# 7x7RGB-IR-J010129B.net
KiCad netlist of a schematic drawn in EAGLE
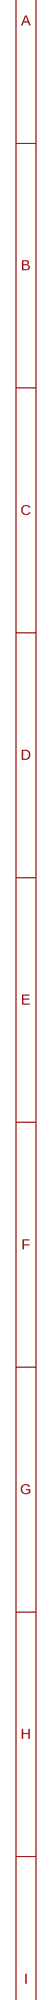
[diagram p0: schematic, sheet 1, part 1 of 2]
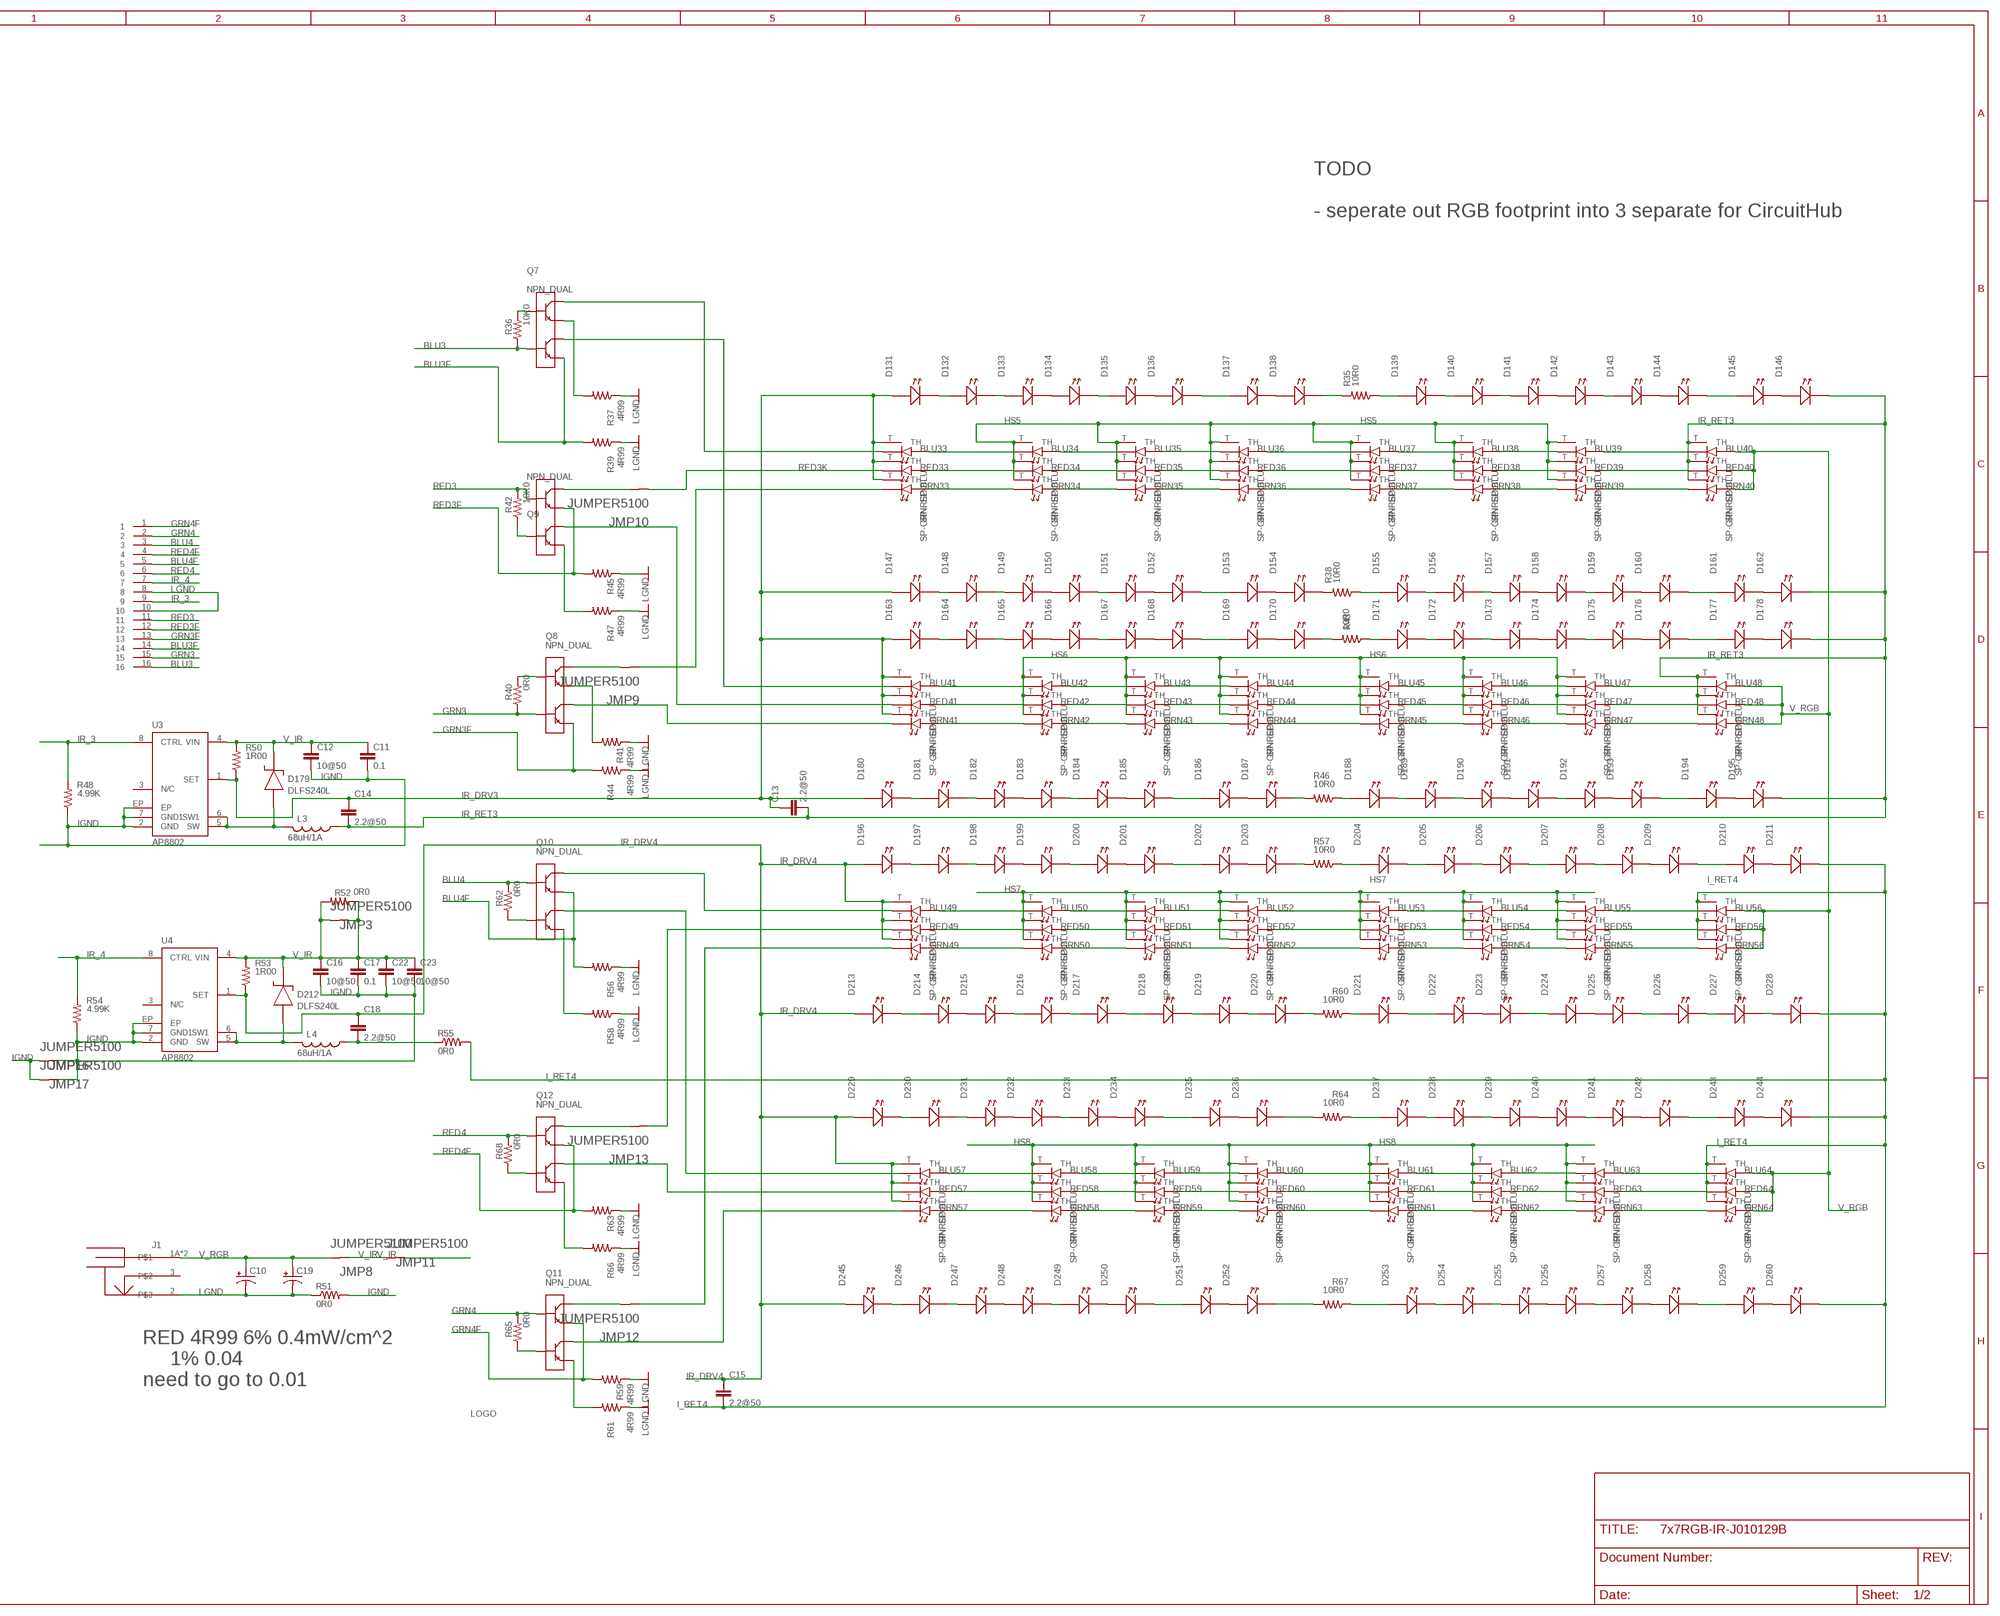
[diagram p1: schematic, sheet 1, part 2 of 2]
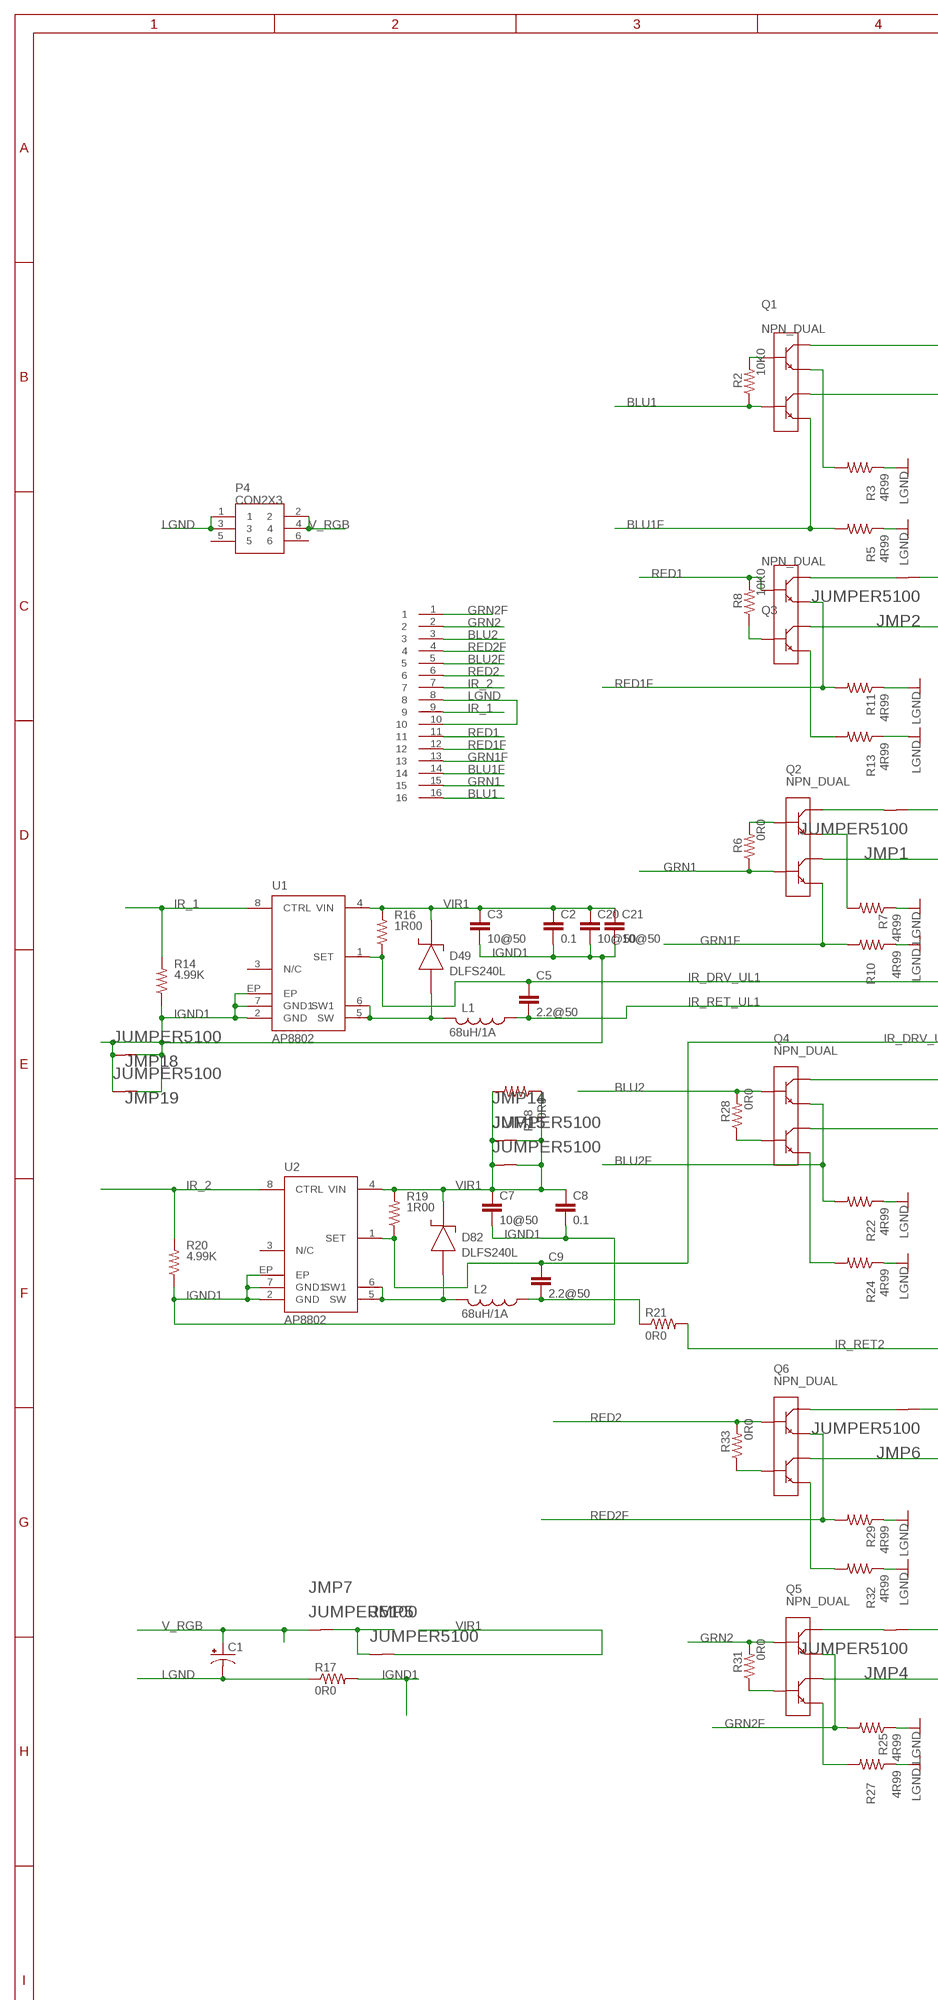
[diagram p2: schematic, sheet 2, part 1 of 2]
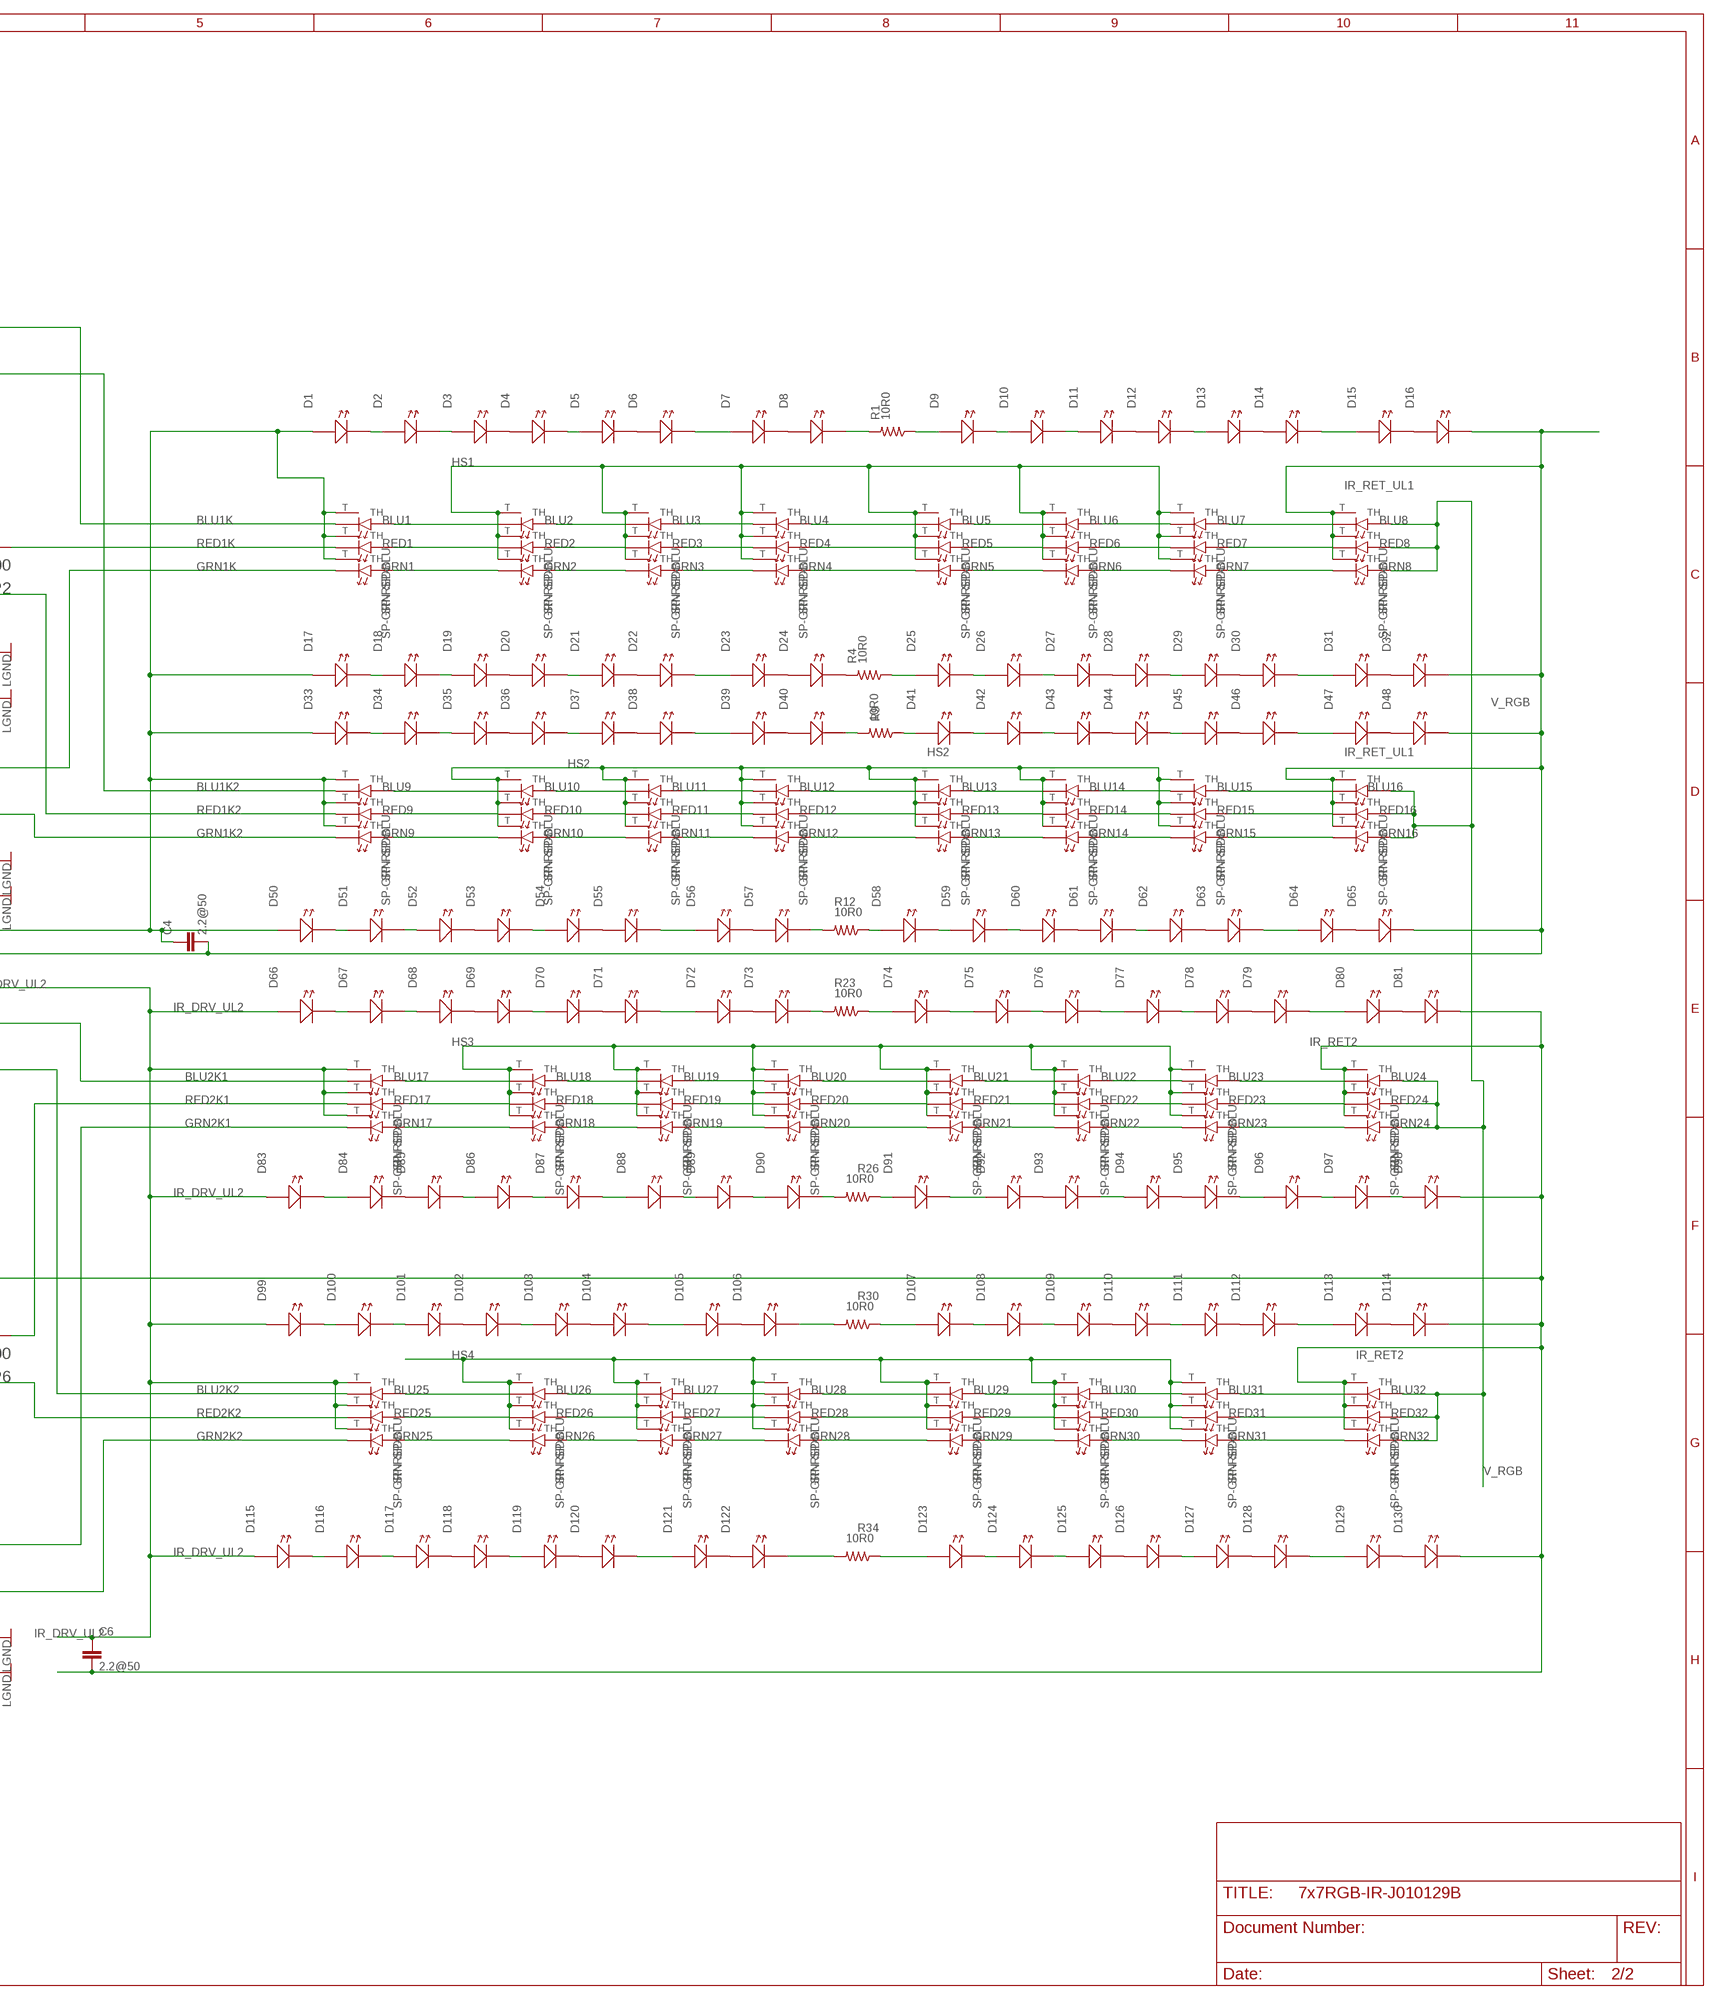
[diagram p3: schematic, sheet 2, part 2 of 2]

(export (version "E")
  (design (tool "Eeschema 10.0.6"))
  (components
    (comp (ref "BLU1")
      (value "SP-BLU")
      (footprint "eagle-import:SUNPLUS-LED")
      (libsource (lib "eagle-import") (part "LED-TH"))
    )
    (comp (ref "BLU2")
      (value "SP-BLU")
      (footprint "eagle-import:SUNPLUS-LED")
      (libsource (lib "eagle-import") (part "LED-TH"))
    )
    (comp (ref "BLU3")
      (value "SP-BLU")
      (footprint "eagle-import:SUNPLUS-LED")
      (libsource (lib "eagle-import") (part "LED-TH"))
    )
    (comp (ref "BLU4")
      (value "SP-BLU")
      (footprint "eagle-import:SUNPLUS-LED")
      (libsource (lib "eagle-import") (part "LED-TH"))
    )
    (comp (ref "BLU5")
      (value "SP-BLU")
      (footprint "eagle-import:SUNPLUS-LED")
      (libsource (lib "eagle-import") (part "LED-TH"))
    )
    (comp (ref "BLU6")
      (value "SP-BLU")
      (footprint "eagle-import:SUNPLUS-LED")
      (libsource (lib "eagle-import") (part "LED-TH"))
    )
    (comp (ref "BLU7")
      (value "SP-BLU")
      (footprint "eagle-import:SUNPLUS-LED")
      (libsource (lib "eagle-import") (part "LED-TH"))
    )
    (comp (ref "BLU8")
      (value "SP-BLU")
      (footprint "eagle-import:SUNPLUS-LED")
      (libsource (lib "eagle-import") (part "LED-TH"))
    )
    (comp (ref "BLU9")
      (value "SP-BLU")
      (footprint "eagle-import:SUNPLUS-LED")
      (libsource (lib "eagle-import") (part "LED-TH"))
    )
    (comp (ref "BLU10")
      (value "SP-BLU")
      (footprint "eagle-import:SUNPLUS-LED")
      (libsource (lib "eagle-import") (part "LED-TH"))
    )
    (comp (ref "BLU11")
      (value "SP-BLU")
      (footprint "eagle-import:SUNPLUS-LED")
      (libsource (lib "eagle-import") (part "LED-TH"))
    )
    (comp (ref "BLU12")
      (value "SP-BLU")
      (footprint "eagle-import:SUNPLUS-LED")
      (libsource (lib "eagle-import") (part "LED-TH"))
    )
    (comp (ref "BLU13")
      (value "SP-BLU")
      (footprint "eagle-import:SUNPLUS-LED")
      (libsource (lib "eagle-import") (part "LED-TH"))
    )
    (comp (ref "BLU14")
      (value "SP-BLU")
      (footprint "eagle-import:SUNPLUS-LED")
      (libsource (lib "eagle-import") (part "LED-TH"))
    )
    (comp (ref "BLU15")
      (value "SP-BLU")
      (footprint "eagle-import:SUNPLUS-LED")
      (libsource (lib "eagle-import") (part "LED-TH"))
    )
    (comp (ref "BLU16")
      (value "SP-BLU")
      (footprint "eagle-import:SUNPLUS-LED")
      (libsource (lib "eagle-import") (part "LED-TH"))
    )
    (comp (ref "BLU17")
      (value "SP-BLU")
      (footprint "eagle-import:SUNPLUS-LED")
      (libsource (lib "eagle-import") (part "LED-TH"))
    )
    (comp (ref "BLU18")
      (value "SP-BLU")
      (footprint "eagle-import:SUNPLUS-LED")
      (libsource (lib "eagle-import") (part "LED-TH"))
    )
    (comp (ref "BLU19")
      (value "SP-BLU")
      (footprint "eagle-import:SUNPLUS-LED")
      (libsource (lib "eagle-import") (part "LED-TH"))
    )
    (comp (ref "BLU20")
      (value "SP-BLU")
      (footprint "eagle-import:SUNPLUS-LED")
      (libsource (lib "eagle-import") (part "LED-TH"))
    )
    (comp (ref "BLU21")
      (value "SP-BLU")
      (footprint "eagle-import:SUNPLUS-LED")
      (libsource (lib "eagle-import") (part "LED-TH"))
    )
    (comp (ref "BLU22")
      (value "SP-BLU")
      (footprint "eagle-import:SUNPLUS-LED")
      (libsource (lib "eagle-import") (part "LED-TH"))
    )
    (comp (ref "BLU23")
      (value "SP-BLU")
      (footprint "eagle-import:SUNPLUS-LED")
      (libsource (lib "eagle-import") (part "LED-TH"))
    )
    (comp (ref "BLU24")
      (value "SP-BLU")
      (footprint "eagle-import:SUNPLUS-LED")
      (libsource (lib "eagle-import") (part "LED-TH"))
    )
    (comp (ref "BLU25")
      (value "SP-BLU")
      (footprint "eagle-import:SUNPLUS-LED")
      (libsource (lib "eagle-import") (part "LED-TH"))
    )
    (comp (ref "BLU26")
      (value "SP-BLU")
      (footprint "eagle-import:SUNPLUS-LED")
      (libsource (lib "eagle-import") (part "LED-TH"))
    )
    (comp (ref "BLU27")
      (value "SP-BLU")
      (footprint "eagle-import:SUNPLUS-LED")
      (libsource (lib "eagle-import") (part "LED-TH"))
    )
    (comp (ref "BLU28")
      (value "SP-BLU")
      (footprint "eagle-import:SUNPLUS-LED")
      (libsource (lib "eagle-import") (part "LED-TH"))
    )
    (comp (ref "BLU29")
      (value "SP-BLU")
      (footprint "eagle-import:SUNPLUS-LED")
      (libsource (lib "eagle-import") (part "LED-TH"))
    )
    (comp (ref "BLU30")
      (value "SP-BLU")
      (footprint "eagle-import:SUNPLUS-LED")
      (libsource (lib "eagle-import") (part "LED-TH"))
    )
    (comp (ref "BLU31")
      (value "SP-BLU")
      (footprint "eagle-import:SUNPLUS-LED")
      (libsource (lib "eagle-import") (part "LED-TH"))
    )
    (comp (ref "BLU32")
      (value "SP-BLU")
      (footprint "eagle-import:SUNPLUS-LED")
      (libsource (lib "eagle-import") (part "LED-TH"))
    )
    (comp (ref "C1")
      (value "CPOL-US153CLV-0810")
      (footprint "eagle-import:153CLV-0810")
      (libsource (lib "eagle-import") (part "CPOL-US153CLV-0810"))
    )
    (comp (ref "C2")
      (value "0.1")
      (footprint "eagle-import:0805S")
      (libsource (lib "eagle-import") (part "CAPS0805S"))
    )
    (comp (ref "C3")
      (value "10@50")
      (footprint "eagle-import:1210S")
      (libsource (lib "eagle-import") (part "CAPS1210S"))
    )
    (comp (ref "C4")
      (value "2.2@50")
      (footprint "eagle-import:1206S")
      (libsource (lib "eagle-import") (part "CAPS1206S"))
    )
    (comp (ref "C5")
      (value "2.2@50")
      (footprint "eagle-import:1206S")
      (libsource (lib "eagle-import") (part "CAPS1206S"))
    )
    (comp (ref "C6")
      (value "2.2@50")
      (footprint "eagle-import:1206S")
      (libsource (lib "eagle-import") (part "CAPS1206S"))
    )
    (comp (ref "C7")
      (value "10@50")
      (footprint "eagle-import:1210S")
      (libsource (lib "eagle-import") (part "CAPS1210S"))
    )
    (comp (ref "C8")
      (value "0.1")
      (footprint "eagle-import:0805S")
      (libsource (lib "eagle-import") (part "CAPS0805S"))
    )
    (comp (ref "C9")
      (value "2.2@50")
      (footprint "eagle-import:1206S")
      (libsource (lib "eagle-import") (part "CAPS1206S"))
    )
    (comp (ref "C20")
      (value "10@50")
      (footprint "eagle-import:1210S")
      (libsource (lib "eagle-import") (part "CAPS1210S"))
    )
    (comp (ref "C21")
      (value "10@50")
      (footprint "eagle-import:1210S")
      (libsource (lib "eagle-import") (part "CAPS1210S"))
    )
    (comp (ref "D1")
      (value "LEDLED_SFH4050")
      (footprint "eagle-import:LED_SFH4050")
      (libsource (lib "eagle-import") (part "LEDLED_SFH4050"))
    )
    (comp (ref "D2")
      (value "LEDLED_SFH4050")
      (footprint "eagle-import:LED_SFH4050")
      (libsource (lib "eagle-import") (part "LEDLED_SFH4050"))
    )
    (comp (ref "D3")
      (value "LEDLED_SFH4050")
      (footprint "eagle-import:LED_SFH4050")
      (libsource (lib "eagle-import") (part "LEDLED_SFH4050"))
    )
    (comp (ref "D4")
      (value "LEDLED_SFH4050")
      (footprint "eagle-import:LED_SFH4050")
      (libsource (lib "eagle-import") (part "LEDLED_SFH4050"))
    )
    (comp (ref "D5")
      (value "LEDLED_SFH4050")
      (footprint "eagle-import:LED_SFH4050")
      (libsource (lib "eagle-import") (part "LEDLED_SFH4050"))
    )
    (comp (ref "D6")
      (value "LEDLED_SFH4050")
      (footprint "eagle-import:LED_SFH4050")
      (libsource (lib "eagle-import") (part "LEDLED_SFH4050"))
    )
    (comp (ref "D7")
      (value "LEDLED_SFH4050")
      (footprint "eagle-import:LED_SFH4050")
      (libsource (lib "eagle-import") (part "LEDLED_SFH4050"))
    )
    (comp (ref "D8")
      (value "LEDLED_SFH4050")
      (footprint "eagle-import:LED_SFH4050")
      (libsource (lib "eagle-import") (part "LEDLED_SFH4050"))
    )
    (comp (ref "D9")
      (value "LEDLED_SFH4050")
      (footprint "eagle-import:LED_SFH4050")
      (libsource (lib "eagle-import") (part "LEDLED_SFH4050"))
    )
    (comp (ref "D10")
      (value "LEDLED_SFH4050")
      (footprint "eagle-import:LED_SFH4050")
      (libsource (lib "eagle-import") (part "LEDLED_SFH4050"))
    )
    (comp (ref "D11")
      (value "LEDLED_SFH4050")
      (footprint "eagle-import:LED_SFH4050")
      (libsource (lib "eagle-import") (part "LEDLED_SFH4050"))
    )
    (comp (ref "D12")
      (value "LEDLED_SFH4050")
      (footprint "eagle-import:LED_SFH4050")
      (libsource (lib "eagle-import") (part "LEDLED_SFH4050"))
    )
    (comp (ref "D13")
      (value "LEDLED_SFH4050")
      (footprint "eagle-import:LED_SFH4050")
      (libsource (lib "eagle-import") (part "LEDLED_SFH4050"))
    )
    (comp (ref "D14")
      (value "LEDLED_SFH4050")
      (footprint "eagle-import:LED_SFH4050")
      (libsource (lib "eagle-import") (part "LEDLED_SFH4050"))
    )
    (comp (ref "D15")
      (value "LEDLED_SFH4050")
      (footprint "eagle-import:LED_SFH4050")
      (libsource (lib "eagle-import") (part "LEDLED_SFH4050"))
    )
    (comp (ref "D16")
      (value "LEDLED_SFH4050")
      (footprint "eagle-import:LED_SFH4050")
      (libsource (lib "eagle-import") (part "LEDLED_SFH4050"))
    )
    (comp (ref "D17")
      (value "LEDLED_SFH4050")
      (footprint "eagle-import:LED_SFH4050")
      (libsource (lib "eagle-import") (part "LEDLED_SFH4050"))
    )
    (comp (ref "D18")
      (value "LEDLED_SFH4050")
      (footprint "eagle-import:LED_SFH4050")
      (libsource (lib "eagle-import") (part "LEDLED_SFH4050"))
    )
    (comp (ref "D19")
      (value "LEDLED_SFH4050")
      (footprint "eagle-import:LED_SFH4050")
      (libsource (lib "eagle-import") (part "LEDLED_SFH4050"))
    )
    (comp (ref "D20")
      (value "LEDLED_SFH4050")
      (footprint "eagle-import:LED_SFH4050")
      (libsource (lib "eagle-import") (part "LEDLED_SFH4050"))
    )
    (comp (ref "D21")
      (value "LEDLED_SFH4050")
      (footprint "eagle-import:LED_SFH4050")
      (libsource (lib "eagle-import") (part "LEDLED_SFH4050"))
    )
    (comp (ref "D22")
      (value "LEDLED_SFH4050")
      (footprint "eagle-import:LED_SFH4050")
      (libsource (lib "eagle-import") (part "LEDLED_SFH4050"))
    )
    (comp (ref "D23")
      (value "LEDLED_SFH4050")
      (footprint "eagle-import:LED_SFH4050")
      (libsource (lib "eagle-import") (part "LEDLED_SFH4050"))
    )
    (comp (ref "D24")
      (value "LEDLED_SFH4050")
      (footprint "eagle-import:LED_SFH4050")
      (libsource (lib "eagle-import") (part "LEDLED_SFH4050"))
    )
    (comp (ref "D25")
      (value "LEDLED_SFH4050")
      (footprint "eagle-import:LED_SFH4050")
      (libsource (lib "eagle-import") (part "LEDLED_SFH4050"))
    )
    (comp (ref "D26")
      (value "LEDLED_SFH4050")
      (footprint "eagle-import:LED_SFH4050")
      (libsource (lib "eagle-import") (part "LEDLED_SFH4050"))
    )
    (comp (ref "D27")
      (value "LEDLED_SFH4050")
      (footprint "eagle-import:LED_SFH4050")
      (libsource (lib "eagle-import") (part "LEDLED_SFH4050"))
    )
    (comp (ref "D28")
      (value "LEDLED_SFH4050")
      (footprint "eagle-import:LED_SFH4050")
      (libsource (lib "eagle-import") (part "LEDLED_SFH4050"))
    )
    (comp (ref "D29")
      (value "LEDLED_SFH4050")
      (footprint "eagle-import:LED_SFH4050")
      (libsource (lib "eagle-import") (part "LEDLED_SFH4050"))
    )
    (comp (ref "D30")
      (value "LEDLED_SFH4050")
      (footprint "eagle-import:LED_SFH4050")
      (libsource (lib "eagle-import") (part "LEDLED_SFH4050"))
    )
    (comp (ref "D31")
      (value "LEDLED_SFH4050")
      (footprint "eagle-import:LED_SFH4050")
      (libsource (lib "eagle-import") (part "LEDLED_SFH4050"))
    )
    (comp (ref "D32")
      (value "LEDLED_SFH4050")
      (footprint "eagle-import:LED_SFH4050")
      (libsource (lib "eagle-import") (part "LEDLED_SFH4050"))
    )
    (comp (ref "D33")
      (value "LEDLED_SFH4050")
      (footprint "eagle-import:LED_SFH4050")
      (libsource (lib "eagle-import") (part "LEDLED_SFH4050"))
    )
    (comp (ref "D34")
      (value "LEDLED_SFH4050")
      (footprint "eagle-import:LED_SFH4050")
      (libsource (lib "eagle-import") (part "LEDLED_SFH4050"))
    )
    (comp (ref "D35")
      (value "LEDLED_SFH4050")
      (footprint "eagle-import:LED_SFH4050")
      (libsource (lib "eagle-import") (part "LEDLED_SFH4050"))
    )
    (comp (ref "D36")
      (value "LEDLED_SFH4050")
      (footprint "eagle-import:LED_SFH4050")
      (libsource (lib "eagle-import") (part "LEDLED_SFH4050"))
    )
    (comp (ref "D37")
      (value "LEDLED_SFH4050")
      (footprint "eagle-import:LED_SFH4050")
      (libsource (lib "eagle-import") (part "LEDLED_SFH4050"))
    )
    (comp (ref "D38")
      (value "LEDLED_SFH4050")
      (footprint "eagle-import:LED_SFH4050")
      (libsource (lib "eagle-import") (part "LEDLED_SFH4050"))
    )
    (comp (ref "D39")
      (value "LEDLED_SFH4050")
      (footprint "eagle-import:LED_SFH4050")
      (libsource (lib "eagle-import") (part "LEDLED_SFH4050"))
    )
    (comp (ref "D40")
      (value "LEDLED_SFH4050")
      (footprint "eagle-import:LED_SFH4050")
      (libsource (lib "eagle-import") (part "LEDLED_SFH4050"))
    )
    (comp (ref "D41")
      (value "LEDLED_SFH4050")
      (footprint "eagle-import:LED_SFH4050")
      (libsource (lib "eagle-import") (part "LEDLED_SFH4050"))
    )
    (comp (ref "D42")
      (value "LEDLED_SFH4050")
      (footprint "eagle-import:LED_SFH4050")
      (libsource (lib "eagle-import") (part "LEDLED_SFH4050"))
    )
    (comp (ref "D43")
      (value "LEDLED_SFH4050")
      (footprint "eagle-import:LED_SFH4050")
      (libsource (lib "eagle-import") (part "LEDLED_SFH4050"))
    )
    (comp (ref "D44")
      (value "LEDLED_SFH4050")
      (footprint "eagle-import:LED_SFH4050")
      (libsource (lib "eagle-import") (part "LEDLED_SFH4050"))
    )
    (comp (ref "D45")
      (value "LEDLED_SFH4050")
      (footprint "eagle-import:LED_SFH4050")
      (libsource (lib "eagle-import") (part "LEDLED_SFH4050"))
    )
    (comp (ref "D46")
      (value "LEDLED_SFH4050")
      (footprint "eagle-import:LED_SFH4050")
      (libsource (lib "eagle-import") (part "LEDLED_SFH4050"))
    )
    (comp (ref "D47")
      (value "LEDLED_SFH4050")
      (footprint "eagle-import:LED_SFH4050")
      (libsource (lib "eagle-import") (part "LEDLED_SFH4050"))
    )
    (comp (ref "D48")
      (value "LEDLED_SFH4050")
      (footprint "eagle-import:LED_SFH4050")
      (libsource (lib "eagle-import") (part "LEDLED_SFH4050"))
    )
    (comp (ref "D49")
      (value "DLFS240L")
      (footprint "eagle-import:PWRDI-123")
      (libsource (lib "eagle-import") (part "DIODE_SCHOTTKYPWRDI-123"))
    )
    (comp (ref "D50")
      (value "LEDLED_SFH4050")
      (footprint "eagle-import:LED_SFH4050")
      (libsource (lib "eagle-import") (part "LEDLED_SFH4050"))
    )
    (comp (ref "D51")
      (value "LEDLED_SFH4050")
      (footprint "eagle-import:LED_SFH4050")
      (libsource (lib "eagle-import") (part "LEDLED_SFH4050"))
    )
    (comp (ref "D52")
      (value "LEDLED_SFH4050")
      (footprint "eagle-import:LED_SFH4050")
      (libsource (lib "eagle-import") (part "LEDLED_SFH4050"))
    )
    (comp (ref "D53")
      (value "LEDLED_SFH4050")
      (footprint "eagle-import:LED_SFH4050")
      (libsource (lib "eagle-import") (part "LEDLED_SFH4050"))
    )
    (comp (ref "D54")
      (value "LEDLED_SFH4050")
      (footprint "eagle-import:LED_SFH4050")
      (libsource (lib "eagle-import") (part "LEDLED_SFH4050"))
    )
    (comp (ref "D55")
      (value "LEDLED_SFH4050")
      (footprint "eagle-import:LED_SFH4050")
      (libsource (lib "eagle-import") (part "LEDLED_SFH4050"))
    )
    (comp (ref "D56")
      (value "LEDLED_SFH4050")
      (footprint "eagle-import:LED_SFH4050")
      (libsource (lib "eagle-import") (part "LEDLED_SFH4050"))
    )
    (comp (ref "D57")
      (value "LEDLED_SFH4050")
      (footprint "eagle-import:LED_SFH4050")
      (libsource (lib "eagle-import") (part "LEDLED_SFH4050"))
    )
    (comp (ref "D58")
      (value "LEDLED_SFH4050")
      (footprint "eagle-import:LED_SFH4050")
      (libsource (lib "eagle-import") (part "LEDLED_SFH4050"))
    )
    (comp (ref "D59")
      (value "LEDLED_SFH4050")
      (footprint "eagle-import:LED_SFH4050")
      (libsource (lib "eagle-import") (part "LEDLED_SFH4050"))
    )
    (comp (ref "D60")
      (value "LEDLED_SFH4050")
      (footprint "eagle-import:LED_SFH4050")
      (libsource (lib "eagle-import") (part "LEDLED_SFH4050"))
    )
    (comp (ref "D61")
      (value "LEDLED_SFH4050")
      (footprint "eagle-import:LED_SFH4050")
      (libsource (lib "eagle-import") (part "LEDLED_SFH4050"))
    )
    (comp (ref "D62")
      (value "LEDLED_SFH4050")
      (footprint "eagle-import:LED_SFH4050")
      (libsource (lib "eagle-import") (part "LEDLED_SFH4050"))
    )
    (comp (ref "D63")
      (value "LEDLED_SFH4050")
      (footprint "eagle-import:LED_SFH4050")
      (libsource (lib "eagle-import") (part "LEDLED_SFH4050"))
    )
    (comp (ref "D64")
      (value "LEDLED_SFH4050")
      (footprint "eagle-import:LED_SFH4050")
      (libsource (lib "eagle-import") (part "LEDLED_SFH4050"))
    )
    (comp (ref "D65")
      (value "LEDLED_SFH4050")
      (footprint "eagle-import:LED_SFH4050")
      (libsource (lib "eagle-import") (part "LEDLED_SFH4050"))
    )
    (comp (ref "D66")
      (value "LEDLED_SFH4050")
      (footprint "eagle-import:LED_SFH4050")
      (libsource (lib "eagle-import") (part "LEDLED_SFH4050"))
    )
    (comp (ref "D67")
      (value "LEDLED_SFH4050")
      (footprint "eagle-import:LED_SFH4050")
      (libsource (lib "eagle-import") (part "LEDLED_SFH4050"))
    )
    (comp (ref "D68")
      (value "LEDLED_SFH4050")
      (footprint "eagle-import:LED_SFH4050")
      (libsource (lib "eagle-import") (part "LEDLED_SFH4050"))
    )
    (comp (ref "D69")
      (value "LEDLED_SFH4050")
      (footprint "eagle-import:LED_SFH4050")
      (libsource (lib "eagle-import") (part "LEDLED_SFH4050"))
    )
    (comp (ref "D70")
      (value "LEDLED_SFH4050")
      (footprint "eagle-import:LED_SFH4050")
      (libsource (lib "eagle-import") (part "LEDLED_SFH4050"))
    )
    (comp (ref "D71")
      (value "LEDLED_SFH4050")
      (footprint "eagle-import:LED_SFH4050")
      (libsource (lib "eagle-import") (part "LEDLED_SFH4050"))
    )
    (comp (ref "D72")
      (value "LEDLED_SFH4050")
      (footprint "eagle-import:LED_SFH4050")
      (libsource (lib "eagle-import") (part "LEDLED_SFH4050"))
    )
    (comp (ref "D73")
      (value "LEDLED_SFH4050")
      (footprint "eagle-import:LED_SFH4050")
      (libsource (lib "eagle-import") (part "LEDLED_SFH4050"))
    )
    (comp (ref "D74")
      (value "LEDLED_SFH4050")
      (footprint "eagle-import:LED_SFH4050")
      (libsource (lib "eagle-import") (part "LEDLED_SFH4050"))
    )
    (comp (ref "D75")
      (value "LEDLED_SFH4050")
      (footprint "eagle-import:LED_SFH4050")
      (libsource (lib "eagle-import") (part "LEDLED_SFH4050"))
    )
    (comp (ref "D76")
      (value "LEDLED_SFH4050")
      (footprint "eagle-import:LED_SFH4050")
      (libsource (lib "eagle-import") (part "LEDLED_SFH4050"))
    )
    (comp (ref "D77")
      (value "LEDLED_SFH4050")
      (footprint "eagle-import:LED_SFH4050")
      (libsource (lib "eagle-import") (part "LEDLED_SFH4050"))
    )
    (comp (ref "D78")
      (value "LEDLED_SFH4050")
      (footprint "eagle-import:LED_SFH4050")
      (libsource (lib "eagle-import") (part "LEDLED_SFH4050"))
    )
    (comp (ref "D79")
      (value "LEDLED_SFH4050")
      (footprint "eagle-import:LED_SFH4050")
      (libsource (lib "eagle-import") (part "LEDLED_SFH4050"))
    )
    (comp (ref "D80")
      (value "LEDLED_SFH4050")
      (footprint "eagle-import:LED_SFH4050")
      (libsource (lib "eagle-import") (part "LEDLED_SFH4050"))
    )
    (comp (ref "D81")
      (value "LEDLED_SFH4050")
      (footprint "eagle-import:LED_SFH4050")
      (libsource (lib "eagle-import") (part "LEDLED_SFH4050"))
    )
    (comp (ref "D82")
      (value "DLFS240L")
      (footprint "eagle-import:PWRDI-123")
      (libsource (lib "eagle-import") (part "DIODE_SCHOTTKYPWRDI-123"))
    )
    (comp (ref "D83")
      (value "LEDLED_SFH4050")
      (footprint "eagle-import:LED_SFH4050")
      (libsource (lib "eagle-import") (part "LEDLED_SFH4050"))
    )
    (comp (ref "D84")
      (value "LEDLED_SFH4050")
      (footprint "eagle-import:LED_SFH4050")
      (libsource (lib "eagle-import") (part "LEDLED_SFH4050"))
    )
    (comp (ref "D85")
      (value "LEDLED_SFH4050")
      (footprint "eagle-import:LED_SFH4050")
      (libsource (lib "eagle-import") (part "LEDLED_SFH4050"))
    )
    (comp (ref "D86")
      (value "LEDLED_SFH4050")
      (footprint "eagle-import:LED_SFH4050")
      (libsource (lib "eagle-import") (part "LEDLED_SFH4050"))
    )
    (comp (ref "D87")
      (value "LEDLED_SFH4050")
      (footprint "eagle-import:LED_SFH4050")
      (libsource (lib "eagle-import") (part "LEDLED_SFH4050"))
    )
    (comp (ref "D88")
      (value "LEDLED_SFH4050")
      (footprint "eagle-import:LED_SFH4050")
      (libsource (lib "eagle-import") (part "LEDLED_SFH4050"))
    )
    (comp (ref "D89")
      (value "LEDLED_SFH4050")
      (footprint "eagle-import:LED_SFH4050")
      (libsource (lib "eagle-import") (part "LEDLED_SFH4050"))
    )
    (comp (ref "D90")
      (value "LEDLED_SFH4050")
      (footprint "eagle-import:LED_SFH4050")
      (libsource (lib "eagle-import") (part "LEDLED_SFH4050"))
    )
    (comp (ref "D91")
      (value "LEDLED_SFH4050")
      (footprint "eagle-import:LED_SFH4050")
      (libsource (lib "eagle-import") (part "LEDLED_SFH4050"))
    )
    (comp (ref "D92")
      (value "LEDLED_SFH4050")
      (footprint "eagle-import:LED_SFH4050")
      (libsource (lib "eagle-import") (part "LEDLED_SFH4050"))
    )
    (comp (ref "D93")
      (value "LEDLED_SFH4050")
      (footprint "eagle-import:LED_SFH4050")
      (libsource (lib "eagle-import") (part "LEDLED_SFH4050"))
    )
    (comp (ref "D94")
      (value "LEDLED_SFH4050")
      (footprint "eagle-import:LED_SFH4050")
      (libsource (lib "eagle-import") (part "LEDLED_SFH4050"))
    )
    (comp (ref "D95")
      (value "LEDLED_SFH4050")
      (footprint "eagle-import:LED_SFH4050")
      (libsource (lib "eagle-import") (part "LEDLED_SFH4050"))
    )
    (comp (ref "D96")
      (value "LEDLED_SFH4050")
      (footprint "eagle-import:LED_SFH4050")
      (libsource (lib "eagle-import") (part "LEDLED_SFH4050"))
    )
    (comp (ref "D97")
      (value "LEDLED_SFH4050")
      (footprint "eagle-import:LED_SFH4050")
      (libsource (lib "eagle-import") (part "LEDLED_SFH4050"))
    )
    (comp (ref "D98")
      (value "LEDLED_SFH4050")
      (footprint "eagle-import:LED_SFH4050")
      (libsource (lib "eagle-import") (part "LEDLED_SFH4050"))
    )
    (comp (ref "D99")
      (value "LEDLED_SFH4050")
      (footprint "eagle-import:LED_SFH4050")
      (libsource (lib "eagle-import") (part "LEDLED_SFH4050"))
    )
    (comp (ref "D100")
      (value "LEDLED_SFH4050")
      (footprint "eagle-import:LED_SFH4050")
      (libsource (lib "eagle-import") (part "LEDLED_SFH4050"))
    )
    (comp (ref "D101")
      (value "LEDLED_SFH4050")
      (footprint "eagle-import:LED_SFH4050")
      (libsource (lib "eagle-import") (part "LEDLED_SFH4050"))
    )
    (comp (ref "D102")
      (value "LEDLED_SFH4050")
      (footprint "eagle-import:LED_SFH4050")
      (libsource (lib "eagle-import") (part "LEDLED_SFH4050"))
    )
    (comp (ref "D103")
      (value "LEDLED_SFH4050")
      (footprint "eagle-import:LED_SFH4050")
      (libsource (lib "eagle-import") (part "LEDLED_SFH4050"))
    )
    (comp (ref "D104")
      (value "LEDLED_SFH4050")
      (footprint "eagle-import:LED_SFH4050")
      (libsource (lib "eagle-import") (part "LEDLED_SFH4050"))
    )
    (comp (ref "D105")
      (value "LEDLED_SFH4050")
      (footprint "eagle-import:LED_SFH4050")
      (libsource (lib "eagle-import") (part "LEDLED_SFH4050"))
    )
    (comp (ref "D106")
      (value "LEDLED_SFH4050")
      (footprint "eagle-import:LED_SFH4050")
      (libsource (lib "eagle-import") (part "LEDLED_SFH4050"))
    )
    (comp (ref "D107")
      (value "LEDLED_SFH4050")
      (footprint "eagle-import:LED_SFH4050")
      (libsource (lib "eagle-import") (part "LEDLED_SFH4050"))
    )
    (comp (ref "D108")
      (value "LEDLED_SFH4050")
      (footprint "eagle-import:LED_SFH4050")
      (libsource (lib "eagle-import") (part "LEDLED_SFH4050"))
    )
    (comp (ref "D109")
      (value "LEDLED_SFH4050")
      (footprint "eagle-import:LED_SFH4050")
      (libsource (lib "eagle-import") (part "LEDLED_SFH4050"))
    )
    (comp (ref "D110")
      (value "LEDLED_SFH4050")
      (footprint "eagle-import:LED_SFH4050")
      (libsource (lib "eagle-import") (part "LEDLED_SFH4050"))
    )
    (comp (ref "D111")
      (value "LEDLED_SFH4050")
      (footprint "eagle-import:LED_SFH4050")
      (libsource (lib "eagle-import") (part "LEDLED_SFH4050"))
    )
    (comp (ref "D112")
      (value "LEDLED_SFH4050")
      (footprint "eagle-import:LED_SFH4050")
      (libsource (lib "eagle-import") (part "LEDLED_SFH4050"))
    )
    (comp (ref "D113")
      (value "LEDLED_SFH4050")
      (footprint "eagle-import:LED_SFH4050")
      (libsource (lib "eagle-import") (part "LEDLED_SFH4050"))
    )
    (comp (ref "D114")
      (value "LEDLED_SFH4050")
      (footprint "eagle-import:LED_SFH4050")
      (libsource (lib "eagle-import") (part "LEDLED_SFH4050"))
    )
    (comp (ref "D115")
      (value "LEDLED_SFH4050")
      (footprint "eagle-import:LED_SFH4050")
      (libsource (lib "eagle-import") (part "LEDLED_SFH4050"))
    )
    (comp (ref "D116")
      (value "LEDLED_SFH4050")
      (footprint "eagle-import:LED_SFH4050")
      (libsource (lib "eagle-import") (part "LEDLED_SFH4050"))
    )
    (comp (ref "D117")
      (value "LEDLED_SFH4050")
      (footprint "eagle-import:LED_SFH4050")
      (libsource (lib "eagle-import") (part "LEDLED_SFH4050"))
    )
    (comp (ref "D118")
      (value "LEDLED_SFH4050")
      (footprint "eagle-import:LED_SFH4050")
      (libsource (lib "eagle-import") (part "LEDLED_SFH4050"))
    )
    (comp (ref "D119")
      (value "LEDLED_SFH4050")
      (footprint "eagle-import:LED_SFH4050")
      (libsource (lib "eagle-import") (part "LEDLED_SFH4050"))
    )
    (comp (ref "D120")
      (value "LEDLED_SFH4050")
      (footprint "eagle-import:LED_SFH4050")
      (libsource (lib "eagle-import") (part "LEDLED_SFH4050"))
    )
    (comp (ref "D121")
      (value "LEDLED_SFH4050")
      (footprint "eagle-import:LED_SFH4050")
      (libsource (lib "eagle-import") (part "LEDLED_SFH4050"))
    )
    (comp (ref "D122")
      (value "LEDLED_SFH4050")
      (footprint "eagle-import:LED_SFH4050")
      (libsource (lib "eagle-import") (part "LEDLED_SFH4050"))
    )
    (comp (ref "D123")
      (value "LEDLED_SFH4050")
      (footprint "eagle-import:LED_SFH4050")
      (libsource (lib "eagle-import") (part "LEDLED_SFH4050"))
    )
    (comp (ref "D124")
      (value "LEDLED_SFH4050")
      (footprint "eagle-import:LED_SFH4050")
      (libsource (lib "eagle-import") (part "LEDLED_SFH4050"))
    )
    (comp (ref "D125")
      (value "LEDLED_SFH4050")
      (footprint "eagle-import:LED_SFH4050")
      (libsource (lib "eagle-import") (part "LEDLED_SFH4050"))
    )
    (comp (ref "D126")
      (value "LEDLED_SFH4050")
      (footprint "eagle-import:LED_SFH4050")
      (libsource (lib "eagle-import") (part "LEDLED_SFH4050"))
    )
    (comp (ref "D127")
      (value "LEDLED_SFH4050")
      (footprint "eagle-import:LED_SFH4050")
      (libsource (lib "eagle-import") (part "LEDLED_SFH4050"))
    )
    (comp (ref "D128")
      (value "LEDLED_SFH4050")
      (footprint "eagle-import:LED_SFH4050")
      (libsource (lib "eagle-import") (part "LEDLED_SFH4050"))
    )
    (comp (ref "D129")
      (value "LEDLED_SFH4050")
      (footprint "eagle-import:LED_SFH4050")
      (libsource (lib "eagle-import") (part "LEDLED_SFH4050"))
    )
    (comp (ref "D130")
      (value "LEDLED_SFH4050")
      (footprint "eagle-import:LED_SFH4050")
      (libsource (lib "eagle-import") (part "LEDLED_SFH4050"))
    )
    (comp (ref "GRN1")
      (value "SP-GRN")
      (footprint "eagle-import:SUNPLUS-LED")
      (libsource (lib "eagle-import") (part "LED-TH"))
    )
    (comp (ref "GRN2")
      (value "SP-GRN")
      (footprint "eagle-import:SUNPLUS-LED")
      (libsource (lib "eagle-import") (part "LED-TH"))
    )
    (comp (ref "GRN3")
      (value "SP-GRN")
      (footprint "eagle-import:SUNPLUS-LED")
      (libsource (lib "eagle-import") (part "LED-TH"))
    )
    (comp (ref "GRN4")
      (value "SP-GRN")
      (footprint "eagle-import:SUNPLUS-LED")
      (libsource (lib "eagle-import") (part "LED-TH"))
    )
    (comp (ref "GRN5")
      (value "SP-GRN")
      (footprint "eagle-import:SUNPLUS-LED")
      (libsource (lib "eagle-import") (part "LED-TH"))
    )
    (comp (ref "GRN6")
      (value "SP-GRN")
      (footprint "eagle-import:SUNPLUS-LED")
      (libsource (lib "eagle-import") (part "LED-TH"))
    )
    (comp (ref "GRN7")
      (value "SP-GRN")
      (footprint "eagle-import:SUNPLUS-LED")
      (libsource (lib "eagle-import") (part "LED-TH"))
    )
    (comp (ref "GRN8")
      (value "SP-GRN")
      (footprint "eagle-import:SUNPLUS-LED")
      (libsource (lib "eagle-import") (part "LED-TH"))
    )
    (comp (ref "GRN9")
      (value "SP-GRN")
      (footprint "eagle-import:SUNPLUS-LED")
      (libsource (lib "eagle-import") (part "LED-TH"))
    )
    (comp (ref "GRN10")
      (value "SP-GRN")
      (footprint "eagle-import:SUNPLUS-LED")
      (libsource (lib "eagle-import") (part "LED-TH"))
    )
    (comp (ref "GRN11")
      (value "SP-GRN")
      (footprint "eagle-import:SUNPLUS-LED")
      (libsource (lib "eagle-import") (part "LED-TH"))
    )
    (comp (ref "GRN12")
      (value "SP-GRN")
      (footprint "eagle-import:SUNPLUS-LED")
      (libsource (lib "eagle-import") (part "LED-TH"))
    )
    (comp (ref "GRN13")
      (value "SP-GRN")
      (footprint "eagle-import:SUNPLUS-LED")
      (libsource (lib "eagle-import") (part "LED-TH"))
    )
    (comp (ref "GRN14")
      (value "SP-GRN")
      (footprint "eagle-import:SUNPLUS-LED")
      (libsource (lib "eagle-import") (part "LED-TH"))
    )
    (comp (ref "GRN15")
      (value "SP-GRN")
      (footprint "eagle-import:SUNPLUS-LED")
      (libsource (lib "eagle-import") (part "LED-TH"))
    )
    (comp (ref "GRN16")
      (value "SP-GRN")
      (footprint "eagle-import:SUNPLUS-LED")
      (libsource (lib "eagle-import") (part "LED-TH"))
    )
    (comp (ref "GRN17")
      (value "SP-GRN")
      (footprint "eagle-import:SUNPLUS-LED")
      (libsource (lib "eagle-import") (part "LED-TH"))
    )
    (comp (ref "GRN18")
      (value "SP-GRN")
      (footprint "eagle-import:SUNPLUS-LED")
      (libsource (lib "eagle-import") (part "LED-TH"))
    )
    (comp (ref "GRN19")
      (value "SP-GRN")
      (footprint "eagle-import:SUNPLUS-LED")
      (libsource (lib "eagle-import") (part "LED-TH"))
    )
    (comp (ref "GRN20")
      (value "SP-GRN")
      (footprint "eagle-import:SUNPLUS-LED")
      (libsource (lib "eagle-import") (part "LED-TH"))
    )
    (comp (ref "GRN21")
      (value "SP-GRN")
      (footprint "eagle-import:SUNPLUS-LED")
      (libsource (lib "eagle-import") (part "LED-TH"))
    )
    (comp (ref "GRN22")
      (value "SP-GRN")
      (footprint "eagle-import:SUNPLUS-LED")
      (libsource (lib "eagle-import") (part "LED-TH"))
    )
    (comp (ref "GRN23")
      (value "SP-GRN")
      (footprint "eagle-import:SUNPLUS-LED")
      (libsource (lib "eagle-import") (part "LED-TH"))
    )
    (comp (ref "GRN24")
      (value "SP-GRN")
      (footprint "eagle-import:SUNPLUS-LED")
      (libsource (lib "eagle-import") (part "LED-TH"))
    )
    (comp (ref "GRN25")
      (value "SP-GRN")
      (footprint "eagle-import:SUNPLUS-LED")
      (libsource (lib "eagle-import") (part "LED-TH"))
    )
    (comp (ref "GRN26")
      (value "SP-GRN")
      (footprint "eagle-import:SUNPLUS-LED")
      (libsource (lib "eagle-import") (part "LED-TH"))
    )
    (comp (ref "GRN27")
      (value "SP-GRN")
      (footprint "eagle-import:SUNPLUS-LED")
      (libsource (lib "eagle-import") (part "LED-TH"))
    )
    (comp (ref "GRN28")
      (value "SP-GRN")
      (footprint "eagle-import:SUNPLUS-LED")
      (libsource (lib "eagle-import") (part "LED-TH"))
    )
    (comp (ref "GRN29")
      (value "SP-GRN")
      (footprint "eagle-import:SUNPLUS-LED")
      (libsource (lib "eagle-import") (part "LED-TH"))
    )
    (comp (ref "GRN30")
      (value "SP-GRN")
      (footprint "eagle-import:SUNPLUS-LED")
      (libsource (lib "eagle-import") (part "LED-TH"))
    )
    (comp (ref "GRN31")
      (value "SP-GRN")
      (footprint "eagle-import:SUNPLUS-LED")
      (libsource (lib "eagle-import") (part "LED-TH"))
    )
    (comp (ref "GRN32")
      (value "SP-GRN")
      (footprint "eagle-import:SUNPLUS-LED")
      (libsource (lib "eagle-import") (part "LED-TH"))
    )
    (comp (ref "JMP1")
      (value "JUMPER5100")
      (footprint "eagle-import:5100")
      (libsource (lib "eagle-import") (part "JUMPER5100"))
    )
    (comp (ref "JMP2")
      (value "JUMPER5100")
      (footprint "eagle-import:5100")
      (libsource (lib "eagle-import") (part "JUMPER5100"))
    )
    (comp (ref "JMP4")
      (value "JUMPER5100")
      (footprint "eagle-import:5100")
      (libsource (lib "eagle-import") (part "JUMPER5100"))
    )
    (comp (ref "JMP5")
      (value "JUMPER5100")
      (footprint "eagle-import:5100")
      (libsource (lib "eagle-import") (part "JUMPER5100"))
    )
    (comp (ref "JMP6")
      (value "JUMPER5100")
      (footprint "eagle-import:5100")
      (libsource (lib "eagle-import") (part "JUMPER5100"))
    )
    (comp (ref "JMP7")
      (value "JUMPER5100")
      (footprint "eagle-import:5100")
      (libsource (lib "eagle-import") (part "JUMPER5100"))
    )
    (comp (ref "JMP14")
      (value "JUMPER5100")
      (footprint "eagle-import:5100")
      (libsource (lib "eagle-import") (part "JUMPER5100"))
    )
    (comp (ref "JMP15")
      (value "JUMPER5100")
      (footprint "eagle-import:5100")
      (libsource (lib "eagle-import") (part "JUMPER5100"))
    )
    (comp (ref "JMP18")
      (value "JUMPER5100")
      (footprint "eagle-import:5100")
      (libsource (lib "eagle-import") (part "JUMPER5100"))
    )
    (comp (ref "JMP19")
      (value "JUMPER5100")
      (footprint "eagle-import:5100")
      (libsource (lib "eagle-import") (part "JUMPER5100"))
    )
    (comp (ref "L1")
      (value "68uH/1A")
      (footprint "eagle-import:SRU8043")
      (libsource (lib "eagle-import") (part "INDUCTOR_SMSRU8043"))
    )
    (comp (ref "L2")
      (value "68uH/1A")
      (footprint "eagle-import:SRU8043")
      (libsource (lib "eagle-import") (part "INDUCTOR_SMSRU8043"))
    )
    (comp (ref "P1")
      (value "CON162X8SM-SMALL")
      (footprint "eagle-import:HEADER2X8_SM_SMALL")
      (libsource (lib "eagle-import") (part "CON162X8SM-SMALL"))
    )
    (comp (ref "P4")
      (value "CON2X3")
      (footprint "eagle-import:2X3_PLUG")
      (libsource (lib "eagle-import") (part "CON2X3"))
    )
    (comp (ref "Q1")
      (value "NPN_DUAL")
      (footprint "eagle-import:LFPAK56D")
      (libsource (lib "eagle-import") (part "NPN_DUAL"))
    )
    (comp (ref "Q2")
      (value "NPN_DUAL")
      (footprint "eagle-import:LFPAK56D")
      (libsource (lib "eagle-import") (part "NPN_DUAL"))
    )
    (comp (ref "Q3")
      (value "NPN_DUAL")
      (footprint "eagle-import:LFPAK56D")
      (libsource (lib "eagle-import") (part "NPN_DUAL"))
    )
    (comp (ref "Q4")
      (value "NPN_DUAL")
      (footprint "eagle-import:LFPAK56D")
      (libsource (lib "eagle-import") (part "NPN_DUAL"))
    )
    (comp (ref "Q5")
      (value "NPN_DUAL")
      (footprint "eagle-import:LFPAK56D")
      (libsource (lib "eagle-import") (part "NPN_DUAL"))
    )
    (comp (ref "Q6")
      (value "NPN_DUAL")
      (footprint "eagle-import:LFPAK56D")
      (libsource (lib "eagle-import") (part "NPN_DUAL"))
    )
    (comp (ref "R1")
      (value "10R0")
      (footprint "eagle-import:1206S")
      (libsource (lib "eagle-import") (part "RESISTOR_SM1206S"))
    )
    (comp (ref "R2")
      (value "10K0")
      (footprint "eagle-import:1206S")
      (libsource (lib "eagle-import") (part "RESISTOR_SM1206S"))
    )
    (comp (ref "R3")
      (value "4R99")
      (footprint "eagle-import:R2512")
      (libsource (lib "eagle-import") (part "R-US_R2512"))
    )
    (comp (ref "R4")
      (value "10R0")
      (footprint "eagle-import:1206S")
      (libsource (lib "eagle-import") (part "RESISTOR_SM1206S"))
    )
    (comp (ref "R5")
      (value "4R99")
      (footprint "eagle-import:R2512")
      (libsource (lib "eagle-import") (part "R-US_R2512"))
    )
    (comp (ref "R6")
      (value "0R0")
      (footprint "eagle-import:1206S")
      (libsource (lib "eagle-import") (part "RESISTOR_SM1206S"))
    )
    (comp (ref "R7")
      (value "4R99")
      (footprint "eagle-import:R2512")
      (libsource (lib "eagle-import") (part "R-US_R2512"))
    )
    (comp (ref "R8")
      (value "10K0")
      (footprint "eagle-import:1206S")
      (libsource (lib "eagle-import") (part "RESISTOR_SM1206S"))
    )
    (comp (ref "R9")
      (value "10R0")
      (footprint "eagle-import:1206S")
      (libsource (lib "eagle-import") (part "RESISTOR_SM1206S"))
    )
    (comp (ref "R10")
      (value "4R99")
      (footprint "eagle-import:R2512")
      (libsource (lib "eagle-import") (part "R-US_R2512"))
    )
    (comp (ref "R11")
      (value "4R99")
      (footprint "eagle-import:R2512")
      (libsource (lib "eagle-import") (part "R-US_R2512"))
    )
    (comp (ref "R12")
      (value "10R0")
      (footprint "eagle-import:1206S")
      (libsource (lib "eagle-import") (part "RESISTOR_SM1206S"))
    )
    (comp (ref "R13")
      (value "4R99")
      (footprint "eagle-import:R2512")
      (libsource (lib "eagle-import") (part "R-US_R2512"))
    )
    (comp (ref "R14")
      (value "4.99K")
      (footprint "eagle-import:0805S")
      (libsource (lib "eagle-import") (part "RESISTOR_SM0805S"))
    )
    (comp (ref "R16")
      (value "1R00")
      (footprint "eagle-import:1206S")
      (libsource (lib "eagle-import") (part "RESISTOR_SM1206S"))
    )
    (comp (ref "R17")
      (value "0R0")
      (footprint "eagle-import:1206S")
      (libsource (lib "eagle-import") (part "RESISTOR_SM1206S"))
    )
    (comp (ref "R18")
      (value "0R0")
      (footprint "eagle-import:1206S")
      (libsource (lib "eagle-import") (part "RESISTOR_SM1206S"))
    )
    (comp (ref "R19")
      (value "1R00")
      (footprint "eagle-import:1206S")
      (libsource (lib "eagle-import") (part "RESISTOR_SM1206S"))
    )
    (comp (ref "R20")
      (value "4.99K")
      (footprint "eagle-import:0805S")
      (libsource (lib "eagle-import") (part "RESISTOR_SM0805S"))
    )
    (comp (ref "R21")
      (value "0R0")
      (footprint "eagle-import:1206S")
      (libsource (lib "eagle-import") (part "RESISTOR_SM1206S"))
    )
    (comp (ref "R22")
      (value "4R99")
      (footprint "eagle-import:R2512")
      (libsource (lib "eagle-import") (part "R-US_R2512"))
    )
    (comp (ref "R23")
      (value "10R0")
      (footprint "eagle-import:1206S")
      (libsource (lib "eagle-import") (part "RESISTOR_SM1206S"))
    )
    (comp (ref "R24")
      (value "4R99")
      (footprint "eagle-import:R2512")
      (libsource (lib "eagle-import") (part "R-US_R2512"))
    )
    (comp (ref "R25")
      (value "4R99")
      (footprint "eagle-import:R2512")
      (libsource (lib "eagle-import") (part "R-US_R2512"))
    )
    (comp (ref "R26")
      (value "10R0")
      (footprint "eagle-import:1206S")
      (libsource (lib "eagle-import") (part "RESISTOR_SM1206S"))
    )
    (comp (ref "R27")
      (value "4R99")
      (footprint "eagle-import:R2512")
      (libsource (lib "eagle-import") (part "R-US_R2512"))
    )
    (comp (ref "R28")
      (value "0R0")
      (footprint "eagle-import:1206S")
      (libsource (lib "eagle-import") (part "RESISTOR_SM1206S"))
    )
    (comp (ref "R29")
      (value "4R99")
      (footprint "eagle-import:R2512")
      (libsource (lib "eagle-import") (part "R-US_R2512"))
    )
    (comp (ref "R30")
      (value "10R0")
      (footprint "eagle-import:1206S")
      (libsource (lib "eagle-import") (part "RESISTOR_SM1206S"))
    )
    (comp (ref "R31")
      (value "0R0")
      (footprint "eagle-import:1206S")
      (libsource (lib "eagle-import") (part "RESISTOR_SM1206S"))
    )
    (comp (ref "R32")
      (value "4R99")
      (footprint "eagle-import:R2512")
      (libsource (lib "eagle-import") (part "R-US_R2512"))
    )
    (comp (ref "R33")
      (value "0R0")
      (footprint "eagle-import:1206S")
      (libsource (lib "eagle-import") (part "RESISTOR_SM1206S"))
    )
    (comp (ref "R34")
      (value "10R0")
      (footprint "eagle-import:1206S")
      (libsource (lib "eagle-import") (part "RESISTOR_SM1206S"))
    )
    (comp (ref "RED1")
      (value "SP-RED")
      (footprint "eagle-import:SUNPLUS-LED")
      (libsource (lib "eagle-import") (part "LED-TH"))
    )
    (comp (ref "RED2")
      (value "SP-RED")
      (footprint "eagle-import:SUNPLUS-LED")
      (libsource (lib "eagle-import") (part "LED-TH"))
    )
    (comp (ref "RED3")
      (value "SP-RED")
      (footprint "eagle-import:SUNPLUS-LED")
      (libsource (lib "eagle-import") (part "LED-TH"))
    )
    (comp (ref "RED4")
      (value "SP-RED")
      (footprint "eagle-import:SUNPLUS-LED")
      (libsource (lib "eagle-import") (part "LED-TH"))
    )
    (comp (ref "RED5")
      (value "SP-RED")
      (footprint "eagle-import:SUNPLUS-LED")
      (libsource (lib "eagle-import") (part "LED-TH"))
    )
    (comp (ref "RED6")
      (value "SP-RED")
      (footprint "eagle-import:SUNPLUS-LED")
      (libsource (lib "eagle-import") (part "LED-TH"))
    )
    (comp (ref "RED7")
      (value "SP-RED")
      (footprint "eagle-import:SUNPLUS-LED")
      (libsource (lib "eagle-import") (part "LED-TH"))
    )
    (comp (ref "RED8")
      (value "SP-RED")
      (footprint "eagle-import:SUNPLUS-LED")
      (libsource (lib "eagle-import") (part "LED-TH"))
    )
    (comp (ref "RED9")
      (value "SP-RED")
      (footprint "eagle-import:SUNPLUS-LED")
      (libsource (lib "eagle-import") (part "LED-TH"))
    )
    (comp (ref "RED10")
      (value "SP-RED")
      (footprint "eagle-import:SUNPLUS-LED")
      (libsource (lib "eagle-import") (part "LED-TH"))
    )
    (comp (ref "RED11")
      (value "SP-RED")
      (footprint "eagle-import:SUNPLUS-LED")
      (libsource (lib "eagle-import") (part "LED-TH"))
    )
    (comp (ref "RED12")
      (value "SP-RED")
      (footprint "eagle-import:SUNPLUS-LED")
      (libsource (lib "eagle-import") (part "LED-TH"))
    )
    (comp (ref "RED13")
      (value "SP-RED")
      (footprint "eagle-import:SUNPLUS-LED")
      (libsource (lib "eagle-import") (part "LED-TH"))
    )
    (comp (ref "RED14")
      (value "SP-RED")
      (footprint "eagle-import:SUNPLUS-LED")
      (libsource (lib "eagle-import") (part "LED-TH"))
    )
    (comp (ref "RED15")
      (value "SP-RED")
      (footprint "eagle-import:SUNPLUS-LED")
      (libsource (lib "eagle-import") (part "LED-TH"))
    )
    (comp (ref "RED16")
      (value "SP-RED")
      (footprint "eagle-import:SUNPLUS-LED")
      (libsource (lib "eagle-import") (part "LED-TH"))
    )
    (comp (ref "RED17")
      (value "SP-RED")
      (footprint "eagle-import:SUNPLUS-LED")
      (libsource (lib "eagle-import") (part "LED-TH"))
    )
    (comp (ref "RED18")
      (value "SP-RED")
      (footprint "eagle-import:SUNPLUS-LED")
      (libsource (lib "eagle-import") (part "LED-TH"))
    )
    (comp (ref "RED19")
      (value "SP-RED")
      (footprint "eagle-import:SUNPLUS-LED")
      (libsource (lib "eagle-import") (part "LED-TH"))
    )
    (comp (ref "RED20")
      (value "SP-RED")
      (footprint "eagle-import:SUNPLUS-LED")
      (libsource (lib "eagle-import") (part "LED-TH"))
    )
    (comp (ref "RED21")
      (value "SP-RED")
      (footprint "eagle-import:SUNPLUS-LED")
      (libsource (lib "eagle-import") (part "LED-TH"))
    )
    (comp (ref "RED22")
      (value "SP-RED")
      (footprint "eagle-import:SUNPLUS-LED")
      (libsource (lib "eagle-import") (part "LED-TH"))
    )
    (comp (ref "RED23")
      (value "SP-RED")
      (footprint "eagle-import:SUNPLUS-LED")
      (libsource (lib "eagle-import") (part "LED-TH"))
    )
    (comp (ref "RED24")
      (value "SP-RED")
      (footprint "eagle-import:SUNPLUS-LED")
      (libsource (lib "eagle-import") (part "LED-TH"))
    )
    (comp (ref "RED25")
      (value "SP-RED")
      (footprint "eagle-import:SUNPLUS-LED")
      (libsource (lib "eagle-import") (part "LED-TH"))
    )
    (comp (ref "RED26")
      (value "SP-RED")
      (footprint "eagle-import:SUNPLUS-LED")
      (libsource (lib "eagle-import") (part "LED-TH"))
    )
    (comp (ref "RED27")
      (value "SP-RED")
      (footprint "eagle-import:SUNPLUS-LED")
      (libsource (lib "eagle-import") (part "LED-TH"))
    )
    (comp (ref "RED28")
      (value "SP-RED")
      (footprint "eagle-import:SUNPLUS-LED")
      (libsource (lib "eagle-import") (part "LED-TH"))
    )
    (comp (ref "RED29")
      (value "SP-RED")
      (footprint "eagle-import:SUNPLUS-LED")
      (libsource (lib "eagle-import") (part "LED-TH"))
    )
    (comp (ref "RED30")
      (value "SP-RED")
      (footprint "eagle-import:SUNPLUS-LED")
      (libsource (lib "eagle-import") (part "LED-TH"))
    )
    (comp (ref "RED31")
      (value "SP-RED")
      (footprint "eagle-import:SUNPLUS-LED")
      (libsource (lib "eagle-import") (part "LED-TH"))
    )
    (comp (ref "RED32")
      (value "SP-RED")
      (footprint "eagle-import:SUNPLUS-LED")
      (libsource (lib "eagle-import") (part "LED-TH"))
    )
    (comp (ref "U1")
      (value "AP8802")
      (footprint "eagle-import:SOIC8-EP")
      (libsource (lib "eagle-import") (part "AP8802"))
    )
    (comp (ref "U2")
      (value "AP8802")
      (footprint "eagle-import:SOIC8-EP")
      (libsource (lib "eagle-import") (part "AP8802"))
    )
    (comp (ref "BLU33")
      (value "SP-BLU")
      (footprint "eagle-import:SUNPLUS-LED")
      (libsource (lib "eagle-import") (part "LED-TH"))
    )
    (comp (ref "BLU34")
      (value "SP-BLU")
      (footprint "eagle-import:SUNPLUS-LED")
      (libsource (lib "eagle-import") (part "LED-TH"))
    )
    (comp (ref "BLU35")
      (value "SP-BLU")
      (footprint "eagle-import:SUNPLUS-LED")
      (libsource (lib "eagle-import") (part "LED-TH"))
    )
    (comp (ref "BLU36")
      (value "SP-BLU")
      (footprint "eagle-import:SUNPLUS-LED")
      (libsource (lib "eagle-import") (part "LED-TH"))
    )
    (comp (ref "BLU37")
      (value "SP-BLU")
      (footprint "eagle-import:SUNPLUS-LED")
      (libsource (lib "eagle-import") (part "LED-TH"))
    )
    (comp (ref "BLU38")
      (value "SP-BLU")
      (footprint "eagle-import:SUNPLUS-LED")
      (libsource (lib "eagle-import") (part "LED-TH"))
    )
    (comp (ref "BLU39")
      (value "SP-BLU")
      (footprint "eagle-import:SUNPLUS-LED")
      (libsource (lib "eagle-import") (part "LED-TH"))
    )
    (comp (ref "BLU40")
      (value "SP-BLU")
      (footprint "eagle-import:SUNPLUS-LED")
      (libsource (lib "eagle-import") (part "LED-TH"))
    )
    (comp (ref "BLU41")
      (value "SP-BLU")
      (footprint "eagle-import:SUNPLUS-LED")
      (libsource (lib "eagle-import") (part "LED-TH"))
    )
    (comp (ref "BLU42")
      (value "SP-BLU")
      (footprint "eagle-import:SUNPLUS-LED")
      (libsource (lib "eagle-import") (part "LED-TH"))
    )
    (comp (ref "BLU43")
      (value "SP-BLU")
      (footprint "eagle-import:SUNPLUS-LED")
      (libsource (lib "eagle-import") (part "LED-TH"))
    )
    (comp (ref "BLU44")
      (value "SP-BLU")
      (footprint "eagle-import:SUNPLUS-LED")
      (libsource (lib "eagle-import") (part "LED-TH"))
    )
    (comp (ref "BLU45")
      (value "SP-BLU")
      (footprint "eagle-import:SUNPLUS-LED")
      (libsource (lib "eagle-import") (part "LED-TH"))
    )
    (comp (ref "BLU46")
      (value "SP-BLU")
      (footprint "eagle-import:SUNPLUS-LED")
      (libsource (lib "eagle-import") (part "LED-TH"))
    )
    (comp (ref "BLU47")
      (value "SP-BLU")
      (footprint "eagle-import:SUNPLUS-LED")
      (libsource (lib "eagle-import") (part "LED-TH"))
    )
    (comp (ref "BLU48")
      (value "SP-BLU")
      (footprint "eagle-import:SUNPLUS-LED")
      (libsource (lib "eagle-import") (part "LED-TH"))
    )
    (comp (ref "BLU49")
      (value "SP-BLU")
      (footprint "eagle-import:SUNPLUS-LED")
      (libsource (lib "eagle-import") (part "LED-TH"))
    )
    (comp (ref "BLU50")
      (value "SP-BLU")
      (footprint "eagle-import:SUNPLUS-LED")
      (libsource (lib "eagle-import") (part "LED-TH"))
    )
    (comp (ref "BLU51")
      (value "SP-BLU")
      (footprint "eagle-import:SUNPLUS-LED")
      (libsource (lib "eagle-import") (part "LED-TH"))
    )
    (comp (ref "BLU52")
      (value "SP-BLU")
      (footprint "eagle-import:SUNPLUS-LED")
      (libsource (lib "eagle-import") (part "LED-TH"))
    )
    (comp (ref "BLU53")
      (value "SP-BLU")
      (footprint "eagle-import:SUNPLUS-LED")
      (libsource (lib "eagle-import") (part "LED-TH"))
    )
    (comp (ref "BLU54")
      (value "SP-BLU")
      (footprint "eagle-import:SUNPLUS-LED")
      (libsource (lib "eagle-import") (part "LED-TH"))
    )
    (comp (ref "BLU55")
      (value "SP-BLU")
      (footprint "eagle-import:SUNPLUS-LED")
      (libsource (lib "eagle-import") (part "LED-TH"))
    )
    (comp (ref "BLU56")
      (value "SP-BLU")
      (footprint "eagle-import:SUNPLUS-LED")
      (libsource (lib "eagle-import") (part "LED-TH"))
    )
    (comp (ref "BLU57")
      (value "SP-BLU")
      (footprint "eagle-import:SUNPLUS-LED")
      (libsource (lib "eagle-import") (part "LED-TH"))
    )
    (comp (ref "BLU58")
      (value "SP-BLU")
      (footprint "eagle-import:SUNPLUS-LED")
      (libsource (lib "eagle-import") (part "LED-TH"))
    )
    (comp (ref "BLU59")
      (value "SP-BLU")
      (footprint "eagle-import:SUNPLUS-LED")
      (libsource (lib "eagle-import") (part "LED-TH"))
    )
    (comp (ref "BLU60")
      (value "SP-BLU")
      (footprint "eagle-import:SUNPLUS-LED")
      (libsource (lib "eagle-import") (part "LED-TH"))
    )
    (comp (ref "BLU61")
      (value "SP-BLU")
      (footprint "eagle-import:SUNPLUS-LED")
      (libsource (lib "eagle-import") (part "LED-TH"))
    )
    (comp (ref "BLU62")
      (value "SP-BLU")
      (footprint "eagle-import:SUNPLUS-LED")
      (libsource (lib "eagle-import") (part "LED-TH"))
    )
    (comp (ref "BLU63")
      (value "SP-BLU")
      (footprint "eagle-import:SUNPLUS-LED")
      (libsource (lib "eagle-import") (part "LED-TH"))
    )
    (comp (ref "BLU64")
      (value "SP-BLU")
      (footprint "eagle-import:SUNPLUS-LED")
      (libsource (lib "eagle-import") (part "LED-TH"))
    )
    (comp (ref "C10")
      (value "CPOL-US153CLV-0810")
      (footprint "eagle-import:153CLV-0810")
      (libsource (lib "eagle-import") (part "CPOL-US153CLV-0810"))
    )
    (comp (ref "C11")
      (value "0.1")
      (footprint "eagle-import:0805S")
      (libsource (lib "eagle-import") (part "CAPS0805S"))
    )
    (comp (ref "C12")
      (value "10@50")
      (footprint "eagle-import:1210S")
      (libsource (lib "eagle-import") (part "CAPS1210S"))
    )
    (comp (ref "C13")
      (value "2.2@50")
      (footprint "eagle-import:1206S")
      (libsource (lib "eagle-import") (part "CAPS1206S"))
    )
    (comp (ref "C14")
      (value "2.2@50")
      (footprint "eagle-import:1206S")
      (libsource (lib "eagle-import") (part "CAPS1206S"))
    )
    (comp (ref "C15")
      (value "2.2@50")
      (footprint "eagle-import:1206S")
      (libsource (lib "eagle-import") (part "CAPS1206S"))
    )
    (comp (ref "C16")
      (value "10@50")
      (footprint "eagle-import:1210S")
      (libsource (lib "eagle-import") (part "CAPS1210S"))
    )
    (comp (ref "C17")
      (value "0.1")
      (footprint "eagle-import:0805S")
      (libsource (lib "eagle-import") (part "CAPS0805S"))
    )
    (comp (ref "C18")
      (value "2.2@50")
      (footprint "eagle-import:1206S")
      (libsource (lib "eagle-import") (part "CAPS1206S"))
    )
    (comp (ref "C19")
      (value "CPOL-US153CLV-0810")
      (footprint "eagle-import:153CLV-0810")
      (libsource (lib "eagle-import") (part "CPOL-US153CLV-0810"))
    )
    (comp (ref "C22")
      (value "10@50")
      (footprint "eagle-import:1210S")
      (libsource (lib "eagle-import") (part "CAPS1210S"))
    )
    (comp (ref "C23")
      (value "10@50")
      (footprint "eagle-import:1210S")
      (libsource (lib "eagle-import") (part "CAPS1210S"))
    )
    (comp (ref "D131")
      (value "LEDLED_SFH4050")
      (footprint "eagle-import:LED_SFH4050")
      (libsource (lib "eagle-import") (part "LEDLED_SFH4050"))
    )
    (comp (ref "D132")
      (value "LEDLED_SFH4050")
      (footprint "eagle-import:LED_SFH4050")
      (libsource (lib "eagle-import") (part "LEDLED_SFH4050"))
    )
    (comp (ref "D133")
      (value "LEDLED_SFH4050")
      (footprint "eagle-import:LED_SFH4050")
      (libsource (lib "eagle-import") (part "LEDLED_SFH4050"))
    )
    (comp (ref "D134")
      (value "LEDLED_SFH4050")
      (footprint "eagle-import:LED_SFH4050")
      (libsource (lib "eagle-import") (part "LEDLED_SFH4050"))
    )
    (comp (ref "D135")
      (value "LEDLED_SFH4050")
      (footprint "eagle-import:LED_SFH4050")
      (libsource (lib "eagle-import") (part "LEDLED_SFH4050"))
    )
    (comp (ref "D136")
      (value "LEDLED_SFH4050")
      (footprint "eagle-import:LED_SFH4050")
      (libsource (lib "eagle-import") (part "LEDLED_SFH4050"))
    )
    (comp (ref "D137")
      (value "LEDLED_SFH4050")
      (footprint "eagle-import:LED_SFH4050")
      (libsource (lib "eagle-import") (part "LEDLED_SFH4050"))
    )
    (comp (ref "D138")
      (value "LEDLED_SFH4050")
      (footprint "eagle-import:LED_SFH4050")
      (libsource (lib "eagle-import") (part "LEDLED_SFH4050"))
    )
    (comp (ref "D139")
      (value "LEDLED_SFH4050")
      (footprint "eagle-import:LED_SFH4050")
      (libsource (lib "eagle-import") (part "LEDLED_SFH4050"))
    )
    (comp (ref "D140")
      (value "LEDLED_SFH4050")
      (footprint "eagle-import:LED_SFH4050")
      (libsource (lib "eagle-import") (part "LEDLED_SFH4050"))
    )
    (comp (ref "D141")
      (value "LEDLED_SFH4050")
      (footprint "eagle-import:LED_SFH4050")
      (libsource (lib "eagle-import") (part "LEDLED_SFH4050"))
    )
    (comp (ref "D142")
      (value "LEDLED_SFH4050")
      (footprint "eagle-import:LED_SFH4050")
      (libsource (lib "eagle-import") (part "LEDLED_SFH4050"))
    )
    (comp (ref "D143")
      (value "LEDLED_SFH4050")
      (footprint "eagle-import:LED_SFH4050")
      (libsource (lib "eagle-import") (part "LEDLED_SFH4050"))
    )
    (comp (ref "D144")
      (value "LEDLED_SFH4050")
      (footprint "eagle-import:LED_SFH4050")
      (libsource (lib "eagle-import") (part "LEDLED_SFH4050"))
    )
    (comp (ref "D145")
      (value "LEDLED_SFH4050")
      (footprint "eagle-import:LED_SFH4050")
      (libsource (lib "eagle-import") (part "LEDLED_SFH4050"))
    )
    (comp (ref "D146")
      (value "LEDLED_SFH4050")
      (footprint "eagle-import:LED_SFH4050")
      (libsource (lib "eagle-import") (part "LEDLED_SFH4050"))
    )
    (comp (ref "D147")
      (value "LEDLED_SFH4050")
      (footprint "eagle-import:LED_SFH4050")
      (libsource (lib "eagle-import") (part "LEDLED_SFH4050"))
    )
    (comp (ref "D148")
      (value "LEDLED_SFH4050")
      (footprint "eagle-import:LED_SFH4050")
      (libsource (lib "eagle-import") (part "LEDLED_SFH4050"))
    )
    (comp (ref "D149")
      (value "LEDLED_SFH4050")
      (footprint "eagle-import:LED_SFH4050")
      (libsource (lib "eagle-import") (part "LEDLED_SFH4050"))
    )
    (comp (ref "D150")
      (value "LEDLED_SFH4050")
      (footprint "eagle-import:LED_SFH4050")
      (libsource (lib "eagle-import") (part "LEDLED_SFH4050"))
    )
    (comp (ref "D151")
      (value "LEDLED_SFH4050")
      (footprint "eagle-import:LED_SFH4050")
      (libsource (lib "eagle-import") (part "LEDLED_SFH4050"))
    )
    (comp (ref "D152")
      (value "LEDLED_SFH4050")
      (footprint "eagle-import:LED_SFH4050")
      (libsource (lib "eagle-import") (part "LEDLED_SFH4050"))
    )
    (comp (ref "D153")
      (value "LEDLED_SFH4050")
      (footprint "eagle-import:LED_SFH4050")
      (libsource (lib "eagle-import") (part "LEDLED_SFH4050"))
    )
    (comp (ref "D154")
      (value "LEDLED_SFH4050")
      (footprint "eagle-import:LED_SFH4050")
      (libsource (lib "eagle-import") (part "LEDLED_SFH4050"))
    )
    (comp (ref "D155")
      (value "LEDLED_SFH4050")
      (footprint "eagle-import:LED_SFH4050")
      (libsource (lib "eagle-import") (part "LEDLED_SFH4050"))
    )
    (comp (ref "D156")
      (value "LEDLED_SFH4050")
      (footprint "eagle-import:LED_SFH4050")
      (libsource (lib "eagle-import") (part "LEDLED_SFH4050"))
    )
    (comp (ref "D157")
      (value "LEDLED_SFH4050")
      (footprint "eagle-import:LED_SFH4050")
      (libsource (lib "eagle-import") (part "LEDLED_SFH4050"))
    )
    (comp (ref "D158")
      (value "LEDLED_SFH4050")
      (footprint "eagle-import:LED_SFH4050")
      (libsource (lib "eagle-import") (part "LEDLED_SFH4050"))
    )
    (comp (ref "D159")
      (value "LEDLED_SFH4050")
      (footprint "eagle-import:LED_SFH4050")
      (libsource (lib "eagle-import") (part "LEDLED_SFH4050"))
    )
    (comp (ref "D160")
      (value "LEDLED_SFH4050")
      (footprint "eagle-import:LED_SFH4050")
      (libsource (lib "eagle-import") (part "LEDLED_SFH4050"))
    )
    (comp (ref "D161")
      (value "LEDLED_SFH4050")
      (footprint "eagle-import:LED_SFH4050")
      (libsource (lib "eagle-import") (part "LEDLED_SFH4050"))
    )
    (comp (ref "D162")
      (value "LEDLED_SFH4050")
      (footprint "eagle-import:LED_SFH4050")
      (libsource (lib "eagle-import") (part "LEDLED_SFH4050"))
    )
    (comp (ref "D163")
      (value "LEDLED_SFH4050")
      (footprint "eagle-import:LED_SFH4050")
      (libsource (lib "eagle-import") (part "LEDLED_SFH4050"))
    )
    (comp (ref "D164")
      (value "LEDLED_SFH4050")
      (footprint "eagle-import:LED_SFH4050")
      (libsource (lib "eagle-import") (part "LEDLED_SFH4050"))
    )
    (comp (ref "D165")
      (value "LEDLED_SFH4050")
      (footprint "eagle-import:LED_SFH4050")
      (libsource (lib "eagle-import") (part "LEDLED_SFH4050"))
    )
    (comp (ref "D166")
      (value "LEDLED_SFH4050")
      (footprint "eagle-import:LED_SFH4050")
      (libsource (lib "eagle-import") (part "LEDLED_SFH4050"))
    )
    (comp (ref "D167")
      (value "LEDLED_SFH4050")
      (footprint "eagle-import:LED_SFH4050")
      (libsource (lib "eagle-import") (part "LEDLED_SFH4050"))
    )
    (comp (ref "D168")
      (value "LEDLED_SFH4050")
      (footprint "eagle-import:LED_SFH4050")
      (libsource (lib "eagle-import") (part "LEDLED_SFH4050"))
    )
    (comp (ref "D169")
      (value "LEDLED_SFH4050")
      (footprint "eagle-import:LED_SFH4050")
      (libsource (lib "eagle-import") (part "LEDLED_SFH4050"))
    )
    (comp (ref "D170")
      (value "LEDLED_SFH4050")
      (footprint "eagle-import:LED_SFH4050")
      (libsource (lib "eagle-import") (part "LEDLED_SFH4050"))
    )
    (comp (ref "D171")
      (value "LEDLED_SFH4050")
      (footprint "eagle-import:LED_SFH4050")
      (libsource (lib "eagle-import") (part "LEDLED_SFH4050"))
    )
    (comp (ref "D172")
      (value "LEDLED_SFH4050")
      (footprint "eagle-import:LED_SFH4050")
      (libsource (lib "eagle-import") (part "LEDLED_SFH4050"))
    )
    (comp (ref "D173")
      (value "LEDLED_SFH4050")
      (footprint "eagle-import:LED_SFH4050")
      (libsource (lib "eagle-import") (part "LEDLED_SFH4050"))
    )
    (comp (ref "D174")
      (value "LEDLED_SFH4050")
      (footprint "eagle-import:LED_SFH4050")
      (libsource (lib "eagle-import") (part "LEDLED_SFH4050"))
    )
    (comp (ref "D175")
      (value "LEDLED_SFH4050")
      (footprint "eagle-import:LED_SFH4050")
      (libsource (lib "eagle-import") (part "LEDLED_SFH4050"))
    )
    (comp (ref "D176")
      (value "LEDLED_SFH4050")
      (footprint "eagle-import:LED_SFH4050")
      (libsource (lib "eagle-import") (part "LEDLED_SFH4050"))
    )
    (comp (ref "D177")
      (value "LEDLED_SFH4050")
      (footprint "eagle-import:LED_SFH4050")
      (libsource (lib "eagle-import") (part "LEDLED_SFH4050"))
    )
    (comp (ref "D178")
      (value "LEDLED_SFH4050")
      (footprint "eagle-import:LED_SFH4050")
      (libsource (lib "eagle-import") (part "LEDLED_SFH4050"))
    )
    (comp (ref "D179")
      (value "DLFS240L")
      (footprint "eagle-import:PWRDI-123")
      (libsource (lib "eagle-import") (part "DIODE_SCHOTTKYPWRDI-123"))
    )
    (comp (ref "D180")
      (value "LEDLED_SFH4050")
      (footprint "eagle-import:LED_SFH4050")
      (libsource (lib "eagle-import") (part "LEDLED_SFH4050"))
    )
    (comp (ref "D181")
      (value "LEDLED_SFH4050")
      (footprint "eagle-import:LED_SFH4050")
      (libsource (lib "eagle-import") (part "LEDLED_SFH4050"))
    )
    (comp (ref "D182")
      (value "LEDLED_SFH4050")
      (footprint "eagle-import:LED_SFH4050")
      (libsource (lib "eagle-import") (part "LEDLED_SFH4050"))
    )
    (comp (ref "D183")
      (value "LEDLED_SFH4050")
      (footprint "eagle-import:LED_SFH4050")
      (libsource (lib "eagle-import") (part "LEDLED_SFH4050"))
    )
    (comp (ref "D184")
      (value "LEDLED_SFH4050")
      (footprint "eagle-import:LED_SFH4050")
      (libsource (lib "eagle-import") (part "LEDLED_SFH4050"))
    )
    (comp (ref "D185")
      (value "LEDLED_SFH4050")
      (footprint "eagle-import:LED_SFH4050")
      (libsource (lib "eagle-import") (part "LEDLED_SFH4050"))
    )
    (comp (ref "D186")
      (value "LEDLED_SFH4050")
      (footprint "eagle-import:LED_SFH4050")
      (libsource (lib "eagle-import") (part "LEDLED_SFH4050"))
    )
    (comp (ref "D187")
      (value "LEDLED_SFH4050")
      (footprint "eagle-import:LED_SFH4050")
      (libsource (lib "eagle-import") (part "LEDLED_SFH4050"))
    )
    (comp (ref "D188")
      (value "LEDLED_SFH4050")
      (footprint "eagle-import:LED_SFH4050")
      (libsource (lib "eagle-import") (part "LEDLED_SFH4050"))
    )
    (comp (ref "D189")
      (value "LEDLED_SFH4050")
      (footprint "eagle-import:LED_SFH4050")
      (libsource (lib "eagle-import") (part "LEDLED_SFH4050"))
    )
    (comp (ref "D190")
      (value "LEDLED_SFH4050")
      (footprint "eagle-import:LED_SFH4050")
      (libsource (lib "eagle-import") (part "LEDLED_SFH4050"))
    )
    (comp (ref "D191")
      (value "LEDLED_SFH4050")
      (footprint "eagle-import:LED_SFH4050")
      (libsource (lib "eagle-import") (part "LEDLED_SFH4050"))
    )
    (comp (ref "D192")
      (value "LEDLED_SFH4050")
      (footprint "eagle-import:LED_SFH4050")
      (libsource (lib "eagle-import") (part "LEDLED_SFH4050"))
    )
    (comp (ref "D193")
      (value "LEDLED_SFH4050")
      (footprint "eagle-import:LED_SFH4050")
      (libsource (lib "eagle-import") (part "LEDLED_SFH4050"))
    )
    (comp (ref "D194")
      (value "LEDLED_SFH4050")
      (footprint "eagle-import:LED_SFH4050")
      (libsource (lib "eagle-import") (part "LEDLED_SFH4050"))
    )
    (comp (ref "D195")
      (value "LEDLED_SFH4050")
      (footprint "eagle-import:LED_SFH4050")
      (libsource (lib "eagle-import") (part "LEDLED_SFH4050"))
    )
    (comp (ref "D196")
      (value "LEDLED_SFH4050")
      (footprint "eagle-import:LED_SFH4050")
      (libsource (lib "eagle-import") (part "LEDLED_SFH4050"))
    )
    (comp (ref "D197")
      (value "LEDLED_SFH4050")
      (footprint "eagle-import:LED_SFH4050")
      (libsource (lib "eagle-import") (part "LEDLED_SFH4050"))
    )
    (comp (ref "D198")
      (value "LEDLED_SFH4050")
      (footprint "eagle-import:LED_SFH4050")
      (libsource (lib "eagle-import") (part "LEDLED_SFH4050"))
    )
    (comp (ref "D199")
      (value "LEDLED_SFH4050")
      (footprint "eagle-import:LED_SFH4050")
      (libsource (lib "eagle-import") (part "LEDLED_SFH4050"))
    )
    (comp (ref "D200")
      (value "LEDLED_SFH4050")
      (footprint "eagle-import:LED_SFH4050")
      (libsource (lib "eagle-import") (part "LEDLED_SFH4050"))
    )
    (comp (ref "D201")
      (value "LEDLED_SFH4050")
      (footprint "eagle-import:LED_SFH4050")
      (libsource (lib "eagle-import") (part "LEDLED_SFH4050"))
    )
    (comp (ref "D202")
      (value "LEDLED_SFH4050")
      (footprint "eagle-import:LED_SFH4050")
      (libsource (lib "eagle-import") (part "LEDLED_SFH4050"))
    )
    (comp (ref "D203")
      (value "LEDLED_SFH4050")
      (footprint "eagle-import:LED_SFH4050")
      (libsource (lib "eagle-import") (part "LEDLED_SFH4050"))
    )
    (comp (ref "D204")
      (value "LEDLED_SFH4050")
      (footprint "eagle-import:LED_SFH4050")
      (libsource (lib "eagle-import") (part "LEDLED_SFH4050"))
    )
    (comp (ref "D205")
      (value "LEDLED_SFH4050")
      (footprint "eagle-import:LED_SFH4050")
      (libsource (lib "eagle-import") (part "LEDLED_SFH4050"))
    )
    (comp (ref "D206")
      (value "LEDLED_SFH4050")
      (footprint "eagle-import:LED_SFH4050")
      (libsource (lib "eagle-import") (part "LEDLED_SFH4050"))
    )
    (comp (ref "D207")
      (value "LEDLED_SFH4050")
      (footprint "eagle-import:LED_SFH4050")
      (libsource (lib "eagle-import") (part "LEDLED_SFH4050"))
    )
    (comp (ref "D208")
      (value "LEDLED_SFH4050")
      (footprint "eagle-import:LED_SFH4050")
      (libsource (lib "eagle-import") (part "LEDLED_SFH4050"))
    )
    (comp (ref "D209")
      (value "LEDLED_SFH4050")
      (footprint "eagle-import:LED_SFH4050")
      (libsource (lib "eagle-import") (part "LEDLED_SFH4050"))
    )
    (comp (ref "D210")
      (value "LEDLED_SFH4050")
      (footprint "eagle-import:LED_SFH4050")
      (libsource (lib "eagle-import") (part "LEDLED_SFH4050"))
    )
    (comp (ref "D211")
      (value "LEDLED_SFH4050")
      (footprint "eagle-import:LED_SFH4050")
      (libsource (lib "eagle-import") (part "LEDLED_SFH4050"))
    )
    (comp (ref "D212")
      (value "DLFS240L")
      (footprint "eagle-import:PWRDI-123")
      (libsource (lib "eagle-import") (part "DIODE_SCHOTTKYPWRDI-123"))
    )
    (comp (ref "D213")
      (value "LEDLED_SFH4050")
      (footprint "eagle-import:LED_SFH4050")
      (libsource (lib "eagle-import") (part "LEDLED_SFH4050"))
    )
    (comp (ref "D214")
      (value "LEDLED_SFH4050")
      (footprint "eagle-import:LED_SFH4050")
      (libsource (lib "eagle-import") (part "LEDLED_SFH4050"))
    )
    (comp (ref "D215")
      (value "LEDLED_SFH4050")
      (footprint "eagle-import:LED_SFH4050")
      (libsource (lib "eagle-import") (part "LEDLED_SFH4050"))
    )
    (comp (ref "D216")
      (value "LEDLED_SFH4050")
      (footprint "eagle-import:LED_SFH4050")
      (libsource (lib "eagle-import") (part "LEDLED_SFH4050"))
    )
    (comp (ref "D217")
      (value "LEDLED_SFH4050")
      (footprint "eagle-import:LED_SFH4050")
      (libsource (lib "eagle-import") (part "LEDLED_SFH4050"))
    )
    (comp (ref "D218")
      (value "LEDLED_SFH4050")
      (footprint "eagle-import:LED_SFH4050")
      (libsource (lib "eagle-import") (part "LEDLED_SFH4050"))
    )
    (comp (ref "D219")
      (value "LEDLED_SFH4050")
      (footprint "eagle-import:LED_SFH4050")
      (libsource (lib "eagle-import") (part "LEDLED_SFH4050"))
    )
    (comp (ref "D220")
      (value "LEDLED_SFH4050")
      (footprint "eagle-import:LED_SFH4050")
      (libsource (lib "eagle-import") (part "LEDLED_SFH4050"))
    )
    (comp (ref "D221")
      (value "LEDLED_SFH4050")
      (footprint "eagle-import:LED_SFH4050")
      (libsource (lib "eagle-import") (part "LEDLED_SFH4050"))
    )
    (comp (ref "D222")
      (value "LEDLED_SFH4050")
      (footprint "eagle-import:LED_SFH4050")
      (libsource (lib "eagle-import") (part "LEDLED_SFH4050"))
    )
    (comp (ref "D223")
      (value "LEDLED_SFH4050")
      (footprint "eagle-import:LED_SFH4050")
      (libsource (lib "eagle-import") (part "LEDLED_SFH4050"))
    )
    (comp (ref "D224")
      (value "LEDLED_SFH4050")
      (footprint "eagle-import:LED_SFH4050")
      (libsource (lib "eagle-import") (part "LEDLED_SFH4050"))
    )
    (comp (ref "D225")
      (value "LEDLED_SFH4050")
      (footprint "eagle-import:LED_SFH4050")
      (libsource (lib "eagle-import") (part "LEDLED_SFH4050"))
    )
    (comp (ref "D226")
      (value "LEDLED_SFH4050")
      (footprint "eagle-import:LED_SFH4050")
      (libsource (lib "eagle-import") (part "LEDLED_SFH4050"))
    )
    (comp (ref "D227")
      (value "LEDLED_SFH4050")
      (footprint "eagle-import:LED_SFH4050")
      (libsource (lib "eagle-import") (part "LEDLED_SFH4050"))
    )
    (comp (ref "D228")
      (value "LEDLED_SFH4050")
      (footprint "eagle-import:LED_SFH4050")
      (libsource (lib "eagle-import") (part "LEDLED_SFH4050"))
    )
    (comp (ref "D229")
      (value "LEDLED_SFH4050")
      (footprint "eagle-import:LED_SFH4050")
      (libsource (lib "eagle-import") (part "LEDLED_SFH4050"))
    )
    (comp (ref "D230")
      (value "LEDLED_SFH4050")
      (footprint "eagle-import:LED_SFH4050")
      (libsource (lib "eagle-import") (part "LEDLED_SFH4050"))
    )
    (comp (ref "D231")
      (value "LEDLED_SFH4050")
      (footprint "eagle-import:LED_SFH4050")
      (libsource (lib "eagle-import") (part "LEDLED_SFH4050"))
    )
    (comp (ref "D232")
      (value "LEDLED_SFH4050")
      (footprint "eagle-import:LED_SFH4050")
      (libsource (lib "eagle-import") (part "LEDLED_SFH4050"))
    )
    (comp (ref "D233")
      (value "LEDLED_SFH4050")
      (footprint "eagle-import:LED_SFH4050")
      (libsource (lib "eagle-import") (part "LEDLED_SFH4050"))
    )
    (comp (ref "D234")
      (value "LEDLED_SFH4050")
      (footprint "eagle-import:LED_SFH4050")
      (libsource (lib "eagle-import") (part "LEDLED_SFH4050"))
    )
    (comp (ref "D235")
      (value "LEDLED_SFH4050")
      (footprint "eagle-import:LED_SFH4050")
      (libsource (lib "eagle-import") (part "LEDLED_SFH4050"))
    )
    (comp (ref "D236")
      (value "LEDLED_SFH4050")
      (footprint "eagle-import:LED_SFH4050")
      (libsource (lib "eagle-import") (part "LEDLED_SFH4050"))
    )
    (comp (ref "D237")
      (value "LEDLED_SFH4050")
      (footprint "eagle-import:LED_SFH4050")
      (libsource (lib "eagle-import") (part "LEDLED_SFH4050"))
    )
    (comp (ref "D238")
      (value "LEDLED_SFH4050")
      (footprint "eagle-import:LED_SFH4050")
      (libsource (lib "eagle-import") (part "LEDLED_SFH4050"))
    )
    (comp (ref "D239")
      (value "LEDLED_SFH4050")
      (footprint "eagle-import:LED_SFH4050")
      (libsource (lib "eagle-import") (part "LEDLED_SFH4050"))
    )
    (comp (ref "D240")
      (value "LEDLED_SFH4050")
      (footprint "eagle-import:LED_SFH4050")
      (libsource (lib "eagle-import") (part "LEDLED_SFH4050"))
    )
    (comp (ref "D241")
      (value "LEDLED_SFH4050")
      (footprint "eagle-import:LED_SFH4050")
      (libsource (lib "eagle-import") (part "LEDLED_SFH4050"))
    )
    (comp (ref "D242")
      (value "LEDLED_SFH4050")
      (footprint "eagle-import:LED_SFH4050")
      (libsource (lib "eagle-import") (part "LEDLED_SFH4050"))
    )
    (comp (ref "D243")
      (value "LEDLED_SFH4050")
      (footprint "eagle-import:LED_SFH4050")
      (libsource (lib "eagle-import") (part "LEDLED_SFH4050"))
    )
    (comp (ref "D244")
      (value "LEDLED_SFH4050")
      (footprint "eagle-import:LED_SFH4050")
      (libsource (lib "eagle-import") (part "LEDLED_SFH4050"))
    )
    (comp (ref "D245")
      (value "LEDLED_SFH4050")
      (footprint "eagle-import:LED_SFH4050")
      (libsource (lib "eagle-import") (part "LEDLED_SFH4050"))
    )
    (comp (ref "D246")
      (value "LEDLED_SFH4050")
      (footprint "eagle-import:LED_SFH4050")
      (libsource (lib "eagle-import") (part "LEDLED_SFH4050"))
    )
    (comp (ref "D247")
      (value "LEDLED_SFH4050")
      (footprint "eagle-import:LED_SFH4050")
      (libsource (lib "eagle-import") (part "LEDLED_SFH4050"))
    )
    (comp (ref "D248")
      (value "LEDLED_SFH4050")
      (footprint "eagle-import:LED_SFH4050")
      (libsource (lib "eagle-import") (part "LEDLED_SFH4050"))
    )
    (comp (ref "D249")
      (value "LEDLED_SFH4050")
      (footprint "eagle-import:LED_SFH4050")
      (libsource (lib "eagle-import") (part "LEDLED_SFH4050"))
    )
    (comp (ref "D250")
      (value "LEDLED_SFH4050")
      (footprint "eagle-import:LED_SFH4050")
      (libsource (lib "eagle-import") (part "LEDLED_SFH4050"))
    )
    (comp (ref "D251")
      (value "LEDLED_SFH4050")
      (footprint "eagle-import:LED_SFH4050")
      (libsource (lib "eagle-import") (part "LEDLED_SFH4050"))
    )
    (comp (ref "D252")
      (value "LEDLED_SFH4050")
      (footprint "eagle-import:LED_SFH4050")
      (libsource (lib "eagle-import") (part "LEDLED_SFH4050"))
    )
    (comp (ref "D253")
      (value "LEDLED_SFH4050")
      (footprint "eagle-import:LED_SFH4050")
      (libsource (lib "eagle-import") (part "LEDLED_SFH4050"))
    )
    (comp (ref "D254")
      (value "LEDLED_SFH4050")
      (footprint "eagle-import:LED_SFH4050")
      (libsource (lib "eagle-import") (part "LEDLED_SFH4050"))
    )
    (comp (ref "D255")
      (value "LEDLED_SFH4050")
      (footprint "eagle-import:LED_SFH4050")
      (libsource (lib "eagle-import") (part "LEDLED_SFH4050"))
    )
    (comp (ref "D256")
      (value "LEDLED_SFH4050")
      (footprint "eagle-import:LED_SFH4050")
      (libsource (lib "eagle-import") (part "LEDLED_SFH4050"))
    )
    (comp (ref "D257")
      (value "LEDLED_SFH4050")
      (footprint "eagle-import:LED_SFH4050")
      (libsource (lib "eagle-import") (part "LEDLED_SFH4050"))
    )
    (comp (ref "D258")
      (value "LEDLED_SFH4050")
      (footprint "eagle-import:LED_SFH4050")
      (libsource (lib "eagle-import") (part "LEDLED_SFH4050"))
    )
    (comp (ref "D259")
      (value "LEDLED_SFH4050")
      (footprint "eagle-import:LED_SFH4050")
      (libsource (lib "eagle-import") (part "LEDLED_SFH4050"))
    )
    (comp (ref "D260")
      (value "LEDLED_SFH4050")
      (footprint "eagle-import:LED_SFH4050")
      (libsource (lib "eagle-import") (part "LEDLED_SFH4050"))
    )
    (comp (ref "GRN33")
      (value "SP-GRN")
      (footprint "eagle-import:SUNPLUS-LED")
      (libsource (lib "eagle-import") (part "LED-TH"))
    )
    (comp (ref "GRN34")
      (value "SP-GRN")
      (footprint "eagle-import:SUNPLUS-LED")
      (libsource (lib "eagle-import") (part "LED-TH"))
    )
    (comp (ref "GRN35")
      (value "SP-GRN")
      (footprint "eagle-import:SUNPLUS-LED")
      (libsource (lib "eagle-import") (part "LED-TH"))
    )
    (comp (ref "GRN36")
      (value "SP-GRN")
      (footprint "eagle-import:SUNPLUS-LED")
      (libsource (lib "eagle-import") (part "LED-TH"))
    )
    (comp (ref "GRN37")
      (value "SP-GRN")
      (footprint "eagle-import:SUNPLUS-LED")
      (libsource (lib "eagle-import") (part "LED-TH"))
    )
    (comp (ref "GRN38")
      (value "SP-GRN")
      (footprint "eagle-import:SUNPLUS-LED")
      (libsource (lib "eagle-import") (part "LED-TH"))
    )
    (comp (ref "GRN39")
      (value "SP-GRN")
      (footprint "eagle-import:SUNPLUS-LED")
      (libsource (lib "eagle-import") (part "LED-TH"))
    )
    (comp (ref "GRN40")
      (value "SP-GRN")
      (footprint "eagle-import:SUNPLUS-LED")
      (libsource (lib "eagle-import") (part "LED-TH"))
    )
    (comp (ref "GRN41")
      (value "SP-GRN")
      (footprint "eagle-import:SUNPLUS-LED")
      (libsource (lib "eagle-import") (part "LED-TH"))
    )
    (comp (ref "GRN42")
      (value "SP-GRN")
      (footprint "eagle-import:SUNPLUS-LED")
      (libsource (lib "eagle-import") (part "LED-TH"))
    )
    (comp (ref "GRN43")
      (value "SP-GRN")
      (footprint "eagle-import:SUNPLUS-LED")
      (libsource (lib "eagle-import") (part "LED-TH"))
    )
    (comp (ref "GRN44")
      (value "SP-GRN")
      (footprint "eagle-import:SUNPLUS-LED")
      (libsource (lib "eagle-import") (part "LED-TH"))
    )
    (comp (ref "GRN45")
      (value "SP-GRN")
      (footprint "eagle-import:SUNPLUS-LED")
      (libsource (lib "eagle-import") (part "LED-TH"))
    )
    (comp (ref "GRN46")
      (value "SP-GRN")
      (footprint "eagle-import:SUNPLUS-LED")
      (libsource (lib "eagle-import") (part "LED-TH"))
    )
    (comp (ref "GRN47")
      (value "SP-GRN")
      (footprint "eagle-import:SUNPLUS-LED")
      (libsource (lib "eagle-import") (part "LED-TH"))
    )
    (comp (ref "GRN48")
      (value "SP-GRN")
      (footprint "eagle-import:SUNPLUS-LED")
      (libsource (lib "eagle-import") (part "LED-TH"))
    )
    (comp (ref "GRN49")
      (value "SP-GRN")
      (footprint "eagle-import:SUNPLUS-LED")
      (libsource (lib "eagle-import") (part "LED-TH"))
    )
    (comp (ref "GRN50")
      (value "SP-GRN")
      (footprint "eagle-import:SUNPLUS-LED")
      (libsource (lib "eagle-import") (part "LED-TH"))
    )
    (comp (ref "GRN51")
      (value "SP-GRN")
      (footprint "eagle-import:SUNPLUS-LED")
      (libsource (lib "eagle-import") (part "LED-TH"))
    )
    (comp (ref "GRN52")
      (value "SP-GRN")
      (footprint "eagle-import:SUNPLUS-LED")
      (libsource (lib "eagle-import") (part "LED-TH"))
    )
    (comp (ref "GRN53")
      (value "SP-GRN")
      (footprint "eagle-import:SUNPLUS-LED")
      (libsource (lib "eagle-import") (part "LED-TH"))
    )
    (comp (ref "GRN54")
      (value "SP-GRN")
      (footprint "eagle-import:SUNPLUS-LED")
      (libsource (lib "eagle-import") (part "LED-TH"))
    )
    (comp (ref "GRN55")
      (value "SP-GRN")
      (footprint "eagle-import:SUNPLUS-LED")
      (libsource (lib "eagle-import") (part "LED-TH"))
    )
    (comp (ref "GRN56")
      (value "SP-GRN")
      (footprint "eagle-import:SUNPLUS-LED")
      (libsource (lib "eagle-import") (part "LED-TH"))
    )
    (comp (ref "GRN57")
      (value "SP-GRN")
      (footprint "eagle-import:SUNPLUS-LED")
      (libsource (lib "eagle-import") (part "LED-TH"))
    )
    (comp (ref "GRN58")
      (value "SP-GRN")
      (footprint "eagle-import:SUNPLUS-LED")
      (libsource (lib "eagle-import") (part "LED-TH"))
    )
    (comp (ref "GRN59")
      (value "SP-GRN")
      (footprint "eagle-import:SUNPLUS-LED")
      (libsource (lib "eagle-import") (part "LED-TH"))
    )
    (comp (ref "GRN60")
      (value "SP-GRN")
      (footprint "eagle-import:SUNPLUS-LED")
      (libsource (lib "eagle-import") (part "LED-TH"))
    )
    (comp (ref "GRN61")
      (value "SP-GRN")
      (footprint "eagle-import:SUNPLUS-LED")
      (libsource (lib "eagle-import") (part "LED-TH"))
    )
    (comp (ref "GRN62")
      (value "SP-GRN")
      (footprint "eagle-import:SUNPLUS-LED")
      (libsource (lib "eagle-import") (part "LED-TH"))
    )
    (comp (ref "GRN63")
      (value "SP-GRN")
      (footprint "eagle-import:SUNPLUS-LED")
      (libsource (lib "eagle-import") (part "LED-TH"))
    )
    (comp (ref "GRN64")
      (value "SP-GRN")
      (footprint "eagle-import:SUNPLUS-LED")
      (libsource (lib "eagle-import") (part "LED-TH"))
    )
    (comp (ref "J1")
      (value "POWER_JACK_SHUNTPJ-002")
      (footprint "eagle-import:PJ-002")
      (libsource (lib "eagle-import") (part "POWER_JACK_SHUNTPJ-002"))
    )
    (comp (ref "JMP3")
      (value "JUMPER5100")
      (footprint "eagle-import:5100")
      (libsource (lib "eagle-import") (part "JUMPER5100"))
    )
    (comp (ref "JMP8")
      (value "JUMPER5100")
      (footprint "eagle-import:5100")
      (libsource (lib "eagle-import") (part "JUMPER5100"))
    )
    (comp (ref "JMP9")
      (value "JUMPER5100")
      (footprint "eagle-import:5100")
      (libsource (lib "eagle-import") (part "JUMPER5100"))
    )
    (comp (ref "JMP10")
      (value "JUMPER5100")
      (footprint "eagle-import:5100")
      (libsource (lib "eagle-import") (part "JUMPER5100"))
    )
    (comp (ref "JMP11")
      (value "JUMPER5100")
      (footprint "eagle-import:5100")
      (libsource (lib "eagle-import") (part "JUMPER5100"))
    )
    (comp (ref "JMP12")
      (value "JUMPER5100")
      (footprint "eagle-import:5100")
      (libsource (lib "eagle-import") (part "JUMPER5100"))
    )
    (comp (ref "JMP13")
      (value "JUMPER5100")
      (footprint "eagle-import:5100")
      (libsource (lib "eagle-import") (part "JUMPER5100"))
    )
    (comp (ref "JMP16")
      (value "JUMPER5100")
      (footprint "eagle-import:5100")
      (libsource (lib "eagle-import") (part "JUMPER5100"))
    )
    (comp (ref "JMP17")
      (value "JUMPER5100")
      (footprint "eagle-import:5100")
      (libsource (lib "eagle-import") (part "JUMPER5100"))
    )
    (comp (ref "L3")
      (value "68uH/1A")
      (footprint "eagle-import:SRU8043")
      (libsource (lib "eagle-import") (part "INDUCTOR_SMSRU8043"))
    )
    (comp (ref "L4")
      (value "68uH/1A")
      (footprint "eagle-import:SRU8043")
      (libsource (lib "eagle-import") (part "INDUCTOR_SMSRU8043"))
    )
    (comp (ref "P2")
      (value "CON162X8SM-SMALL")
      (footprint "eagle-import:HEADER2X8_SM_SMALL")
      (libsource (lib "eagle-import") (part "CON162X8SM-SMALL"))
    )
    (comp (ref "Q7")
      (value "NPN_DUAL")
      (footprint "eagle-import:LFPAK56D")
      (libsource (lib "eagle-import") (part "NPN_DUAL"))
    )
    (comp (ref "Q8")
      (value "NPN_DUAL")
      (footprint "eagle-import:LFPAK56D")
      (libsource (lib "eagle-import") (part "NPN_DUAL"))
    )
    (comp (ref "Q9")
      (value "NPN_DUAL")
      (footprint "eagle-import:LFPAK56D")
      (libsource (lib "eagle-import") (part "NPN_DUAL"))
    )
    (comp (ref "Q10")
      (value "NPN_DUAL")
      (footprint "eagle-import:LFPAK56D")
      (libsource (lib "eagle-import") (part "NPN_DUAL"))
    )
    (comp (ref "Q11")
      (value "NPN_DUAL")
      (footprint "eagle-import:LFPAK56D")
      (libsource (lib "eagle-import") (part "NPN_DUAL"))
    )
    (comp (ref "Q12")
      (value "NPN_DUAL")
      (footprint "eagle-import:LFPAK56D")
      (libsource (lib "eagle-import") (part "NPN_DUAL"))
    )
    (comp (ref "R35")
      (value "10R0")
      (footprint "eagle-import:1206S")
      (libsource (lib "eagle-import") (part "RESISTOR_SM1206S"))
    )
    (comp (ref "R36")
      (value "10K0")
      (footprint "eagle-import:1206S")
      (libsource (lib "eagle-import") (part "RESISTOR_SM1206S"))
    )
    (comp (ref "R37")
      (value "4R99")
      (footprint "eagle-import:R2512")
      (libsource (lib "eagle-import") (part "R-US_R2512"))
    )
    (comp (ref "R38")
      (value "10R0")
      (footprint "eagle-import:1206S")
      (libsource (lib "eagle-import") (part "RESISTOR_SM1206S"))
    )
    (comp (ref "R39")
      (value "4R99")
      (footprint "eagle-import:R2512")
      (libsource (lib "eagle-import") (part "R-US_R2512"))
    )
    (comp (ref "R40")
      (value "0R0")
      (footprint "eagle-import:1206S")
      (libsource (lib "eagle-import") (part "RESISTOR_SM1206S"))
    )
    (comp (ref "R41")
      (value "4R99")
      (footprint "eagle-import:R2512")
      (libsource (lib "eagle-import") (part "R-US_R2512"))
    )
    (comp (ref "R42")
      (value "10K0")
      (footprint "eagle-import:1206S")
      (libsource (lib "eagle-import") (part "RESISTOR_SM1206S"))
    )
    (comp (ref "R43")
      (value "10R0")
      (footprint "eagle-import:1206S")
      (libsource (lib "eagle-import") (part "RESISTOR_SM1206S"))
    )
    (comp (ref "R44")
      (value "4R99")
      (footprint "eagle-import:R2512")
      (libsource (lib "eagle-import") (part "R-US_R2512"))
    )
    (comp (ref "R45")
      (value "4R99")
      (footprint "eagle-import:R2512")
      (libsource (lib "eagle-import") (part "R-US_R2512"))
    )
    (comp (ref "R46")
      (value "10R0")
      (footprint "eagle-import:1206S")
      (libsource (lib "eagle-import") (part "RESISTOR_SM1206S"))
    )
    (comp (ref "R47")
      (value "4R99")
      (footprint "eagle-import:R2512")
      (libsource (lib "eagle-import") (part "R-US_R2512"))
    )
    (comp (ref "R48")
      (value "4.99K")
      (footprint "eagle-import:0805S")
      (libsource (lib "eagle-import") (part "RESISTOR_SM0805S"))
    )
    (comp (ref "R50")
      (value "1R00")
      (footprint "eagle-import:1206S")
      (libsource (lib "eagle-import") (part "RESISTOR_SM1206S"))
    )
    (comp (ref "R51")
      (value "0R0")
      (footprint "eagle-import:1206S")
      (libsource (lib "eagle-import") (part "RESISTOR_SM1206S"))
    )
    (comp (ref "R52")
      (value "0R0")
      (footprint "eagle-import:1206S")
      (libsource (lib "eagle-import") (part "RESISTOR_SM1206S"))
    )
    (comp (ref "R53")
      (value "1R00")
      (footprint "eagle-import:1206S")
      (libsource (lib "eagle-import") (part "RESISTOR_SM1206S"))
    )
    (comp (ref "R54")
      (value "4.99K")
      (footprint "eagle-import:0805S")
      (libsource (lib "eagle-import") (part "RESISTOR_SM0805S"))
    )
    (comp (ref "R55")
      (value "0R0")
      (footprint "eagle-import:1206S")
      (libsource (lib "eagle-import") (part "RESISTOR_SM1206S"))
    )
    (comp (ref "R56")
      (value "4R99")
      (footprint "eagle-import:R2512")
      (libsource (lib "eagle-import") (part "R-US_R2512"))
    )
    (comp (ref "R57")
      (value "10R0")
      (footprint "eagle-import:1206S")
      (libsource (lib "eagle-import") (part "RESISTOR_SM1206S"))
    )
    (comp (ref "R58")
      (value "4R99")
      (footprint "eagle-import:R2512")
      (libsource (lib "eagle-import") (part "R-US_R2512"))
    )
    (comp (ref "R59")
      (value "4R99")
      (footprint "eagle-import:R2512")
      (libsource (lib "eagle-import") (part "R-US_R2512"))
    )
    (comp (ref "R60")
      (value "10R0")
      (footprint "eagle-import:1206S")
      (libsource (lib "eagle-import") (part "RESISTOR_SM1206S"))
    )
    (comp (ref "R61")
      (value "4R99")
      (footprint "eagle-import:R2512")
      (libsource (lib "eagle-import") (part "R-US_R2512"))
    )
    (comp (ref "R62")
      (value "0R0")
      (footprint "eagle-import:1206S")
      (libsource (lib "eagle-import") (part "RESISTOR_SM1206S"))
    )
    (comp (ref "R63")
      (value "4R99")
      (footprint "eagle-import:R2512")
      (libsource (lib "eagle-import") (part "R-US_R2512"))
    )
    (comp (ref "R64")
      (value "10R0")
      (footprint "eagle-import:1206S")
      (libsource (lib "eagle-import") (part "RESISTOR_SM1206S"))
    )
    (comp (ref "R65")
      (value "0R0")
      (footprint "eagle-import:1206S")
      (libsource (lib "eagle-import") (part "RESISTOR_SM1206S"))
    )
    (comp (ref "R66")
      (value "4R99")
      (footprint "eagle-import:R2512")
      (libsource (lib "eagle-import") (part "R-US_R2512"))
    )
    (comp (ref "R67")
      (value "10R0")
      (footprint "eagle-import:1206S")
      (libsource (lib "eagle-import") (part "RESISTOR_SM1206S"))
    )
    (comp (ref "R68")
      (value "0R0")
      (footprint "eagle-import:1206S")
      (libsource (lib "eagle-import") (part "RESISTOR_SM1206S"))
    )
    (comp (ref "RED33")
      (value "SP-RED")
      (footprint "eagle-import:SUNPLUS-LED")
      (libsource (lib "eagle-import") (part "LED-TH"))
    )
    (comp (ref "RED34")
      (value "SP-RED")
      (footprint "eagle-import:SUNPLUS-LED")
      (libsource (lib "eagle-import") (part "LED-TH"))
    )
    (comp (ref "RED35")
      (value "SP-RED")
      (footprint "eagle-import:SUNPLUS-LED")
      (libsource (lib "eagle-import") (part "LED-TH"))
    )
    (comp (ref "RED36")
      (value "SP-RED")
      (footprint "eagle-import:SUNPLUS-LED")
      (libsource (lib "eagle-import") (part "LED-TH"))
    )
    (comp (ref "RED37")
      (value "SP-RED")
      (footprint "eagle-import:SUNPLUS-LED")
      (libsource (lib "eagle-import") (part "LED-TH"))
    )
    (comp (ref "RED38")
      (value "SP-RED")
      (footprint "eagle-import:SUNPLUS-LED")
      (libsource (lib "eagle-import") (part "LED-TH"))
    )
    (comp (ref "RED39")
      (value "SP-RED")
      (footprint "eagle-import:SUNPLUS-LED")
      (libsource (lib "eagle-import") (part "LED-TH"))
    )
    (comp (ref "RED40")
      (value "SP-RED")
      (footprint "eagle-import:SUNPLUS-LED")
      (libsource (lib "eagle-import") (part "LED-TH"))
    )
    (comp (ref "RED41")
      (value "SP-RED")
      (footprint "eagle-import:SUNPLUS-LED")
      (libsource (lib "eagle-import") (part "LED-TH"))
    )
    (comp (ref "RED42")
      (value "SP-RED")
      (footprint "eagle-import:SUNPLUS-LED")
      (libsource (lib "eagle-import") (part "LED-TH"))
    )
    (comp (ref "RED43")
      (value "SP-RED")
      (footprint "eagle-import:SUNPLUS-LED")
      (libsource (lib "eagle-import") (part "LED-TH"))
    )
    (comp (ref "RED44")
      (value "SP-RED")
      (footprint "eagle-import:SUNPLUS-LED")
      (libsource (lib "eagle-import") (part "LED-TH"))
    )
    (comp (ref "RED45")
      (value "SP-RED")
      (footprint "eagle-import:SUNPLUS-LED")
      (libsource (lib "eagle-import") (part "LED-TH"))
    )
    (comp (ref "RED46")
      (value "SP-RED")
      (footprint "eagle-import:SUNPLUS-LED")
      (libsource (lib "eagle-import") (part "LED-TH"))
    )
    (comp (ref "RED47")
      (value "SP-RED")
      (footprint "eagle-import:SUNPLUS-LED")
      (libsource (lib "eagle-import") (part "LED-TH"))
    )
    (comp (ref "RED48")
      (value "SP-RED")
      (footprint "eagle-import:SUNPLUS-LED")
      (libsource (lib "eagle-import") (part "LED-TH"))
    )
    (comp (ref "RED49")
      (value "SP-RED")
      (footprint "eagle-import:SUNPLUS-LED")
      (libsource (lib "eagle-import") (part "LED-TH"))
    )
    (comp (ref "RED50")
      (value "SP-RED")
      (footprint "eagle-import:SUNPLUS-LED")
      (libsource (lib "eagle-import") (part "LED-TH"))
    )
    (comp (ref "RED51")
      (value "SP-RED")
      (footprint "eagle-import:SUNPLUS-LED")
      (libsource (lib "eagle-import") (part "LED-TH"))
    )
    (comp (ref "RED52")
      (value "SP-RED")
      (footprint "eagle-import:SUNPLUS-LED")
      (libsource (lib "eagle-import") (part "LED-TH"))
    )
    (comp (ref "RED53")
      (value "SP-RED")
      (footprint "eagle-import:SUNPLUS-LED")
      (libsource (lib "eagle-import") (part "LED-TH"))
    )
    (comp (ref "RED54")
      (value "SP-RED")
      (footprint "eagle-import:SUNPLUS-LED")
      (libsource (lib "eagle-import") (part "LED-TH"))
    )
    (comp (ref "RED55")
      (value "SP-RED")
      (footprint "eagle-import:SUNPLUS-LED")
      (libsource (lib "eagle-import") (part "LED-TH"))
    )
    (comp (ref "RED56")
      (value "SP-RED")
      (footprint "eagle-import:SUNPLUS-LED")
      (libsource (lib "eagle-import") (part "LED-TH"))
    )
    (comp (ref "RED57")
      (value "SP-RED")
      (footprint "eagle-import:SUNPLUS-LED")
      (libsource (lib "eagle-import") (part "LED-TH"))
    )
    (comp (ref "RED58")
      (value "SP-RED")
      (footprint "eagle-import:SUNPLUS-LED")
      (libsource (lib "eagle-import") (part "LED-TH"))
    )
    (comp (ref "RED59")
      (value "SP-RED")
      (footprint "eagle-import:SUNPLUS-LED")
      (libsource (lib "eagle-import") (part "LED-TH"))
    )
    (comp (ref "RED60")
      (value "SP-RED")
      (footprint "eagle-import:SUNPLUS-LED")
      (libsource (lib "eagle-import") (part "LED-TH"))
    )
    (comp (ref "RED61")
      (value "SP-RED")
      (footprint "eagle-import:SUNPLUS-LED")
      (libsource (lib "eagle-import") (part "LED-TH"))
    )
    (comp (ref "RED62")
      (value "SP-RED")
      (footprint "eagle-import:SUNPLUS-LED")
      (libsource (lib "eagle-import") (part "LED-TH"))
    )
    (comp (ref "RED63")
      (value "SP-RED")
      (footprint "eagle-import:SUNPLUS-LED")
      (libsource (lib "eagle-import") (part "LED-TH"))
    )
    (comp (ref "RED64")
      (value "SP-RED")
      (footprint "eagle-import:SUNPLUS-LED")
      (libsource (lib "eagle-import") (part "LED-TH"))
    )
    (comp (ref "U$19")
      (value "JFRC-LOGOLOGO_OP")
      (footprint "eagle-import:LOGO_BMP_OP")
      (libsource (lib "eagle-import") (part "JFRC-LOGOLOGO_OP"))
    )
    (comp (ref "U3")
      (value "AP8802")
      (footprint "eagle-import:SOIC8-EP")
      (libsource (lib "eagle-import") (part "AP8802"))
    )
    (comp (ref "U4")
      (value "AP8802")
      (footprint "eagle-import:SOIC8-EP")
      (libsource (lib "eagle-import") (part "AP8802"))
    )
  )
  (nets
    (net (code "1") (name "BLU1") (class "Default")
      (node (ref "P1") (pin "16") (pinfunction "16_16") (pintype "bidirectional"))
      (node (ref "Q1") (pin "4") (pinfunction "B2_4") (pintype "bidirectional"))
      (node (ref "R2") (pin "1") (pinfunction "1_1") (pintype "passive"))
    )
    (net (code "2") (name "BLU1F") (class "Default")
      (node (ref "P1") (pin "14") (pinfunction "14_14") (pintype "bidirectional"))
      (node (ref "Q1") (pin "3") (pinfunction "E2_3") (pintype "bidirectional"))
      (node (ref "R5") (pin "2") (pinfunction "2_2") (pintype "passive"))
    )
    (net (code "3") (name "BLU1K") (class "Default")
      (node (ref "BLU1") (pin "GC") (pinfunction "K_GC") (pintype "bidirectional"))
      (node (ref "Q1") (pin "7") (pinfunction "C1_7") (pintype "bidirectional"))
      (node (ref "Q1") (pin "78") (pinfunction "C1_78") (pintype "bidirectional"))
      (node (ref "Q1") (pin "8") (pinfunction "C1_8") (pintype "bidirectional"))
    )
    (net (code "4") (name "BLU1K2") (class "Default")
      (node (ref "BLU9") (pin "GC") (pinfunction "K_GC") (pintype "bidirectional"))
      (node (ref "Q1") (pin "5") (pinfunction "C2_5") (pintype "bidirectional"))
      (node (ref "Q1") (pin "56") (pinfunction "C2_56") (pintype "bidirectional"))
      (node (ref "Q1") (pin "6") (pinfunction "C2_6") (pintype "bidirectional"))
    )
    (net (code "5") (name "BLU2") (class "Default")
      (node (ref "P1") (pin "3") (pinfunction "3_3") (pintype "bidirectional"))
      (node (ref "Q4") (pin "2") (pinfunction "B1_2") (pintype "bidirectional"))
      (node (ref "R28") (pin "2") (pinfunction "2_2") (pintype "passive"))
    )
    (net (code "6") (name "BLU2F") (class "Default")
      (node (ref "P1") (pin "5") (pinfunction "5_5") (pintype "bidirectional"))
      (node (ref "Q4") (pin "1") (pinfunction "E1_1") (pintype "bidirectional"))
      (node (ref "R22") (pin "2") (pinfunction "2_2") (pintype "passive"))
    )
    (net (code "7") (name "BLU2K1") (class "Default")
      (node (ref "BLU17") (pin "GC") (pinfunction "K_GC") (pintype "bidirectional"))
      (node (ref "Q4") (pin "7") (pinfunction "C1_7") (pintype "bidirectional"))
      (node (ref "Q4") (pin "78") (pinfunction "C1_78") (pintype "bidirectional"))
      (node (ref "Q4") (pin "8") (pinfunction "C1_8") (pintype "bidirectional"))
    )
    (net (code "8") (name "BLU2K2") (class "Default")
      (node (ref "BLU25") (pin "GC") (pinfunction "K_GC") (pintype "bidirectional"))
      (node (ref "Q4") (pin "5") (pinfunction "C2_5") (pintype "bidirectional"))
      (node (ref "Q4") (pin "56") (pinfunction "C2_56") (pintype "bidirectional"))
      (node (ref "Q4") (pin "6") (pinfunction "C2_6") (pintype "bidirectional"))
    )
    (net (code "9") (name "BLU3") (class "Default")
      (node (ref "P2") (pin "16") (pinfunction "16_16") (pintype "bidirectional"))
      (node (ref "Q7") (pin "4") (pinfunction "B2_4") (pintype "bidirectional"))
      (node (ref "R36") (pin "1") (pinfunction "1_1") (pintype "passive"))
    )
    (net (code "10") (name "BLU3F") (class "Default")
      (node (ref "P2") (pin "14") (pinfunction "14_14") (pintype "bidirectional"))
      (node (ref "Q7") (pin "3") (pinfunction "E2_3") (pintype "bidirectional"))
      (node (ref "R39") (pin "2") (pinfunction "2_2") (pintype "passive"))
    )
    (net (code "11") (name "BLU4") (class "Default")
      (node (ref "P2") (pin "3") (pinfunction "3_3") (pintype "bidirectional"))
      (node (ref "Q10") (pin "2") (pinfunction "B1_2") (pintype "bidirectional"))
      (node (ref "R62") (pin "2") (pinfunction "2_2") (pintype "passive"))
    )
    (net (code "12") (name "BLU4F") (class "Default")
      (node (ref "P2") (pin "5") (pinfunction "5_5") (pintype "bidirectional"))
      (node (ref "Q10") (pin "1") (pinfunction "E1_1") (pintype "bidirectional"))
      (node (ref "R56") (pin "2") (pinfunction "2_2") (pintype "passive"))
    )
    (net (code "13") (name "GRN1") (class "Default")
      (node (ref "P1") (pin "15") (pinfunction "15_15") (pintype "bidirectional"))
      (node (ref "Q2") (pin "4") (pinfunction "B2_4") (pintype "bidirectional"))
      (node (ref "R6") (pin "1") (pinfunction "1_1") (pintype "passive"))
    )
    (net (code "14") (name "GRN1F") (class "Default")
      (node (ref "P1") (pin "13") (pinfunction "13_13") (pintype "bidirectional"))
      (node (ref "Q2") (pin "3") (pinfunction "E2_3") (pintype "bidirectional"))
      (node (ref "R10") (pin "2") (pinfunction "2_2") (pintype "passive"))
    )
    (net (code "15") (name "GRN1K") (class "Default")
      (node (ref "GRN1") (pin "GC") (pinfunction "K_GC") (pintype "bidirectional"))
      (node (ref "JMP1") (pin "1") (pinfunction "1_1") (pintype "bidirectional"))
    )
    (net (code "16") (name "GRN1K2") (class "Default")
      (node (ref "GRN9") (pin "GC") (pinfunction "K_GC") (pintype "bidirectional"))
      (node (ref "Q2") (pin "5") (pinfunction "C2_5") (pintype "bidirectional"))
      (node (ref "Q2") (pin "56") (pinfunction "C2_56") (pintype "bidirectional"))
      (node (ref "Q2") (pin "6") (pinfunction "C2_6") (pintype "bidirectional"))
    )
    (net (code "17") (name "GRN2") (class "Default")
      (node (ref "P1") (pin "2") (pinfunction "2_2") (pintype "bidirectional"))
      (node (ref "Q5") (pin "2") (pinfunction "B1_2") (pintype "bidirectional"))
      (node (ref "R31") (pin "2") (pinfunction "2_2") (pintype "passive"))
    )
    (net (code "18") (name "GRN2F") (class "Default")
      (node (ref "P1") (pin "1") (pinfunction "1_1") (pintype "bidirectional"))
      (node (ref "Q5") (pin "1") (pinfunction "E1_1") (pintype "bidirectional"))
      (node (ref "R25") (pin "2") (pinfunction "2_2") (pintype "passive"))
    )
    (net (code "19") (name "GRN2K1") (class "Default")
      (node (ref "GRN17") (pin "GC") (pinfunction "K_GC") (pintype "bidirectional"))
      (node (ref "JMP4") (pin "1") (pinfunction "1_1") (pintype "bidirectional"))
    )
    (net (code "20") (name "GRN2K2") (class "Default")
      (node (ref "GRN25") (pin "GC") (pinfunction "K_GC") (pintype "bidirectional"))
      (node (ref "Q5") (pin "5") (pinfunction "C2_5") (pintype "bidirectional"))
      (node (ref "Q5") (pin "56") (pinfunction "C2_56") (pintype "bidirectional"))
      (node (ref "Q5") (pin "6") (pinfunction "C2_6") (pintype "bidirectional"))
    )
    (net (code "21") (name "GRN3") (class "Default")
      (node (ref "P2") (pin "15") (pinfunction "15_15") (pintype "bidirectional"))
      (node (ref "Q8") (pin "4") (pinfunction "B2_4") (pintype "bidirectional"))
      (node (ref "R40") (pin "1") (pinfunction "1_1") (pintype "passive"))
    )
    (net (code "22") (name "GRN3F") (class "Default")
      (node (ref "P2") (pin "13") (pinfunction "13_13") (pintype "bidirectional"))
      (node (ref "Q8") (pin "3") (pinfunction "E2_3") (pintype "bidirectional"))
      (node (ref "R44") (pin "2") (pinfunction "2_2") (pintype "passive"))
    )
    (net (code "23") (name "GRN4") (class "Default")
      (node (ref "P2") (pin "2") (pinfunction "2_2") (pintype "bidirectional"))
      (node (ref "Q11") (pin "2") (pinfunction "B1_2") (pintype "bidirectional"))
      (node (ref "R65") (pin "2") (pinfunction "2_2") (pintype "passive"))
    )
    (net (code "24") (name "GRN4F") (class "Default")
      (node (ref "P2") (pin "1") (pinfunction "1_1") (pintype "bidirectional"))
      (node (ref "Q11") (pin "1") (pinfunction "E1_1") (pintype "bidirectional"))
      (node (ref "R59") (pin "2") (pinfunction "2_2") (pintype "passive"))
    )
    (net (code "25") (name "HS1") (class "Default")
      (node (ref "BLU2") (pin "T") (pinfunction "TH_T") (pintype "bidirectional"))
      (node (ref "BLU3") (pin "T") (pinfunction "TH_T") (pintype "bidirectional"))
      (node (ref "BLU4") (pin "T") (pinfunction "TH_T") (pintype "bidirectional"))
      (node (ref "BLU5") (pin "T") (pinfunction "TH_T") (pintype "bidirectional"))
      (node (ref "BLU6") (pin "T") (pinfunction "TH_T") (pintype "bidirectional"))
      (node (ref "BLU7") (pin "T") (pinfunction "TH_T") (pintype "bidirectional"))
      (node (ref "GRN2") (pin "T") (pinfunction "TH_T") (pintype "bidirectional"))
      (node (ref "GRN3") (pin "T") (pinfunction "TH_T") (pintype "bidirectional"))
      (node (ref "GRN4") (pin "T") (pinfunction "TH_T") (pintype "bidirectional"))
      (node (ref "GRN5") (pin "T") (pinfunction "TH_T") (pintype "bidirectional"))
      (node (ref "GRN6") (pin "T") (pinfunction "TH_T") (pintype "bidirectional"))
      (node (ref "GRN7") (pin "T") (pinfunction "TH_T") (pintype "bidirectional"))
      (node (ref "RED2") (pin "T") (pinfunction "TH_T") (pintype "bidirectional"))
      (node (ref "RED3") (pin "T") (pinfunction "TH_T") (pintype "bidirectional"))
      (node (ref "RED4") (pin "T") (pinfunction "TH_T") (pintype "bidirectional"))
      (node (ref "RED5") (pin "T") (pinfunction "TH_T") (pintype "bidirectional"))
      (node (ref "RED6") (pin "T") (pinfunction "TH_T") (pintype "bidirectional"))
      (node (ref "RED7") (pin "T") (pinfunction "TH_T") (pintype "bidirectional"))
    )
    (net (code "26") (name "HS2") (class "Default")
      (node (ref "BLU10") (pin "T") (pinfunction "TH_T") (pintype "bidirectional"))
      (node (ref "BLU11") (pin "T") (pinfunction "TH_T") (pintype "bidirectional"))
      (node (ref "BLU12") (pin "T") (pinfunction "TH_T") (pintype "bidirectional"))
      (node (ref "BLU13") (pin "T") (pinfunction "TH_T") (pintype "bidirectional"))
      (node (ref "BLU14") (pin "T") (pinfunction "TH_T") (pintype "bidirectional"))
      (node (ref "BLU15") (pin "T") (pinfunction "TH_T") (pintype "bidirectional"))
      (node (ref "GRN10") (pin "T") (pinfunction "TH_T") (pintype "bidirectional"))
      (node (ref "GRN11") (pin "T") (pinfunction "TH_T") (pintype "bidirectional"))
      (node (ref "GRN12") (pin "T") (pinfunction "TH_T") (pintype "bidirectional"))
      (node (ref "GRN13") (pin "T") (pinfunction "TH_T") (pintype "bidirectional"))
      (node (ref "GRN14") (pin "T") (pinfunction "TH_T") (pintype "bidirectional"))
      (node (ref "GRN15") (pin "T") (pinfunction "TH_T") (pintype "bidirectional"))
      (node (ref "RED10") (pin "T") (pinfunction "TH_T") (pintype "bidirectional"))
      (node (ref "RED11") (pin "T") (pinfunction "TH_T") (pintype "bidirectional"))
      (node (ref "RED12") (pin "T") (pinfunction "TH_T") (pintype "bidirectional"))
      (node (ref "RED13") (pin "T") (pinfunction "TH_T") (pintype "bidirectional"))
      (node (ref "RED14") (pin "T") (pinfunction "TH_T") (pintype "bidirectional"))
      (node (ref "RED15") (pin "T") (pinfunction "TH_T") (pintype "bidirectional"))
    )
    (net (code "27") (name "HS3") (class "Default")
      (node (ref "BLU18") (pin "T") (pinfunction "TH_T") (pintype "bidirectional"))
      (node (ref "BLU19") (pin "T") (pinfunction "TH_T") (pintype "bidirectional"))
      (node (ref "BLU20") (pin "T") (pinfunction "TH_T") (pintype "bidirectional"))
      (node (ref "BLU21") (pin "T") (pinfunction "TH_T") (pintype "bidirectional"))
      (node (ref "BLU22") (pin "T") (pinfunction "TH_T") (pintype "bidirectional"))
      (node (ref "BLU23") (pin "T") (pinfunction "TH_T") (pintype "bidirectional"))
      (node (ref "GRN18") (pin "T") (pinfunction "TH_T") (pintype "bidirectional"))
      (node (ref "GRN19") (pin "T") (pinfunction "TH_T") (pintype "bidirectional"))
      (node (ref "GRN20") (pin "T") (pinfunction "TH_T") (pintype "bidirectional"))
      (node (ref "GRN21") (pin "T") (pinfunction "TH_T") (pintype "bidirectional"))
      (node (ref "GRN22") (pin "T") (pinfunction "TH_T") (pintype "bidirectional"))
      (node (ref "GRN23") (pin "T") (pinfunction "TH_T") (pintype "bidirectional"))
      (node (ref "RED18") (pin "T") (pinfunction "TH_T") (pintype "bidirectional"))
      (node (ref "RED19") (pin "T") (pinfunction "TH_T") (pintype "bidirectional"))
      (node (ref "RED20") (pin "T") (pinfunction "TH_T") (pintype "bidirectional"))
      (node (ref "RED21") (pin "T") (pinfunction "TH_T") (pintype "bidirectional"))
      (node (ref "RED22") (pin "T") (pinfunction "TH_T") (pintype "bidirectional"))
      (node (ref "RED23") (pin "T") (pinfunction "TH_T") (pintype "bidirectional"))
    )
    (net (code "28") (name "HS4") (class "Default")
      (node (ref "BLU26") (pin "T") (pinfunction "TH_T") (pintype "bidirectional"))
      (node (ref "BLU27") (pin "T") (pinfunction "TH_T") (pintype "bidirectional"))
      (node (ref "BLU28") (pin "T") (pinfunction "TH_T") (pintype "bidirectional"))
      (node (ref "BLU29") (pin "T") (pinfunction "TH_T") (pintype "bidirectional"))
      (node (ref "BLU30") (pin "T") (pinfunction "TH_T") (pintype "bidirectional"))
      (node (ref "BLU31") (pin "T") (pinfunction "TH_T") (pintype "bidirectional"))
      (node (ref "GRN26") (pin "T") (pinfunction "TH_T") (pintype "bidirectional"))
      (node (ref "GRN27") (pin "T") (pinfunction "TH_T") (pintype "bidirectional"))
      (node (ref "GRN28") (pin "T") (pinfunction "TH_T") (pintype "bidirectional"))
      (node (ref "GRN29") (pin "T") (pinfunction "TH_T") (pintype "bidirectional"))
      (node (ref "GRN30") (pin "T") (pinfunction "TH_T") (pintype "bidirectional"))
      (node (ref "GRN31") (pin "T") (pinfunction "TH_T") (pintype "bidirectional"))
      (node (ref "RED26") (pin "T") (pinfunction "TH_T") (pintype "bidirectional"))
      (node (ref "RED27") (pin "T") (pinfunction "TH_T") (pintype "bidirectional"))
      (node (ref "RED28") (pin "T") (pinfunction "TH_T") (pintype "bidirectional"))
      (node (ref "RED29") (pin "T") (pinfunction "TH_T") (pintype "bidirectional"))
      (node (ref "RED30") (pin "T") (pinfunction "TH_T") (pintype "bidirectional"))
      (node (ref "RED31") (pin "T") (pinfunction "TH_T") (pintype "bidirectional"))
    )
    (net (code "29") (name "HS5") (class "Default")
      (node (ref "BLU34") (pin "T") (pinfunction "TH_T") (pintype "bidirectional"))
      (node (ref "BLU35") (pin "T") (pinfunction "TH_T") (pintype "bidirectional"))
      (node (ref "BLU36") (pin "T") (pinfunction "TH_T") (pintype "bidirectional"))
      (node (ref "BLU37") (pin "T") (pinfunction "TH_T") (pintype "bidirectional"))
      (node (ref "BLU38") (pin "T") (pinfunction "TH_T") (pintype "bidirectional"))
      (node (ref "BLU39") (pin "T") (pinfunction "TH_T") (pintype "bidirectional"))
      (node (ref "GRN34") (pin "T") (pinfunction "TH_T") (pintype "bidirectional"))
      (node (ref "GRN35") (pin "T") (pinfunction "TH_T") (pintype "bidirectional"))
      (node (ref "GRN36") (pin "T") (pinfunction "TH_T") (pintype "bidirectional"))
      (node (ref "GRN37") (pin "T") (pinfunction "TH_T") (pintype "bidirectional"))
      (node (ref "GRN38") (pin "T") (pinfunction "TH_T") (pintype "bidirectional"))
      (node (ref "GRN39") (pin "T") (pinfunction "TH_T") (pintype "bidirectional"))
      (node (ref "RED34") (pin "T") (pinfunction "TH_T") (pintype "bidirectional"))
      (node (ref "RED35") (pin "T") (pinfunction "TH_T") (pintype "bidirectional"))
      (node (ref "RED36") (pin "T") (pinfunction "TH_T") (pintype "bidirectional"))
      (node (ref "RED37") (pin "T") (pinfunction "TH_T") (pintype "bidirectional"))
      (node (ref "RED38") (pin "T") (pinfunction "TH_T") (pintype "bidirectional"))
      (node (ref "RED39") (pin "T") (pinfunction "TH_T") (pintype "bidirectional"))
    )
    (net (code "30") (name "HS6") (class "Default")
      (node (ref "BLU42") (pin "T") (pinfunction "TH_T") (pintype "bidirectional"))
      (node (ref "BLU43") (pin "T") (pinfunction "TH_T") (pintype "bidirectional"))
      (node (ref "BLU44") (pin "T") (pinfunction "TH_T") (pintype "bidirectional"))
      (node (ref "BLU45") (pin "T") (pinfunction "TH_T") (pintype "bidirectional"))
      (node (ref "BLU46") (pin "T") (pinfunction "TH_T") (pintype "bidirectional"))
      (node (ref "BLU47") (pin "T") (pinfunction "TH_T") (pintype "bidirectional"))
      (node (ref "GRN42") (pin "T") (pinfunction "TH_T") (pintype "bidirectional"))
      (node (ref "GRN43") (pin "T") (pinfunction "TH_T") (pintype "bidirectional"))
      (node (ref "GRN44") (pin "T") (pinfunction "TH_T") (pintype "bidirectional"))
      (node (ref "GRN45") (pin "T") (pinfunction "TH_T") (pintype "bidirectional"))
      (node (ref "GRN46") (pin "T") (pinfunction "TH_T") (pintype "bidirectional"))
      (node (ref "GRN47") (pin "T") (pinfunction "TH_T") (pintype "bidirectional"))
      (node (ref "RED42") (pin "T") (pinfunction "TH_T") (pintype "bidirectional"))
      (node (ref "RED43") (pin "T") (pinfunction "TH_T") (pintype "bidirectional"))
      (node (ref "RED44") (pin "T") (pinfunction "TH_T") (pintype "bidirectional"))
      (node (ref "RED45") (pin "T") (pinfunction "TH_T") (pintype "bidirectional"))
      (node (ref "RED46") (pin "T") (pinfunction "TH_T") (pintype "bidirectional"))
      (node (ref "RED47") (pin "T") (pinfunction "TH_T") (pintype "bidirectional"))
    )
    (net (code "31") (name "HS7") (class "Default")
      (node (ref "BLU50") (pin "T") (pinfunction "TH_T") (pintype "bidirectional"))
      (node (ref "BLU51") (pin "T") (pinfunction "TH_T") (pintype "bidirectional"))
      (node (ref "BLU52") (pin "T") (pinfunction "TH_T") (pintype "bidirectional"))
      (node (ref "BLU53") (pin "T") (pinfunction "TH_T") (pintype "bidirectional"))
      (node (ref "BLU54") (pin "T") (pinfunction "TH_T") (pintype "bidirectional"))
      (node (ref "BLU55") (pin "T") (pinfunction "TH_T") (pintype "bidirectional"))
      (node (ref "GRN50") (pin "T") (pinfunction "TH_T") (pintype "bidirectional"))
      (node (ref "GRN51") (pin "T") (pinfunction "TH_T") (pintype "bidirectional"))
      (node (ref "GRN52") (pin "T") (pinfunction "TH_T") (pintype "bidirectional"))
      (node (ref "GRN53") (pin "T") (pinfunction "TH_T") (pintype "bidirectional"))
      (node (ref "GRN54") (pin "T") (pinfunction "TH_T") (pintype "bidirectional"))
      (node (ref "GRN55") (pin "T") (pinfunction "TH_T") (pintype "bidirectional"))
      (node (ref "RED50") (pin "T") (pinfunction "TH_T") (pintype "bidirectional"))
      (node (ref "RED51") (pin "T") (pinfunction "TH_T") (pintype "bidirectional"))
      (node (ref "RED52") (pin "T") (pinfunction "TH_T") (pintype "bidirectional"))
      (node (ref "RED53") (pin "T") (pinfunction "TH_T") (pintype "bidirectional"))
      (node (ref "RED54") (pin "T") (pinfunction "TH_T") (pintype "bidirectional"))
      (node (ref "RED55") (pin "T") (pinfunction "TH_T") (pintype "bidirectional"))
    )
    (net (code "32") (name "HS8") (class "Default")
      (node (ref "BLU58") (pin "T") (pinfunction "TH_T") (pintype "bidirectional"))
      (node (ref "BLU59") (pin "T") (pinfunction "TH_T") (pintype "bidirectional"))
      (node (ref "BLU60") (pin "T") (pinfunction "TH_T") (pintype "bidirectional"))
      (node (ref "BLU61") (pin "T") (pinfunction "TH_T") (pintype "bidirectional"))
      (node (ref "BLU62") (pin "T") (pinfunction "TH_T") (pintype "bidirectional"))
      (node (ref "BLU63") (pin "T") (pinfunction "TH_T") (pintype "bidirectional"))
      (node (ref "GRN58") (pin "T") (pinfunction "TH_T") (pintype "bidirectional"))
      (node (ref "GRN59") (pin "T") (pinfunction "TH_T") (pintype "bidirectional"))
      (node (ref "GRN60") (pin "T") (pinfunction "TH_T") (pintype "bidirectional"))
      (node (ref "GRN61") (pin "T") (pinfunction "TH_T") (pintype "bidirectional"))
      (node (ref "GRN62") (pin "T") (pinfunction "TH_T") (pintype "bidirectional"))
      (node (ref "GRN63") (pin "T") (pinfunction "TH_T") (pintype "bidirectional"))
      (node (ref "RED58") (pin "T") (pinfunction "TH_T") (pintype "bidirectional"))
      (node (ref "RED59") (pin "T") (pinfunction "TH_T") (pintype "bidirectional"))
      (node (ref "RED60") (pin "T") (pinfunction "TH_T") (pintype "bidirectional"))
      (node (ref "RED61") (pin "T") (pinfunction "TH_T") (pintype "bidirectional"))
      (node (ref "RED62") (pin "T") (pinfunction "TH_T") (pintype "bidirectional"))
      (node (ref "RED63") (pin "T") (pinfunction "TH_T") (pintype "bidirectional"))
    )
    (net (code "33") (name "IGND") (class "Default")
      (node (ref "C11") (pin "2") (pinfunction "2_2") (pintype "passive"))
      (node (ref "C12") (pin "2") (pinfunction "2_2") (pintype "passive"))
      (node (ref "C16") (pin "2") (pinfunction "2_2") (pintype "passive"))
      (node (ref "C17") (pin "2") (pinfunction "2_2") (pintype "passive"))
      (node (ref "C22") (pin "2") (pinfunction "2_2") (pintype "passive"))
      (node (ref "C23") (pin "2") (pinfunction "2_2") (pintype "passive"))
      (node (ref "JMP16") (pin "1") (pinfunction "1_1") (pintype "bidirectional"))
      (node (ref "JMP16") (pin "2") (pinfunction "2_2") (pintype "bidirectional"))
      (node (ref "JMP17") (pin "1") (pinfunction "1_1") (pintype "bidirectional"))
      (node (ref "JMP17") (pin "2") (pinfunction "2_2") (pintype "bidirectional"))
      (node (ref "R48") (pin "1") (pinfunction "1_1") (pintype "passive"))
      (node (ref "R51") (pin "2") (pinfunction "2_2") (pintype "passive"))
      (node (ref "R54") (pin "1") (pinfunction "1_1") (pintype "passive"))
      (node (ref "U3") (pin "2") (pinfunction "GND_2") (pintype "bidirectional"))
      (node (ref "U3") (pin "7") (pinfunction "GND1_7") (pintype "bidirectional"))
      (node (ref "U3") (pin "EP") (pinfunction "EP_EP") (pintype "bidirectional"))
      (node (ref "U4") (pin "2") (pinfunction "GND_2") (pintype "bidirectional"))
      (node (ref "U4") (pin "7") (pinfunction "GND1_7") (pintype "bidirectional"))
      (node (ref "U4") (pin "EP") (pinfunction "EP_EP") (pintype "bidirectional"))
    )
    (net (code "34") (name "IGND1") (class "Default")
      (node (ref "C2") (pin "2") (pinfunction "2_2") (pintype "passive"))
      (node (ref "C20") (pin "2") (pinfunction "2_2") (pintype "passive"))
      (node (ref "C21") (pin "2") (pinfunction "2_2") (pintype "passive"))
      (node (ref "C3") (pin "2") (pinfunction "2_2") (pintype "passive"))
      (node (ref "C7") (pin "2") (pinfunction "2_2") (pintype "passive"))
      (node (ref "C8") (pin "2") (pinfunction "2_2") (pintype "passive"))
      (node (ref "JMP18") (pin "1") (pinfunction "1_1") (pintype "bidirectional"))
      (node (ref "JMP18") (pin "2") (pinfunction "2_2") (pintype "bidirectional"))
      (node (ref "JMP19") (pin "1") (pinfunction "1_1") (pintype "bidirectional"))
      (node (ref "JMP19") (pin "2") (pinfunction "2_2") (pintype "bidirectional"))
      (node (ref "R14") (pin "1") (pinfunction "1_1") (pintype "passive"))
      (node (ref "R17") (pin "2") (pinfunction "2_2") (pintype "passive"))
      (node (ref "R20") (pin "1") (pinfunction "1_1") (pintype "passive"))
      (node (ref "U1") (pin "2") (pinfunction "GND_2") (pintype "bidirectional"))
      (node (ref "U1") (pin "7") (pinfunction "GND1_7") (pintype "bidirectional"))
      (node (ref "U1") (pin "EP") (pinfunction "EP_EP") (pintype "bidirectional"))
      (node (ref "U2") (pin "2") (pinfunction "GND_2") (pintype "bidirectional"))
      (node (ref "U2") (pin "7") (pinfunction "GND1_7") (pintype "bidirectional"))
      (node (ref "U2") (pin "EP") (pinfunction "EP_EP") (pintype "bidirectional"))
    )
    (net (code "35") (name "IR_1") (class "Default")
      (node (ref "P1") (pin "9") (pinfunction "9_9") (pintype "bidirectional"))
      (node (ref "R14") (pin "2") (pinfunction "2_2") (pintype "passive"))
      (node (ref "U1") (pin "8") (pinfunction "CTRL_8") (pintype "bidirectional"))
    )
    (net (code "36") (name "IR_2") (class "Default")
      (node (ref "P1") (pin "7") (pinfunction "7_7") (pintype "bidirectional"))
      (node (ref "R20") (pin "2") (pinfunction "2_2") (pintype "passive"))
      (node (ref "U2") (pin "8") (pinfunction "CTRL_8") (pintype "bidirectional"))
    )
    (net (code "37") (name "IR_3") (class "Default")
      (node (ref "P2") (pin "9") (pinfunction "9_9") (pintype "bidirectional"))
      (node (ref "R48") (pin "2") (pinfunction "2_2") (pintype "passive"))
      (node (ref "U3") (pin "8") (pinfunction "CTRL_8") (pintype "bidirectional"))
    )
    (net (code "38") (name "IR_4") (class "Default")
      (node (ref "P2") (pin "7") (pinfunction "7_7") (pintype "bidirectional"))
      (node (ref "R54") (pin "2") (pinfunction "2_2") (pintype "passive"))
      (node (ref "U4") (pin "8") (pinfunction "CTRL_8") (pintype "bidirectional"))
    )
    (net (code "39") (name "IR_DRV3") (class "Default")
      (node (ref "BLU33") (pin "T") (pinfunction "TH_T") (pintype "bidirectional"))
      (node (ref "BLU41") (pin "T") (pinfunction "TH_T") (pintype "bidirectional"))
      (node (ref "C13") (pin "1") (pinfunction "1_1") (pintype "passive"))
      (node (ref "C14") (pin "1") (pinfunction "1_1") (pintype "passive"))
      (node (ref "D131") (pin "A") (pinfunction "A_A") (pintype "bidirectional"))
      (node (ref "D147") (pin "A") (pinfunction "A_A") (pintype "bidirectional"))
      (node (ref "D163") (pin "A") (pinfunction "A_A") (pintype "bidirectional"))
      (node (ref "D180") (pin "A") (pinfunction "A_A") (pintype "bidirectional"))
      (node (ref "GRN33") (pin "T") (pinfunction "TH_T") (pintype "bidirectional"))
      (node (ref "GRN41") (pin "T") (pinfunction "TH_T") (pintype "bidirectional"))
      (node (ref "R50") (pin "1") (pinfunction "1_1") (pintype "passive"))
      (node (ref "RED33") (pin "T") (pinfunction "TH_T") (pintype "bidirectional"))
      (node (ref "RED41") (pin "T") (pinfunction "TH_T") (pintype "bidirectional"))
      (node (ref "U3") (pin "1") (pinfunction "SET_1") (pintype "bidirectional"))
    )
    (net (code "40") (name "IR_DRV4") (class "Default")
      (node (ref "BLU49") (pin "T") (pinfunction "TH_T") (pintype "bidirectional"))
      (node (ref "BLU57") (pin "T") (pinfunction "TH_T") (pintype "bidirectional"))
      (node (ref "C15") (pin "1") (pinfunction "1_1") (pintype "passive"))
      (node (ref "C18") (pin "1") (pinfunction "1_1") (pintype "passive"))
      (node (ref "D196") (pin "A") (pinfunction "A_A") (pintype "bidirectional"))
      (node (ref "D213") (pin "A") (pinfunction "A_A") (pintype "bidirectional"))
      (node (ref "D229") (pin "A") (pinfunction "A_A") (pintype "bidirectional"))
      (node (ref "D245") (pin "A") (pinfunction "A_A") (pintype "bidirectional"))
      (node (ref "GRN49") (pin "T") (pinfunction "TH_T") (pintype "bidirectional"))
      (node (ref "GRN57") (pin "T") (pinfunction "TH_T") (pintype "bidirectional"))
      (node (ref "R53") (pin "1") (pinfunction "1_1") (pintype "passive"))
      (node (ref "RED49") (pin "T") (pinfunction "TH_T") (pintype "bidirectional"))
      (node (ref "RED57") (pin "T") (pinfunction "TH_T") (pintype "bidirectional"))
      (node (ref "U4") (pin "1") (pinfunction "SET_1") (pintype "bidirectional"))
    )
    (net (code "41") (name "IR_DRV_UL1") (class "Default")
      (node (ref "BLU1") (pin "T") (pinfunction "TH_T") (pintype "bidirectional"))
      (node (ref "BLU9") (pin "T") (pinfunction "TH_T") (pintype "bidirectional"))
      (node (ref "C4") (pin "1") (pinfunction "1_1") (pintype "passive"))
      (node (ref "C5") (pin "1") (pinfunction "1_1") (pintype "passive"))
      (node (ref "D1") (pin "A") (pinfunction "A_A") (pintype "bidirectional"))
      (node (ref "D17") (pin "A") (pinfunction "A_A") (pintype "bidirectional"))
      (node (ref "D33") (pin "A") (pinfunction "A_A") (pintype "bidirectional"))
      (node (ref "D50") (pin "A") (pinfunction "A_A") (pintype "bidirectional"))
      (node (ref "GRN1") (pin "T") (pinfunction "TH_T") (pintype "bidirectional"))
      (node (ref "GRN9") (pin "T") (pinfunction "TH_T") (pintype "bidirectional"))
      (node (ref "R16") (pin "1") (pinfunction "1_1") (pintype "passive"))
      (node (ref "RED1") (pin "T") (pinfunction "TH_T") (pintype "bidirectional"))
      (node (ref "RED9") (pin "T") (pinfunction "TH_T") (pintype "bidirectional"))
      (node (ref "U1") (pin "1") (pinfunction "SET_1") (pintype "bidirectional"))
    )
    (net (code "42") (name "IR_DRV_UL2") (class "Default")
      (node (ref "BLU17") (pin "T") (pinfunction "TH_T") (pintype "bidirectional"))
      (node (ref "BLU25") (pin "T") (pinfunction "TH_T") (pintype "bidirectional"))
      (node (ref "C6") (pin "1") (pinfunction "1_1") (pintype "passive"))
      (node (ref "C9") (pin "1") (pinfunction "1_1") (pintype "passive"))
      (node (ref "D115") (pin "A") (pinfunction "A_A") (pintype "bidirectional"))
      (node (ref "D66") (pin "A") (pinfunction "A_A") (pintype "bidirectional"))
      (node (ref "D83") (pin "A") (pinfunction "A_A") (pintype "bidirectional"))
      (node (ref "D99") (pin "A") (pinfunction "A_A") (pintype "bidirectional"))
      (node (ref "GRN17") (pin "T") (pinfunction "TH_T") (pintype "bidirectional"))
      (node (ref "GRN25") (pin "T") (pinfunction "TH_T") (pintype "bidirectional"))
      (node (ref "R19") (pin "1") (pinfunction "1_1") (pintype "passive"))
      (node (ref "RED17") (pin "T") (pinfunction "TH_T") (pintype "bidirectional"))
      (node (ref "RED25") (pin "T") (pinfunction "TH_T") (pintype "bidirectional"))
      (node (ref "U2") (pin "1") (pinfunction "SET_1") (pintype "bidirectional"))
    )
    (net (code "43") (name "IR_RET2") (class "Default")
      (node (ref "BLU24") (pin "T") (pinfunction "TH_T") (pintype "bidirectional"))
      (node (ref "BLU32") (pin "T") (pinfunction "TH_T") (pintype "bidirectional"))
      (node (ref "C6") (pin "2") (pinfunction "2_2") (pintype "passive"))
      (node (ref "D114") (pin "C") (pinfunction "K_C") (pintype "bidirectional"))
      (node (ref "D130") (pin "C") (pinfunction "K_C") (pintype "bidirectional"))
      (node (ref "D81") (pin "C") (pinfunction "K_C") (pintype "bidirectional"))
      (node (ref "D98") (pin "C") (pinfunction "K_C") (pintype "bidirectional"))
      (node (ref "GRN24") (pin "T") (pinfunction "TH_T") (pintype "bidirectional"))
      (node (ref "GRN32") (pin "T") (pinfunction "TH_T") (pintype "bidirectional"))
      (node (ref "R21") (pin "2") (pinfunction "2_2") (pintype "passive"))
      (node (ref "RED24") (pin "T") (pinfunction "TH_T") (pintype "bidirectional"))
      (node (ref "RED32") (pin "T") (pinfunction "TH_T") (pintype "bidirectional"))
    )
    (net (code "44") (name "IR_RET3") (class "Default")
      (node (ref "BLU40") (pin "T") (pinfunction "TH_T") (pintype "bidirectional"))
      (node (ref "BLU48") (pin "T") (pinfunction "TH_T") (pintype "bidirectional"))
      (node (ref "C13") (pin "2") (pinfunction "2_2") (pintype "passive"))
      (node (ref "C14") (pin "2") (pinfunction "2_2") (pintype "passive"))
      (node (ref "D146") (pin "C") (pinfunction "K_C") (pintype "bidirectional"))
      (node (ref "D162") (pin "C") (pinfunction "K_C") (pintype "bidirectional"))
      (node (ref "D178") (pin "C") (pinfunction "K_C") (pintype "bidirectional"))
      (node (ref "D195") (pin "C") (pinfunction "K_C") (pintype "bidirectional"))
      (node (ref "GRN40") (pin "T") (pinfunction "TH_T") (pintype "bidirectional"))
      (node (ref "GRN48") (pin "T") (pinfunction "TH_T") (pintype "bidirectional"))
      (node (ref "L3") (pin "1") (pinfunction "1_1") (pintype "passive"))
      (node (ref "RED40") (pin "T") (pinfunction "TH_T") (pintype "bidirectional"))
      (node (ref "RED48") (pin "T") (pinfunction "TH_T") (pintype "bidirectional"))
    )
    (net (code "45") (name "IR_RET_UL1") (class "Default")
      (node (ref "BLU16") (pin "T") (pinfunction "TH_T") (pintype "bidirectional"))
      (node (ref "BLU8") (pin "T") (pinfunction "TH_T") (pintype "bidirectional"))
      (node (ref "C4") (pin "2") (pinfunction "2_2") (pintype "passive"))
      (node (ref "C5") (pin "2") (pinfunction "2_2") (pintype "passive"))
      (node (ref "D16") (pin "C") (pinfunction "K_C") (pintype "bidirectional"))
      (node (ref "D32") (pin "C") (pinfunction "K_C") (pintype "bidirectional"))
      (node (ref "D48") (pin "C") (pinfunction "K_C") (pintype "bidirectional"))
      (node (ref "D65") (pin "C") (pinfunction "K_C") (pintype "bidirectional"))
      (node (ref "GRN16") (pin "T") (pinfunction "TH_T") (pintype "bidirectional"))
      (node (ref "GRN8") (pin "T") (pinfunction "TH_T") (pintype "bidirectional"))
      (node (ref "L1") (pin "1") (pinfunction "1_1") (pintype "passive"))
      (node (ref "RED16") (pin "T") (pinfunction "TH_T") (pintype "bidirectional"))
      (node (ref "RED8") (pin "T") (pinfunction "TH_T") (pintype "bidirectional"))
    )
    (net (code "46") (name "I_RET4") (class "Default")
      (node (ref "BLU56") (pin "T") (pinfunction "TH_T") (pintype "bidirectional"))
      (node (ref "BLU64") (pin "T") (pinfunction "TH_T") (pintype "bidirectional"))
      (node (ref "C15") (pin "2") (pinfunction "2_2") (pintype "passive"))
      (node (ref "D211") (pin "C") (pinfunction "K_C") (pintype "bidirectional"))
      (node (ref "D228") (pin "C") (pinfunction "K_C") (pintype "bidirectional"))
      (node (ref "D244") (pin "C") (pinfunction "K_C") (pintype "bidirectional"))
      (node (ref "D260") (pin "C") (pinfunction "K_C") (pintype "bidirectional"))
      (node (ref "GRN56") (pin "T") (pinfunction "TH_T") (pintype "bidirectional"))
      (node (ref "GRN64") (pin "T") (pinfunction "TH_T") (pintype "bidirectional"))
      (node (ref "R55") (pin "2") (pinfunction "2_2") (pintype "passive"))
      (node (ref "RED56") (pin "T") (pinfunction "TH_T") (pintype "bidirectional"))
      (node (ref "RED64") (pin "T") (pinfunction "TH_T") (pintype "bidirectional"))
    )
    (net (code "47") (name "LGND") (class "Default")
      (node (ref "C1") (pin "-") (pinfunction "-_-") (pintype "passive"))
      (node (ref "C10") (pin "-") (pinfunction "-_-") (pintype "passive"))
      (node (ref "C19") (pin "-") (pinfunction "-_-") (pintype "passive"))
      (node (ref "J1") (pin "2") (pinfunction "P$3_2") (pintype "bidirectional"))
      (node (ref "P1") (pin "10") (pinfunction "10_10") (pintype "bidirectional"))
      (node (ref "P1") (pin "8") (pinfunction "8_8") (pintype "bidirectional"))
      (node (ref "P2") (pin "10") (pinfunction "10_10") (pintype "bidirectional"))
      (node (ref "P2") (pin "8") (pinfunction "8_8") (pintype "bidirectional"))
      (node (ref "P4") (pin "1") (pinfunction "1_1") (pintype "bidirectional"))
      (node (ref "P4") (pin "3") (pinfunction "3_3") (pintype "bidirectional"))
      (node (ref "R10") (pin "1") (pinfunction "1_1") (pintype "passive"))
      (node (ref "R11") (pin "1") (pinfunction "1_1") (pintype "passive"))
      (node (ref "R13") (pin "1") (pinfunction "1_1") (pintype "passive"))
      (node (ref "R17") (pin "1") (pinfunction "1_1") (pintype "passive"))
      (node (ref "R22") (pin "1") (pinfunction "1_1") (pintype "passive"))
      (node (ref "R24") (pin "1") (pinfunction "1_1") (pintype "passive"))
      (node (ref "R25") (pin "1") (pinfunction "1_1") (pintype "passive"))
      (node (ref "R27") (pin "1") (pinfunction "1_1") (pintype "passive"))
      (node (ref "R29") (pin "1") (pinfunction "1_1") (pintype "passive"))
      (node (ref "R3") (pin "1") (pinfunction "1_1") (pintype "passive"))
      (node (ref "R32") (pin "1") (pinfunction "1_1") (pintype "passive"))
      (node (ref "R37") (pin "1") (pinfunction "1_1") (pintype "passive"))
      (node (ref "R39") (pin "1") (pinfunction "1_1") (pintype "passive"))
      (node (ref "R41") (pin "1") (pinfunction "1_1") (pintype "passive"))
      (node (ref "R44") (pin "1") (pinfunction "1_1") (pintype "passive"))
      (node (ref "R45") (pin "1") (pinfunction "1_1") (pintype "passive"))
      (node (ref "R47") (pin "1") (pinfunction "1_1") (pintype "passive"))
      (node (ref "R5") (pin "1") (pinfunction "1_1") (pintype "passive"))
      (node (ref "R51") (pin "1") (pinfunction "1_1") (pintype "passive"))
      (node (ref "R56") (pin "1") (pinfunction "1_1") (pintype "passive"))
      (node (ref "R58") (pin "1") (pinfunction "1_1") (pintype "passive"))
      (node (ref "R59") (pin "1") (pinfunction "1_1") (pintype "passive"))
      (node (ref "R61") (pin "1") (pinfunction "1_1") (pintype "passive"))
      (node (ref "R63") (pin "1") (pinfunction "1_1") (pintype "passive"))
      (node (ref "R66") (pin "1") (pinfunction "1_1") (pintype "passive"))
      (node (ref "R7") (pin "1") (pinfunction "1_1") (pintype "passive"))
    )
    (net (code "48") (name "Net-(BLU1-A)") (class "Default")
      (node (ref "BLU1") (pin "GA") (pinfunction "A_GA") (pintype "bidirectional"))
      (node (ref "BLU2") (pin "GC") (pinfunction "K_GC") (pintype "bidirectional"))
    )
    (net (code "49") (name "Net-(BLU2-A)") (class "Default")
      (node (ref "BLU2") (pin "GA") (pinfunction "A_GA") (pintype "bidirectional"))
      (node (ref "BLU3") (pin "GC") (pinfunction "K_GC") (pintype "bidirectional"))
    )
    (net (code "50") (name "Net-(BLU3-A)") (class "Default")
      (node (ref "BLU3") (pin "GA") (pinfunction "A_GA") (pintype "bidirectional"))
      (node (ref "BLU4") (pin "GC") (pinfunction "K_GC") (pintype "bidirectional"))
    )
    (net (code "51") (name "Net-(BLU4-A)") (class "Default")
      (node (ref "BLU4") (pin "GA") (pinfunction "A_GA") (pintype "bidirectional"))
      (node (ref "BLU5") (pin "GC") (pinfunction "K_GC") (pintype "bidirectional"))
    )
    (net (code "52") (name "Net-(BLU5-A)") (class "Default")
      (node (ref "BLU5") (pin "GA") (pinfunction "A_GA") (pintype "bidirectional"))
      (node (ref "BLU6") (pin "GC") (pinfunction "K_GC") (pintype "bidirectional"))
    )
    (net (code "53") (name "Net-(BLU6-A)") (class "Default")
      (node (ref "BLU6") (pin "GA") (pinfunction "A_GA") (pintype "bidirectional"))
      (node (ref "BLU7") (pin "GC") (pinfunction "K_GC") (pintype "bidirectional"))
    )
    (net (code "54") (name "Net-(BLU7-A)") (class "Default")
      (node (ref "BLU7") (pin "GA") (pinfunction "A_GA") (pintype "bidirectional"))
      (node (ref "BLU8") (pin "GC") (pinfunction "K_GC") (pintype "bidirectional"))
    )
    (net (code "55") (name "Net-(BLU10-A)") (class "Default")
      (node (ref "BLU10") (pin "GA") (pinfunction "A_GA") (pintype "bidirectional"))
      (node (ref "BLU11") (pin "GC") (pinfunction "K_GC") (pintype "bidirectional"))
    )
    (net (code "56") (name "Net-(BLU10-K)") (class "Default")
      (node (ref "BLU10") (pin "GC") (pinfunction "K_GC") (pintype "bidirectional"))
      (node (ref "BLU9") (pin "GA") (pinfunction "A_GA") (pintype "bidirectional"))
    )
    (net (code "57") (name "Net-(BLU11-A)") (class "Default")
      (node (ref "BLU11") (pin "GA") (pinfunction "A_GA") (pintype "bidirectional"))
      (node (ref "BLU12") (pin "GC") (pinfunction "K_GC") (pintype "bidirectional"))
    )
    (net (code "58") (name "Net-(BLU12-A)") (class "Default")
      (node (ref "BLU12") (pin "GA") (pinfunction "A_GA") (pintype "bidirectional"))
      (node (ref "BLU13") (pin "GC") (pinfunction "K_GC") (pintype "bidirectional"))
    )
    (net (code "59") (name "Net-(BLU13-A)") (class "Default")
      (node (ref "BLU13") (pin "GA") (pinfunction "A_GA") (pintype "bidirectional"))
      (node (ref "BLU14") (pin "GC") (pinfunction "K_GC") (pintype "bidirectional"))
    )
    (net (code "60") (name "Net-(BLU14-A)") (class "Default")
      (node (ref "BLU14") (pin "GA") (pinfunction "A_GA") (pintype "bidirectional"))
      (node (ref "BLU15") (pin "GC") (pinfunction "K_GC") (pintype "bidirectional"))
    )
    (net (code "61") (name "Net-(BLU15-A)") (class "Default")
      (node (ref "BLU15") (pin "GA") (pinfunction "A_GA") (pintype "bidirectional"))
      (node (ref "BLU16") (pin "GC") (pinfunction "K_GC") (pintype "bidirectional"))
    )
    (net (code "62") (name "Net-(BLU17-A)") (class "Default")
      (node (ref "BLU17") (pin "GA") (pinfunction "A_GA") (pintype "bidirectional"))
      (node (ref "BLU18") (pin "GC") (pinfunction "K_GC") (pintype "bidirectional"))
    )
    (net (code "63") (name "Net-(BLU18-A)") (class "Default")
      (node (ref "BLU18") (pin "GA") (pinfunction "A_GA") (pintype "bidirectional"))
      (node (ref "BLU19") (pin "GC") (pinfunction "K_GC") (pintype "bidirectional"))
    )
    (net (code "64") (name "Net-(BLU19-A)") (class "Default")
      (node (ref "BLU19") (pin "GA") (pinfunction "A_GA") (pintype "bidirectional"))
      (node (ref "BLU20") (pin "GC") (pinfunction "K_GC") (pintype "bidirectional"))
    )
    (net (code "65") (name "Net-(BLU20-A)") (class "Default")
      (node (ref "BLU20") (pin "GA") (pinfunction "A_GA") (pintype "bidirectional"))
      (node (ref "BLU21") (pin "GC") (pinfunction "K_GC") (pintype "bidirectional"))
    )
    (net (code "66") (name "Net-(BLU21-A)") (class "Default")
      (node (ref "BLU21") (pin "GA") (pinfunction "A_GA") (pintype "bidirectional"))
      (node (ref "BLU22") (pin "GC") (pinfunction "K_GC") (pintype "bidirectional"))
    )
    (net (code "67") (name "Net-(BLU22-A)") (class "Default")
      (node (ref "BLU22") (pin "GA") (pinfunction "A_GA") (pintype "bidirectional"))
      (node (ref "BLU23") (pin "GC") (pinfunction "K_GC") (pintype "bidirectional"))
    )
    (net (code "68") (name "Net-(BLU23-A)") (class "Default")
      (node (ref "BLU23") (pin "GA") (pinfunction "A_GA") (pintype "bidirectional"))
      (node (ref "BLU24") (pin "GC") (pinfunction "K_GC") (pintype "bidirectional"))
    )
    (net (code "69") (name "Net-(BLU25-A)") (class "Default")
      (node (ref "BLU25") (pin "GA") (pinfunction "A_GA") (pintype "bidirectional"))
      (node (ref "BLU26") (pin "GC") (pinfunction "K_GC") (pintype "bidirectional"))
    )
    (net (code "70") (name "Net-(BLU26-A)") (class "Default")
      (node (ref "BLU26") (pin "GA") (pinfunction "A_GA") (pintype "bidirectional"))
      (node (ref "BLU27") (pin "GC") (pinfunction "K_GC") (pintype "bidirectional"))
    )
    (net (code "71") (name "Net-(BLU27-A)") (class "Default")
      (node (ref "BLU27") (pin "GA") (pinfunction "A_GA") (pintype "bidirectional"))
      (node (ref "BLU28") (pin "GC") (pinfunction "K_GC") (pintype "bidirectional"))
    )
    (net (code "72") (name "Net-(BLU28-A)") (class "Default")
      (node (ref "BLU28") (pin "GA") (pinfunction "A_GA") (pintype "bidirectional"))
      (node (ref "BLU29") (pin "GC") (pinfunction "K_GC") (pintype "bidirectional"))
    )
    (net (code "73") (name "Net-(BLU29-A)") (class "Default")
      (node (ref "BLU29") (pin "GA") (pinfunction "A_GA") (pintype "bidirectional"))
      (node (ref "BLU30") (pin "GC") (pinfunction "K_GC") (pintype "bidirectional"))
    )
    (net (code "74") (name "Net-(BLU30-A)") (class "Default")
      (node (ref "BLU30") (pin "GA") (pinfunction "A_GA") (pintype "bidirectional"))
      (node (ref "BLU31") (pin "GC") (pinfunction "K_GC") (pintype "bidirectional"))
    )
    (net (code "75") (name "Net-(BLU31-A)") (class "Default")
      (node (ref "BLU31") (pin "GA") (pinfunction "A_GA") (pintype "bidirectional"))
      (node (ref "BLU32") (pin "GC") (pinfunction "K_GC") (pintype "bidirectional"))
    )
    (net (code "76") (name "Net-(BLU33-A)") (class "Default")
      (node (ref "BLU33") (pin "GA") (pinfunction "A_GA") (pintype "bidirectional"))
      (node (ref "BLU34") (pin "GC") (pinfunction "K_GC") (pintype "bidirectional"))
    )
    (net (code "77") (name "Net-(BLU33-K)") (class "Default")
      (node (ref "BLU33") (pin "GC") (pinfunction "K_GC") (pintype "bidirectional"))
      (node (ref "Q7") (pin "7") (pinfunction "C1_7") (pintype "bidirectional"))
      (node (ref "Q7") (pin "78") (pinfunction "C1_78") (pintype "bidirectional"))
      (node (ref "Q7") (pin "8") (pinfunction "C1_8") (pintype "bidirectional"))
    )
    (net (code "78") (name "Net-(BLU34-A)") (class "Default")
      (node (ref "BLU34") (pin "GA") (pinfunction "A_GA") (pintype "bidirectional"))
      (node (ref "BLU35") (pin "GC") (pinfunction "K_GC") (pintype "bidirectional"))
    )
    (net (code "79") (name "Net-(BLU35-A)") (class "Default")
      (node (ref "BLU35") (pin "GA") (pinfunction "A_GA") (pintype "bidirectional"))
      (node (ref "BLU36") (pin "GC") (pinfunction "K_GC") (pintype "bidirectional"))
    )
    (net (code "80") (name "Net-(BLU36-A)") (class "Default")
      (node (ref "BLU36") (pin "GA") (pinfunction "A_GA") (pintype "bidirectional"))
      (node (ref "BLU37") (pin "GC") (pinfunction "K_GC") (pintype "bidirectional"))
    )
    (net (code "81") (name "Net-(BLU37-A)") (class "Default")
      (node (ref "BLU37") (pin "GA") (pinfunction "A_GA") (pintype "bidirectional"))
      (node (ref "BLU38") (pin "GC") (pinfunction "K_GC") (pintype "bidirectional"))
    )
    (net (code "82") (name "Net-(BLU38-A)") (class "Default")
      (node (ref "BLU38") (pin "GA") (pinfunction "A_GA") (pintype "bidirectional"))
      (node (ref "BLU39") (pin "GC") (pinfunction "K_GC") (pintype "bidirectional"))
    )
    (net (code "83") (name "Net-(BLU39-A)") (class "Default")
      (node (ref "BLU39") (pin "GA") (pinfunction "A_GA") (pintype "bidirectional"))
      (node (ref "BLU40") (pin "GC") (pinfunction "K_GC") (pintype "bidirectional"))
    )
    (net (code "84") (name "Net-(BLU41-A)") (class "Default")
      (node (ref "BLU41") (pin "GA") (pinfunction "A_GA") (pintype "bidirectional"))
      (node (ref "BLU42") (pin "GC") (pinfunction "K_GC") (pintype "bidirectional"))
    )
    (net (code "85") (name "Net-(BLU41-K)") (class "Default")
      (node (ref "BLU41") (pin "GC") (pinfunction "K_GC") (pintype "bidirectional"))
      (node (ref "Q7") (pin "5") (pinfunction "C2_5") (pintype "bidirectional"))
      (node (ref "Q7") (pin "56") (pinfunction "C2_56") (pintype "bidirectional"))
      (node (ref "Q7") (pin "6") (pinfunction "C2_6") (pintype "bidirectional"))
    )
    (net (code "86") (name "Net-(BLU42-A)") (class "Default")
      (node (ref "BLU42") (pin "GA") (pinfunction "A_GA") (pintype "bidirectional"))
      (node (ref "BLU43") (pin "GC") (pinfunction "K_GC") (pintype "bidirectional"))
    )
    (net (code "87") (name "Net-(BLU43-A)") (class "Default")
      (node (ref "BLU43") (pin "GA") (pinfunction "A_GA") (pintype "bidirectional"))
      (node (ref "BLU44") (pin "GC") (pinfunction "K_GC") (pintype "bidirectional"))
    )
    (net (code "88") (name "Net-(BLU44-A)") (class "Default")
      (node (ref "BLU44") (pin "GA") (pinfunction "A_GA") (pintype "bidirectional"))
      (node (ref "BLU45") (pin "GC") (pinfunction "K_GC") (pintype "bidirectional"))
    )
    (net (code "89") (name "Net-(BLU45-A)") (class "Default")
      (node (ref "BLU45") (pin "GA") (pinfunction "A_GA") (pintype "bidirectional"))
      (node (ref "BLU46") (pin "GC") (pinfunction "K_GC") (pintype "bidirectional"))
    )
    (net (code "90") (name "Net-(BLU46-A)") (class "Default")
      (node (ref "BLU46") (pin "GA") (pinfunction "A_GA") (pintype "bidirectional"))
      (node (ref "BLU47") (pin "GC") (pinfunction "K_GC") (pintype "bidirectional"))
    )
    (net (code "91") (name "Net-(BLU47-A)") (class "Default")
      (node (ref "BLU47") (pin "GA") (pinfunction "A_GA") (pintype "bidirectional"))
      (node (ref "BLU48") (pin "GC") (pinfunction "K_GC") (pintype "bidirectional"))
    )
    (net (code "92") (name "Net-(BLU49-A)") (class "Default")
      (node (ref "BLU49") (pin "GA") (pinfunction "A_GA") (pintype "bidirectional"))
      (node (ref "BLU50") (pin "GC") (pinfunction "K_GC") (pintype "bidirectional"))
    )
    (net (code "93") (name "Net-(BLU49-K)") (class "Default")
      (node (ref "BLU49") (pin "GC") (pinfunction "K_GC") (pintype "bidirectional"))
      (node (ref "Q10") (pin "7") (pinfunction "C1_7") (pintype "bidirectional"))
      (node (ref "Q10") (pin "78") (pinfunction "C1_78") (pintype "bidirectional"))
      (node (ref "Q10") (pin "8") (pinfunction "C1_8") (pintype "bidirectional"))
    )
    (net (code "94") (name "Net-(BLU50-A)") (class "Default")
      (node (ref "BLU50") (pin "GA") (pinfunction "A_GA") (pintype "bidirectional"))
      (node (ref "BLU51") (pin "GC") (pinfunction "K_GC") (pintype "bidirectional"))
    )
    (net (code "95") (name "Net-(BLU51-A)") (class "Default")
      (node (ref "BLU51") (pin "GA") (pinfunction "A_GA") (pintype "bidirectional"))
      (node (ref "BLU52") (pin "GC") (pinfunction "K_GC") (pintype "bidirectional"))
    )
    (net (code "96") (name "Net-(BLU52-A)") (class "Default")
      (node (ref "BLU52") (pin "GA") (pinfunction "A_GA") (pintype "bidirectional"))
      (node (ref "BLU53") (pin "GC") (pinfunction "K_GC") (pintype "bidirectional"))
    )
    (net (code "97") (name "Net-(BLU53-A)") (class "Default")
      (node (ref "BLU53") (pin "GA") (pinfunction "A_GA") (pintype "bidirectional"))
      (node (ref "BLU54") (pin "GC") (pinfunction "K_GC") (pintype "bidirectional"))
    )
    (net (code "98") (name "Net-(BLU54-A)") (class "Default")
      (node (ref "BLU54") (pin "GA") (pinfunction "A_GA") (pintype "bidirectional"))
      (node (ref "BLU55") (pin "GC") (pinfunction "K_GC") (pintype "bidirectional"))
    )
    (net (code "99") (name "Net-(BLU55-A)") (class "Default")
      (node (ref "BLU55") (pin "GA") (pinfunction "A_GA") (pintype "bidirectional"))
      (node (ref "BLU56") (pin "GC") (pinfunction "K_GC") (pintype "bidirectional"))
    )
    (net (code "100") (name "Net-(BLU57-A)") (class "Default")
      (node (ref "BLU57") (pin "GA") (pinfunction "A_GA") (pintype "bidirectional"))
      (node (ref "BLU58") (pin "GC") (pinfunction "K_GC") (pintype "bidirectional"))
    )
    (net (code "101") (name "Net-(BLU57-K)") (class "Default")
      (node (ref "BLU57") (pin "GC") (pinfunction "K_GC") (pintype "bidirectional"))
      (node (ref "Q10") (pin "5") (pinfunction "C2_5") (pintype "bidirectional"))
      (node (ref "Q10") (pin "56") (pinfunction "C2_56") (pintype "bidirectional"))
      (node (ref "Q10") (pin "6") (pinfunction "C2_6") (pintype "bidirectional"))
    )
    (net (code "102") (name "Net-(BLU58-A)") (class "Default")
      (node (ref "BLU58") (pin "GA") (pinfunction "A_GA") (pintype "bidirectional"))
      (node (ref "BLU59") (pin "GC") (pinfunction "K_GC") (pintype "bidirectional"))
    )
    (net (code "103") (name "Net-(BLU59-A)") (class "Default")
      (node (ref "BLU59") (pin "GA") (pinfunction "A_GA") (pintype "bidirectional"))
      (node (ref "BLU60") (pin "GC") (pinfunction "K_GC") (pintype "bidirectional"))
    )
    (net (code "104") (name "Net-(BLU60-A)") (class "Default")
      (node (ref "BLU60") (pin "GA") (pinfunction "A_GA") (pintype "bidirectional"))
      (node (ref "BLU61") (pin "GC") (pinfunction "K_GC") (pintype "bidirectional"))
    )
    (net (code "105") (name "Net-(BLU61-A)") (class "Default")
      (node (ref "BLU61") (pin "GA") (pinfunction "A_GA") (pintype "bidirectional"))
      (node (ref "BLU62") (pin "GC") (pinfunction "K_GC") (pintype "bidirectional"))
    )
    (net (code "106") (name "Net-(BLU62-A)") (class "Default")
      (node (ref "BLU62") (pin "GA") (pinfunction "A_GA") (pintype "bidirectional"))
      (node (ref "BLU63") (pin "GC") (pinfunction "K_GC") (pintype "bidirectional"))
    )
    (net (code "107") (name "Net-(BLU63-A)") (class "Default")
      (node (ref "BLU63") (pin "GA") (pinfunction "A_GA") (pintype "bidirectional"))
      (node (ref "BLU64") (pin "GC") (pinfunction "K_GC") (pintype "bidirectional"))
    )
    (net (code "108") (name "Net-(C9-Pad2)") (class "Default")
      (node (ref "C9") (pin "2") (pinfunction "2_2") (pintype "passive"))
      (node (ref "L2") (pin "1") (pinfunction "1_1") (pintype "passive"))
      (node (ref "R21") (pin "1") (pinfunction "1_1") (pintype "passive"))
    )
    (net (code "109") (name "Net-(C18-Pad2)") (class "Default")
      (node (ref "C18") (pin "2") (pinfunction "2_2") (pintype "passive"))
      (node (ref "L4") (pin "1") (pinfunction "1_1") (pintype "passive"))
      (node (ref "R55") (pin "1") (pinfunction "1_1") (pintype "passive"))
    )
    (net (code "110") (name "Net-(D1-K)") (class "Default")
      (node (ref "D1") (pin "C") (pinfunction "K_C") (pintype "bidirectional"))
      (node (ref "D2") (pin "A") (pinfunction "A_A") (pintype "bidirectional"))
    )
    (net (code "111") (name "Net-(D2-K)") (class "Default")
      (node (ref "D2") (pin "C") (pinfunction "K_C") (pintype "bidirectional"))
      (node (ref "D3") (pin "A") (pinfunction "A_A") (pintype "bidirectional"))
    )
    (net (code "112") (name "Net-(D3-K)") (class "Default")
      (node (ref "D3") (pin "C") (pinfunction "K_C") (pintype "bidirectional"))
      (node (ref "D4") (pin "A") (pinfunction "A_A") (pintype "bidirectional"))
    )
    (net (code "113") (name "Net-(D4-K)") (class "Default")
      (node (ref "D4") (pin "C") (pinfunction "K_C") (pintype "bidirectional"))
      (node (ref "D5") (pin "A") (pinfunction "A_A") (pintype "bidirectional"))
    )
    (net (code "114") (name "Net-(D5-K)") (class "Default")
      (node (ref "D5") (pin "C") (pinfunction "K_C") (pintype "bidirectional"))
      (node (ref "D6") (pin "A") (pinfunction "A_A") (pintype "bidirectional"))
    )
    (net (code "115") (name "Net-(D6-K)") (class "Default")
      (node (ref "D6") (pin "C") (pinfunction "K_C") (pintype "bidirectional"))
      (node (ref "D7") (pin "A") (pinfunction "A_A") (pintype "bidirectional"))
    )
    (net (code "116") (name "Net-(D7-K)") (class "Default")
      (node (ref "D7") (pin "C") (pinfunction "K_C") (pintype "bidirectional"))
      (node (ref "D8") (pin "A") (pinfunction "A_A") (pintype "bidirectional"))
    )
    (net (code "117") (name "Net-(D8-K)") (class "Default")
      (node (ref "D8") (pin "C") (pinfunction "K_C") (pintype "bidirectional"))
      (node (ref "R1") (pin "2") (pinfunction "2_2") (pintype "passive"))
    )
    (net (code "118") (name "Net-(D9-K)") (class "Default")
      (node (ref "D10") (pin "A") (pinfunction "A_A") (pintype "bidirectional"))
      (node (ref "D9") (pin "C") (pinfunction "K_C") (pintype "bidirectional"))
    )
    (net (code "119") (name "Net-(D9-PadA)") (class "Default")
      (node (ref "D9") (pin "A") (pinfunction "A_A") (pintype "bidirectional"))
      (node (ref "R1") (pin "1") (pinfunction "1_1") (pintype "passive"))
    )
    (net (code "120") (name "Net-(D10-K)") (class "Default")
      (node (ref "D10") (pin "C") (pinfunction "K_C") (pintype "bidirectional"))
      (node (ref "D11") (pin "A") (pinfunction "A_A") (pintype "bidirectional"))
    )
    (net (code "121") (name "Net-(D11-K)") (class "Default")
      (node (ref "D11") (pin "C") (pinfunction "K_C") (pintype "bidirectional"))
      (node (ref "D12") (pin "A") (pinfunction "A_A") (pintype "bidirectional"))
    )
    (net (code "122") (name "Net-(D12-K)") (class "Default")
      (node (ref "D12") (pin "C") (pinfunction "K_C") (pintype "bidirectional"))
      (node (ref "D13") (pin "A") (pinfunction "A_A") (pintype "bidirectional"))
    )
    (net (code "123") (name "Net-(D13-K)") (class "Default")
      (node (ref "D13") (pin "C") (pinfunction "K_C") (pintype "bidirectional"))
      (node (ref "D14") (pin "A") (pinfunction "A_A") (pintype "bidirectional"))
    )
    (net (code "124") (name "Net-(D14-K)") (class "Default")
      (node (ref "D14") (pin "C") (pinfunction "K_C") (pintype "bidirectional"))
      (node (ref "D15") (pin "A") (pinfunction "A_A") (pintype "bidirectional"))
    )
    (net (code "125") (name "Net-(D15-K)") (class "Default")
      (node (ref "D15") (pin "C") (pinfunction "K_C") (pintype "bidirectional"))
      (node (ref "D16") (pin "A") (pinfunction "A_A") (pintype "bidirectional"))
    )
    (net (code "126") (name "Net-(D17-K)") (class "Default")
      (node (ref "D17") (pin "C") (pinfunction "K_C") (pintype "bidirectional"))
      (node (ref "D18") (pin "A") (pinfunction "A_A") (pintype "bidirectional"))
    )
    (net (code "127") (name "Net-(D18-K)") (class "Default")
      (node (ref "D18") (pin "C") (pinfunction "K_C") (pintype "bidirectional"))
      (node (ref "D19") (pin "A") (pinfunction "A_A") (pintype "bidirectional"))
    )
    (net (code "128") (name "Net-(D19-K)") (class "Default")
      (node (ref "D19") (pin "C") (pinfunction "K_C") (pintype "bidirectional"))
      (node (ref "D20") (pin "A") (pinfunction "A_A") (pintype "bidirectional"))
    )
    (net (code "129") (name "Net-(D20-K)") (class "Default")
      (node (ref "D20") (pin "C") (pinfunction "K_C") (pintype "bidirectional"))
      (node (ref "D21") (pin "A") (pinfunction "A_A") (pintype "bidirectional"))
    )
    (net (code "130") (name "Net-(D21-K)") (class "Default")
      (node (ref "D21") (pin "C") (pinfunction "K_C") (pintype "bidirectional"))
      (node (ref "D22") (pin "A") (pinfunction "A_A") (pintype "bidirectional"))
    )
    (net (code "131") (name "Net-(D22-K)") (class "Default")
      (node (ref "D22") (pin "C") (pinfunction "K_C") (pintype "bidirectional"))
      (node (ref "D23") (pin "A") (pinfunction "A_A") (pintype "bidirectional"))
    )
    (net (code "132") (name "Net-(D23-K)") (class "Default")
      (node (ref "D23") (pin "C") (pinfunction "K_C") (pintype "bidirectional"))
      (node (ref "D24") (pin "A") (pinfunction "A_A") (pintype "bidirectional"))
    )
    (net (code "133") (name "Net-(D24-K)") (class "Default")
      (node (ref "D24") (pin "C") (pinfunction "K_C") (pintype "bidirectional"))
      (node (ref "R4") (pin "2") (pinfunction "2_2") (pintype "passive"))
    )
    (net (code "134") (name "Net-(D25-K)") (class "Default")
      (node (ref "D25") (pin "C") (pinfunction "K_C") (pintype "bidirectional"))
      (node (ref "D26") (pin "A") (pinfunction "A_A") (pintype "bidirectional"))
    )
    (net (code "135") (name "Net-(D25-PadA)") (class "Default")
      (node (ref "D25") (pin "A") (pinfunction "A_A") (pintype "bidirectional"))
      (node (ref "R4") (pin "1") (pinfunction "1_1") (pintype "passive"))
    )
    (net (code "136") (name "Net-(D26-K)") (class "Default")
      (node (ref "D26") (pin "C") (pinfunction "K_C") (pintype "bidirectional"))
      (node (ref "D27") (pin "A") (pinfunction "A_A") (pintype "bidirectional"))
    )
    (net (code "137") (name "Net-(D27-K)") (class "Default")
      (node (ref "D27") (pin "C") (pinfunction "K_C") (pintype "bidirectional"))
      (node (ref "D28") (pin "A") (pinfunction "A_A") (pintype "bidirectional"))
    )
    (net (code "138") (name "Net-(D28-K)") (class "Default")
      (node (ref "D28") (pin "C") (pinfunction "K_C") (pintype "bidirectional"))
      (node (ref "D29") (pin "A") (pinfunction "A_A") (pintype "bidirectional"))
    )
    (net (code "139") (name "Net-(D29-K)") (class "Default")
      (node (ref "D29") (pin "C") (pinfunction "K_C") (pintype "bidirectional"))
      (node (ref "D30") (pin "A") (pinfunction "A_A") (pintype "bidirectional"))
    )
    (net (code "140") (name "Net-(D30-K)") (class "Default")
      (node (ref "D30") (pin "C") (pinfunction "K_C") (pintype "bidirectional"))
      (node (ref "D31") (pin "A") (pinfunction "A_A") (pintype "bidirectional"))
    )
    (net (code "141") (name "Net-(D31-K)") (class "Default")
      (node (ref "D31") (pin "C") (pinfunction "K_C") (pintype "bidirectional"))
      (node (ref "D32") (pin "A") (pinfunction "A_A") (pintype "bidirectional"))
    )
    (net (code "142") (name "Net-(D33-K)") (class "Default")
      (node (ref "D33") (pin "C") (pinfunction "K_C") (pintype "bidirectional"))
      (node (ref "D34") (pin "A") (pinfunction "A_A") (pintype "bidirectional"))
    )
    (net (code "143") (name "Net-(D34-K)") (class "Default")
      (node (ref "D34") (pin "C") (pinfunction "K_C") (pintype "bidirectional"))
      (node (ref "D35") (pin "A") (pinfunction "A_A") (pintype "bidirectional"))
    )
    (net (code "144") (name "Net-(D35-K)") (class "Default")
      (node (ref "D35") (pin "C") (pinfunction "K_C") (pintype "bidirectional"))
      (node (ref "D36") (pin "A") (pinfunction "A_A") (pintype "bidirectional"))
    )
    (net (code "145") (name "Net-(D36-K)") (class "Default")
      (node (ref "D36") (pin "C") (pinfunction "K_C") (pintype "bidirectional"))
      (node (ref "D37") (pin "A") (pinfunction "A_A") (pintype "bidirectional"))
    )
    (net (code "146") (name "Net-(D37-K)") (class "Default")
      (node (ref "D37") (pin "C") (pinfunction "K_C") (pintype "bidirectional"))
      (node (ref "D38") (pin "A") (pinfunction "A_A") (pintype "bidirectional"))
    )
    (net (code "147") (name "Net-(D38-K)") (class "Default")
      (node (ref "D38") (pin "C") (pinfunction "K_C") (pintype "bidirectional"))
      (node (ref "D39") (pin "A") (pinfunction "A_A") (pintype "bidirectional"))
    )
    (net (code "148") (name "Net-(D39-K)") (class "Default")
      (node (ref "D39") (pin "C") (pinfunction "K_C") (pintype "bidirectional"))
      (node (ref "D40") (pin "A") (pinfunction "A_A") (pintype "bidirectional"))
    )
    (net (code "149") (name "Net-(D40-K)") (class "Default")
      (node (ref "D40") (pin "C") (pinfunction "K_C") (pintype "bidirectional"))
      (node (ref "R9") (pin "2") (pinfunction "2_2") (pintype "passive"))
    )
    (net (code "150") (name "Net-(D41-K)") (class "Default")
      (node (ref "D41") (pin "C") (pinfunction "K_C") (pintype "bidirectional"))
      (node (ref "D42") (pin "A") (pinfunction "A_A") (pintype "bidirectional"))
    )
    (net (code "151") (name "Net-(D41-PadA)") (class "Default")
      (node (ref "D41") (pin "A") (pinfunction "A_A") (pintype "bidirectional"))
      (node (ref "R9") (pin "1") (pinfunction "1_1") (pintype "passive"))
    )
    (net (code "152") (name "Net-(D42-K)") (class "Default")
      (node (ref "D42") (pin "C") (pinfunction "K_C") (pintype "bidirectional"))
      (node (ref "D43") (pin "A") (pinfunction "A_A") (pintype "bidirectional"))
    )
    (net (code "153") (name "Net-(D43-K)") (class "Default")
      (node (ref "D43") (pin "C") (pinfunction "K_C") (pintype "bidirectional"))
      (node (ref "D44") (pin "A") (pinfunction "A_A") (pintype "bidirectional"))
    )
    (net (code "154") (name "Net-(D44-K)") (class "Default")
      (node (ref "D44") (pin "C") (pinfunction "K_C") (pintype "bidirectional"))
      (node (ref "D45") (pin "A") (pinfunction "A_A") (pintype "bidirectional"))
    )
    (net (code "155") (name "Net-(D45-K)") (class "Default")
      (node (ref "D45") (pin "C") (pinfunction "K_C") (pintype "bidirectional"))
      (node (ref "D46") (pin "A") (pinfunction "A_A") (pintype "bidirectional"))
    )
    (net (code "156") (name "Net-(D46-K)") (class "Default")
      (node (ref "D46") (pin "C") (pinfunction "K_C") (pintype "bidirectional"))
      (node (ref "D47") (pin "A") (pinfunction "A_A") (pintype "bidirectional"))
    )
    (net (code "157") (name "Net-(D47-K)") (class "Default")
      (node (ref "D47") (pin "C") (pinfunction "K_C") (pintype "bidirectional"))
      (node (ref "D48") (pin "A") (pinfunction "A_A") (pintype "bidirectional"))
    )
    (net (code "158") (name "Net-(D50-K)") (class "Default")
      (node (ref "D50") (pin "C") (pinfunction "K_C") (pintype "bidirectional"))
      (node (ref "D51") (pin "A") (pinfunction "A_A") (pintype "bidirectional"))
    )
    (net (code "159") (name "Net-(D51-K)") (class "Default")
      (node (ref "D51") (pin "C") (pinfunction "K_C") (pintype "bidirectional"))
      (node (ref "D52") (pin "A") (pinfunction "A_A") (pintype "bidirectional"))
    )
    (net (code "160") (name "Net-(D52-K)") (class "Default")
      (node (ref "D52") (pin "C") (pinfunction "K_C") (pintype "bidirectional"))
      (node (ref "D53") (pin "A") (pinfunction "A_A") (pintype "bidirectional"))
    )
    (net (code "161") (name "Net-(D53-K)") (class "Default")
      (node (ref "D53") (pin "C") (pinfunction "K_C") (pintype "bidirectional"))
      (node (ref "D54") (pin "A") (pinfunction "A_A") (pintype "bidirectional"))
    )
    (net (code "162") (name "Net-(D54-K)") (class "Default")
      (node (ref "D54") (pin "C") (pinfunction "K_C") (pintype "bidirectional"))
      (node (ref "D55") (pin "A") (pinfunction "A_A") (pintype "bidirectional"))
    )
    (net (code "163") (name "Net-(D55-K)") (class "Default")
      (node (ref "D55") (pin "C") (pinfunction "K_C") (pintype "bidirectional"))
      (node (ref "D56") (pin "A") (pinfunction "A_A") (pintype "bidirectional"))
    )
    (net (code "164") (name "Net-(D56-K)") (class "Default")
      (node (ref "D56") (pin "C") (pinfunction "K_C") (pintype "bidirectional"))
      (node (ref "D57") (pin "A") (pinfunction "A_A") (pintype "bidirectional"))
    )
    (net (code "165") (name "Net-(D57-K)") (class "Default")
      (node (ref "D57") (pin "C") (pinfunction "K_C") (pintype "bidirectional"))
      (node (ref "R12") (pin "2") (pinfunction "2_2") (pintype "passive"))
    )
    (net (code "166") (name "Net-(D58-K)") (class "Default")
      (node (ref "D58") (pin "C") (pinfunction "K_C") (pintype "bidirectional"))
      (node (ref "D59") (pin "A") (pinfunction "A_A") (pintype "bidirectional"))
    )
    (net (code "167") (name "Net-(D58-PadA)") (class "Default")
      (node (ref "D58") (pin "A") (pinfunction "A_A") (pintype "bidirectional"))
      (node (ref "R12") (pin "1") (pinfunction "1_1") (pintype "passive"))
    )
    (net (code "168") (name "Net-(D59-K)") (class "Default")
      (node (ref "D59") (pin "C") (pinfunction "K_C") (pintype "bidirectional"))
      (node (ref "D60") (pin "A") (pinfunction "A_A") (pintype "bidirectional"))
    )
    (net (code "169") (name "Net-(D60-K)") (class "Default")
      (node (ref "D60") (pin "C") (pinfunction "K_C") (pintype "bidirectional"))
      (node (ref "D61") (pin "A") (pinfunction "A_A") (pintype "bidirectional"))
    )
    (net (code "170") (name "Net-(D61-K)") (class "Default")
      (node (ref "D61") (pin "C") (pinfunction "K_C") (pintype "bidirectional"))
      (node (ref "D62") (pin "A") (pinfunction "A_A") (pintype "bidirectional"))
    )
    (net (code "171") (name "Net-(D62-K)") (class "Default")
      (node (ref "D62") (pin "C") (pinfunction "K_C") (pintype "bidirectional"))
      (node (ref "D63") (pin "A") (pinfunction "A_A") (pintype "bidirectional"))
    )
    (net (code "172") (name "Net-(D63-K)") (class "Default")
      (node (ref "D63") (pin "C") (pinfunction "K_C") (pintype "bidirectional"))
      (node (ref "D64") (pin "A") (pinfunction "A_A") (pintype "bidirectional"))
    )
    (net (code "173") (name "Net-(D64-K)") (class "Default")
      (node (ref "D64") (pin "C") (pinfunction "K_C") (pintype "bidirectional"))
      (node (ref "D65") (pin "A") (pinfunction "A_A") (pintype "bidirectional"))
    )
    (net (code "174") (name "Net-(D66-K)") (class "Default")
      (node (ref "D66") (pin "C") (pinfunction "K_C") (pintype "bidirectional"))
      (node (ref "D67") (pin "A") (pinfunction "A_A") (pintype "bidirectional"))
    )
    (net (code "175") (name "Net-(D67-K)") (class "Default")
      (node (ref "D67") (pin "C") (pinfunction "K_C") (pintype "bidirectional"))
      (node (ref "D68") (pin "A") (pinfunction "A_A") (pintype "bidirectional"))
    )
    (net (code "176") (name "Net-(D68-K)") (class "Default")
      (node (ref "D68") (pin "C") (pinfunction "K_C") (pintype "bidirectional"))
      (node (ref "D69") (pin "A") (pinfunction "A_A") (pintype "bidirectional"))
    )
    (net (code "177") (name "Net-(D69-K)") (class "Default")
      (node (ref "D69") (pin "C") (pinfunction "K_C") (pintype "bidirectional"))
      (node (ref "D70") (pin "A") (pinfunction "A_A") (pintype "bidirectional"))
    )
    (net (code "178") (name "Net-(D70-K)") (class "Default")
      (node (ref "D70") (pin "C") (pinfunction "K_C") (pintype "bidirectional"))
      (node (ref "D71") (pin "A") (pinfunction "A_A") (pintype "bidirectional"))
    )
    (net (code "179") (name "Net-(D71-K)") (class "Default")
      (node (ref "D71") (pin "C") (pinfunction "K_C") (pintype "bidirectional"))
      (node (ref "D72") (pin "A") (pinfunction "A_A") (pintype "bidirectional"))
    )
    (net (code "180") (name "Net-(D72-K)") (class "Default")
      (node (ref "D72") (pin "C") (pinfunction "K_C") (pintype "bidirectional"))
      (node (ref "D73") (pin "A") (pinfunction "A_A") (pintype "bidirectional"))
    )
    (net (code "181") (name "Net-(D73-K)") (class "Default")
      (node (ref "D73") (pin "C") (pinfunction "K_C") (pintype "bidirectional"))
      (node (ref "R23") (pin "2") (pinfunction "2_2") (pintype "passive"))
    )
    (net (code "182") (name "Net-(D74-K)") (class "Default")
      (node (ref "D74") (pin "C") (pinfunction "K_C") (pintype "bidirectional"))
      (node (ref "D75") (pin "A") (pinfunction "A_A") (pintype "bidirectional"))
    )
    (net (code "183") (name "Net-(D74-PadA)") (class "Default")
      (node (ref "D74") (pin "A") (pinfunction "A_A") (pintype "bidirectional"))
      (node (ref "R23") (pin "1") (pinfunction "1_1") (pintype "passive"))
    )
    (net (code "184") (name "Net-(D75-K)") (class "Default")
      (node (ref "D75") (pin "C") (pinfunction "K_C") (pintype "bidirectional"))
      (node (ref "D76") (pin "A") (pinfunction "A_A") (pintype "bidirectional"))
    )
    (net (code "185") (name "Net-(D76-K)") (class "Default")
      (node (ref "D76") (pin "C") (pinfunction "K_C") (pintype "bidirectional"))
      (node (ref "D77") (pin "A") (pinfunction "A_A") (pintype "bidirectional"))
    )
    (net (code "186") (name "Net-(D77-K)") (class "Default")
      (node (ref "D77") (pin "C") (pinfunction "K_C") (pintype "bidirectional"))
      (node (ref "D78") (pin "A") (pinfunction "A_A") (pintype "bidirectional"))
    )
    (net (code "187") (name "Net-(D78-K)") (class "Default")
      (node (ref "D78") (pin "C") (pinfunction "K_C") (pintype "bidirectional"))
      (node (ref "D79") (pin "A") (pinfunction "A_A") (pintype "bidirectional"))
    )
    (net (code "188") (name "Net-(D79-K)") (class "Default")
      (node (ref "D79") (pin "C") (pinfunction "K_C") (pintype "bidirectional"))
      (node (ref "D80") (pin "A") (pinfunction "A_A") (pintype "bidirectional"))
    )
    (net (code "189") (name "Net-(D80-K)") (class "Default")
      (node (ref "D80") (pin "C") (pinfunction "K_C") (pintype "bidirectional"))
      (node (ref "D81") (pin "A") (pinfunction "A_A") (pintype "bidirectional"))
    )
    (net (code "190") (name "Net-(D83-K)") (class "Default")
      (node (ref "D83") (pin "C") (pinfunction "K_C") (pintype "bidirectional"))
      (node (ref "D84") (pin "A") (pinfunction "A_A") (pintype "bidirectional"))
    )
    (net (code "191") (name "Net-(D84-K)") (class "Default")
      (node (ref "D84") (pin "C") (pinfunction "K_C") (pintype "bidirectional"))
      (node (ref "D85") (pin "A") (pinfunction "A_A") (pintype "bidirectional"))
    )
    (net (code "192") (name "Net-(D85-K)") (class "Default")
      (node (ref "D85") (pin "C") (pinfunction "K_C") (pintype "bidirectional"))
      (node (ref "D86") (pin "A") (pinfunction "A_A") (pintype "bidirectional"))
    )
    (net (code "193") (name "Net-(D86-K)") (class "Default")
      (node (ref "D86") (pin "C") (pinfunction "K_C") (pintype "bidirectional"))
      (node (ref "D87") (pin "A") (pinfunction "A_A") (pintype "bidirectional"))
    )
    (net (code "194") (name "Net-(D87-K)") (class "Default")
      (node (ref "D87") (pin "C") (pinfunction "K_C") (pintype "bidirectional"))
      (node (ref "D88") (pin "A") (pinfunction "A_A") (pintype "bidirectional"))
    )
    (net (code "195") (name "Net-(D88-K)") (class "Default")
      (node (ref "D88") (pin "C") (pinfunction "K_C") (pintype "bidirectional"))
      (node (ref "D89") (pin "A") (pinfunction "A_A") (pintype "bidirectional"))
    )
    (net (code "196") (name "Net-(D89-K)") (class "Default")
      (node (ref "D89") (pin "C") (pinfunction "K_C") (pintype "bidirectional"))
      (node (ref "D90") (pin "A") (pinfunction "A_A") (pintype "bidirectional"))
    )
    (net (code "197") (name "Net-(D90-K)") (class "Default")
      (node (ref "D90") (pin "C") (pinfunction "K_C") (pintype "bidirectional"))
      (node (ref "R26") (pin "2") (pinfunction "2_2") (pintype "passive"))
    )
    (net (code "198") (name "Net-(D91-K)") (class "Default")
      (node (ref "D91") (pin "C") (pinfunction "K_C") (pintype "bidirectional"))
      (node (ref "D92") (pin "A") (pinfunction "A_A") (pintype "bidirectional"))
    )
    (net (code "199") (name "Net-(D91-PadA)") (class "Default")
      (node (ref "D91") (pin "A") (pinfunction "A_A") (pintype "bidirectional"))
      (node (ref "R26") (pin "1") (pinfunction "1_1") (pintype "passive"))
    )
    (net (code "200") (name "Net-(D92-K)") (class "Default")
      (node (ref "D92") (pin "C") (pinfunction "K_C") (pintype "bidirectional"))
      (node (ref "D93") (pin "A") (pinfunction "A_A") (pintype "bidirectional"))
    )
    (net (code "201") (name "Net-(D93-K)") (class "Default")
      (node (ref "D93") (pin "C") (pinfunction "K_C") (pintype "bidirectional"))
      (node (ref "D94") (pin "A") (pinfunction "A_A") (pintype "bidirectional"))
    )
    (net (code "202") (name "Net-(D94-K)") (class "Default")
      (node (ref "D94") (pin "C") (pinfunction "K_C") (pintype "bidirectional"))
      (node (ref "D95") (pin "A") (pinfunction "A_A") (pintype "bidirectional"))
    )
    (net (code "203") (name "Net-(D95-K)") (class "Default")
      (node (ref "D95") (pin "C") (pinfunction "K_C") (pintype "bidirectional"))
      (node (ref "D96") (pin "A") (pinfunction "A_A") (pintype "bidirectional"))
    )
    (net (code "204") (name "Net-(D96-K)") (class "Default")
      (node (ref "D96") (pin "C") (pinfunction "K_C") (pintype "bidirectional"))
      (node (ref "D97") (pin "A") (pinfunction "A_A") (pintype "bidirectional"))
    )
    (net (code "205") (name "Net-(D97-K)") (class "Default")
      (node (ref "D97") (pin "C") (pinfunction "K_C") (pintype "bidirectional"))
      (node (ref "D98") (pin "A") (pinfunction "A_A") (pintype "bidirectional"))
    )
    (net (code "206") (name "Net-(D99-K)") (class "Default")
      (node (ref "D100") (pin "A") (pinfunction "A_A") (pintype "bidirectional"))
      (node (ref "D99") (pin "C") (pinfunction "K_C") (pintype "bidirectional"))
    )
    (net (code "207") (name "Net-(D100-K)") (class "Default")
      (node (ref "D100") (pin "C") (pinfunction "K_C") (pintype "bidirectional"))
      (node (ref "D101") (pin "A") (pinfunction "A_A") (pintype "bidirectional"))
    )
    (net (code "208") (name "Net-(D101-K)") (class "Default")
      (node (ref "D101") (pin "C") (pinfunction "K_C") (pintype "bidirectional"))
      (node (ref "D102") (pin "A") (pinfunction "A_A") (pintype "bidirectional"))
    )
    (net (code "209") (name "Net-(D102-K)") (class "Default")
      (node (ref "D102") (pin "C") (pinfunction "K_C") (pintype "bidirectional"))
      (node (ref "D103") (pin "A") (pinfunction "A_A") (pintype "bidirectional"))
    )
    (net (code "210") (name "Net-(D103-K)") (class "Default")
      (node (ref "D103") (pin "C") (pinfunction "K_C") (pintype "bidirectional"))
      (node (ref "D104") (pin "A") (pinfunction "A_A") (pintype "bidirectional"))
    )
    (net (code "211") (name "Net-(D104-K)") (class "Default")
      (node (ref "D104") (pin "C") (pinfunction "K_C") (pintype "bidirectional"))
      (node (ref "D105") (pin "A") (pinfunction "A_A") (pintype "bidirectional"))
    )
    (net (code "212") (name "Net-(D105-K)") (class "Default")
      (node (ref "D105") (pin "C") (pinfunction "K_C") (pintype "bidirectional"))
      (node (ref "D106") (pin "A") (pinfunction "A_A") (pintype "bidirectional"))
    )
    (net (code "213") (name "Net-(D106-K)") (class "Default")
      (node (ref "D106") (pin "C") (pinfunction "K_C") (pintype "bidirectional"))
      (node (ref "R30") (pin "2") (pinfunction "2_2") (pintype "passive"))
    )
    (net (code "214") (name "Net-(D107-K)") (class "Default")
      (node (ref "D107") (pin "C") (pinfunction "K_C") (pintype "bidirectional"))
      (node (ref "D108") (pin "A") (pinfunction "A_A") (pintype "bidirectional"))
    )
    (net (code "215") (name "Net-(D107-PadA)") (class "Default")
      (node (ref "D107") (pin "A") (pinfunction "A_A") (pintype "bidirectional"))
      (node (ref "R30") (pin "1") (pinfunction "1_1") (pintype "passive"))
    )
    (net (code "216") (name "Net-(D108-K)") (class "Default")
      (node (ref "D108") (pin "C") (pinfunction "K_C") (pintype "bidirectional"))
      (node (ref "D109") (pin "A") (pinfunction "A_A") (pintype "bidirectional"))
    )
    (net (code "217") (name "Net-(D109-K)") (class "Default")
      (node (ref "D109") (pin "C") (pinfunction "K_C") (pintype "bidirectional"))
      (node (ref "D110") (pin "A") (pinfunction "A_A") (pintype "bidirectional"))
    )
    (net (code "218") (name "Net-(D110-K)") (class "Default")
      (node (ref "D110") (pin "C") (pinfunction "K_C") (pintype "bidirectional"))
      (node (ref "D111") (pin "A") (pinfunction "A_A") (pintype "bidirectional"))
    )
    (net (code "219") (name "Net-(D111-K)") (class "Default")
      (node (ref "D111") (pin "C") (pinfunction "K_C") (pintype "bidirectional"))
      (node (ref "D112") (pin "A") (pinfunction "A_A") (pintype "bidirectional"))
    )
    (net (code "220") (name "Net-(D112-K)") (class "Default")
      (node (ref "D112") (pin "C") (pinfunction "K_C") (pintype "bidirectional"))
      (node (ref "D113") (pin "A") (pinfunction "A_A") (pintype "bidirectional"))
    )
    (net (code "221") (name "Net-(D113-K)") (class "Default")
      (node (ref "D113") (pin "C") (pinfunction "K_C") (pintype "bidirectional"))
      (node (ref "D114") (pin "A") (pinfunction "A_A") (pintype "bidirectional"))
    )
    (net (code "222") (name "Net-(D115-K)") (class "Default")
      (node (ref "D115") (pin "C") (pinfunction "K_C") (pintype "bidirectional"))
      (node (ref "D116") (pin "A") (pinfunction "A_A") (pintype "bidirectional"))
    )
    (net (code "223") (name "Net-(D116-K)") (class "Default")
      (node (ref "D116") (pin "C") (pinfunction "K_C") (pintype "bidirectional"))
      (node (ref "D117") (pin "A") (pinfunction "A_A") (pintype "bidirectional"))
    )
    (net (code "224") (name "Net-(D117-K)") (class "Default")
      (node (ref "D117") (pin "C") (pinfunction "K_C") (pintype "bidirectional"))
      (node (ref "D118") (pin "A") (pinfunction "A_A") (pintype "bidirectional"))
    )
    (net (code "225") (name "Net-(D118-K)") (class "Default")
      (node (ref "D118") (pin "C") (pinfunction "K_C") (pintype "bidirectional"))
      (node (ref "D119") (pin "A") (pinfunction "A_A") (pintype "bidirectional"))
    )
    (net (code "226") (name "Net-(D119-K)") (class "Default")
      (node (ref "D119") (pin "C") (pinfunction "K_C") (pintype "bidirectional"))
      (node (ref "D120") (pin "A") (pinfunction "A_A") (pintype "bidirectional"))
    )
    (net (code "227") (name "Net-(D120-K)") (class "Default")
      (node (ref "D120") (pin "C") (pinfunction "K_C") (pintype "bidirectional"))
      (node (ref "D121") (pin "A") (pinfunction "A_A") (pintype "bidirectional"))
    )
    (net (code "228") (name "Net-(D121-K)") (class "Default")
      (node (ref "D121") (pin "C") (pinfunction "K_C") (pintype "bidirectional"))
      (node (ref "D122") (pin "A") (pinfunction "A_A") (pintype "bidirectional"))
    )
    (net (code "229") (name "Net-(D122-K)") (class "Default")
      (node (ref "D122") (pin "C") (pinfunction "K_C") (pintype "bidirectional"))
      (node (ref "R34") (pin "2") (pinfunction "2_2") (pintype "passive"))
    )
    (net (code "230") (name "Net-(D123-K)") (class "Default")
      (node (ref "D123") (pin "C") (pinfunction "K_C") (pintype "bidirectional"))
      (node (ref "D124") (pin "A") (pinfunction "A_A") (pintype "bidirectional"))
    )
    (net (code "231") (name "Net-(D123-PadA)") (class "Default")
      (node (ref "D123") (pin "A") (pinfunction "A_A") (pintype "bidirectional"))
      (node (ref "R34") (pin "1") (pinfunction "1_1") (pintype "passive"))
    )
    (net (code "232") (name "Net-(D124-K)") (class "Default")
      (node (ref "D124") (pin "C") (pinfunction "K_C") (pintype "bidirectional"))
      (node (ref "D125") (pin "A") (pinfunction "A_A") (pintype "bidirectional"))
    )
    (net (code "233") (name "Net-(D125-K)") (class "Default")
      (node (ref "D125") (pin "C") (pinfunction "K_C") (pintype "bidirectional"))
      (node (ref "D126") (pin "A") (pinfunction "A_A") (pintype "bidirectional"))
    )
    (net (code "234") (name "Net-(D126-K)") (class "Default")
      (node (ref "D126") (pin "C") (pinfunction "K_C") (pintype "bidirectional"))
      (node (ref "D127") (pin "A") (pinfunction "A_A") (pintype "bidirectional"))
    )
    (net (code "235") (name "Net-(D127-K)") (class "Default")
      (node (ref "D127") (pin "C") (pinfunction "K_C") (pintype "bidirectional"))
      (node (ref "D128") (pin "A") (pinfunction "A_A") (pintype "bidirectional"))
    )
    (net (code "236") (name "Net-(D128-K)") (class "Default")
      (node (ref "D128") (pin "C") (pinfunction "K_C") (pintype "bidirectional"))
      (node (ref "D129") (pin "A") (pinfunction "A_A") (pintype "bidirectional"))
    )
    (net (code "237") (name "Net-(D129-K)") (class "Default")
      (node (ref "D129") (pin "C") (pinfunction "K_C") (pintype "bidirectional"))
      (node (ref "D130") (pin "A") (pinfunction "A_A") (pintype "bidirectional"))
    )
    (net (code "238") (name "Net-(D131-K)") (class "Default")
      (node (ref "D131") (pin "C") (pinfunction "K_C") (pintype "bidirectional"))
      (node (ref "D132") (pin "A") (pinfunction "A_A") (pintype "bidirectional"))
    )
    (net (code "239") (name "Net-(D132-K)") (class "Default")
      (node (ref "D132") (pin "C") (pinfunction "K_C") (pintype "bidirectional"))
      (node (ref "D133") (pin "A") (pinfunction "A_A") (pintype "bidirectional"))
    )
    (net (code "240") (name "Net-(D133-K)") (class "Default")
      (node (ref "D133") (pin "C") (pinfunction "K_C") (pintype "bidirectional"))
      (node (ref "D134") (pin "A") (pinfunction "A_A") (pintype "bidirectional"))
    )
    (net (code "241") (name "Net-(D134-K)") (class "Default")
      (node (ref "D134") (pin "C") (pinfunction "K_C") (pintype "bidirectional"))
      (node (ref "D135") (pin "A") (pinfunction "A_A") (pintype "bidirectional"))
    )
    (net (code "242") (name "Net-(D135-K)") (class "Default")
      (node (ref "D135") (pin "C") (pinfunction "K_C") (pintype "bidirectional"))
      (node (ref "D136") (pin "A") (pinfunction "A_A") (pintype "bidirectional"))
    )
    (net (code "243") (name "Net-(D136-K)") (class "Default")
      (node (ref "D136") (pin "C") (pinfunction "K_C") (pintype "bidirectional"))
      (node (ref "D137") (pin "A") (pinfunction "A_A") (pintype "bidirectional"))
    )
    (net (code "244") (name "Net-(D137-K)") (class "Default")
      (node (ref "D137") (pin "C") (pinfunction "K_C") (pintype "bidirectional"))
      (node (ref "D138") (pin "A") (pinfunction "A_A") (pintype "bidirectional"))
    )
    (net (code "245") (name "Net-(D138-K)") (class "Default")
      (node (ref "D138") (pin "C") (pinfunction "K_C") (pintype "bidirectional"))
      (node (ref "R35") (pin "2") (pinfunction "2_2") (pintype "passive"))
    )
    (net (code "246") (name "Net-(D139-K)") (class "Default")
      (node (ref "D139") (pin "C") (pinfunction "K_C") (pintype "bidirectional"))
      (node (ref "D140") (pin "A") (pinfunction "A_A") (pintype "bidirectional"))
    )
    (net (code "247") (name "Net-(D139-PadA)") (class "Default")
      (node (ref "D139") (pin "A") (pinfunction "A_A") (pintype "bidirectional"))
      (node (ref "R35") (pin "1") (pinfunction "1_1") (pintype "passive"))
    )
    (net (code "248") (name "Net-(D140-K)") (class "Default")
      (node (ref "D140") (pin "C") (pinfunction "K_C") (pintype "bidirectional"))
      (node (ref "D141") (pin "A") (pinfunction "A_A") (pintype "bidirectional"))
    )
    (net (code "249") (name "Net-(D141-K)") (class "Default")
      (node (ref "D141") (pin "C") (pinfunction "K_C") (pintype "bidirectional"))
      (node (ref "D142") (pin "A") (pinfunction "A_A") (pintype "bidirectional"))
    )
    (net (code "250") (name "Net-(D142-K)") (class "Default")
      (node (ref "D142") (pin "C") (pinfunction "K_C") (pintype "bidirectional"))
      (node (ref "D143") (pin "A") (pinfunction "A_A") (pintype "bidirectional"))
    )
    (net (code "251") (name "Net-(D143-K)") (class "Default")
      (node (ref "D143") (pin "C") (pinfunction "K_C") (pintype "bidirectional"))
      (node (ref "D144") (pin "A") (pinfunction "A_A") (pintype "bidirectional"))
    )
    (net (code "252") (name "Net-(D144-K)") (class "Default")
      (node (ref "D144") (pin "C") (pinfunction "K_C") (pintype "bidirectional"))
      (node (ref "D145") (pin "A") (pinfunction "A_A") (pintype "bidirectional"))
    )
    (net (code "253") (name "Net-(D145-K)") (class "Default")
      (node (ref "D145") (pin "C") (pinfunction "K_C") (pintype "bidirectional"))
      (node (ref "D146") (pin "A") (pinfunction "A_A") (pintype "bidirectional"))
    )
    (net (code "254") (name "Net-(D147-K)") (class "Default")
      (node (ref "D147") (pin "C") (pinfunction "K_C") (pintype "bidirectional"))
      (node (ref "D148") (pin "A") (pinfunction "A_A") (pintype "bidirectional"))
    )
    (net (code "255") (name "Net-(D148-K)") (class "Default")
      (node (ref "D148") (pin "C") (pinfunction "K_C") (pintype "bidirectional"))
      (node (ref "D149") (pin "A") (pinfunction "A_A") (pintype "bidirectional"))
    )
    (net (code "256") (name "Net-(D149-K)") (class "Default")
      (node (ref "D149") (pin "C") (pinfunction "K_C") (pintype "bidirectional"))
      (node (ref "D150") (pin "A") (pinfunction "A_A") (pintype "bidirectional"))
    )
    (net (code "257") (name "Net-(D150-K)") (class "Default")
      (node (ref "D150") (pin "C") (pinfunction "K_C") (pintype "bidirectional"))
      (node (ref "D151") (pin "A") (pinfunction "A_A") (pintype "bidirectional"))
    )
    (net (code "258") (name "Net-(D151-K)") (class "Default")
      (node (ref "D151") (pin "C") (pinfunction "K_C") (pintype "bidirectional"))
      (node (ref "D152") (pin "A") (pinfunction "A_A") (pintype "bidirectional"))
    )
    (net (code "259") (name "Net-(D152-K)") (class "Default")
      (node (ref "D152") (pin "C") (pinfunction "K_C") (pintype "bidirectional"))
      (node (ref "D153") (pin "A") (pinfunction "A_A") (pintype "bidirectional"))
    )
    (net (code "260") (name "Net-(D153-K)") (class "Default")
      (node (ref "D153") (pin "C") (pinfunction "K_C") (pintype "bidirectional"))
      (node (ref "D154") (pin "A") (pinfunction "A_A") (pintype "bidirectional"))
    )
    (net (code "261") (name "Net-(D154-K)") (class "Default")
      (node (ref "D154") (pin "C") (pinfunction "K_C") (pintype "bidirectional"))
      (node (ref "R38") (pin "2") (pinfunction "2_2") (pintype "passive"))
    )
    (net (code "262") (name "Net-(D155-K)") (class "Default")
      (node (ref "D155") (pin "C") (pinfunction "K_C") (pintype "bidirectional"))
      (node (ref "D156") (pin "A") (pinfunction "A_A") (pintype "bidirectional"))
    )
    (net (code "263") (name "Net-(D155-PadA)") (class "Default")
      (node (ref "D155") (pin "A") (pinfunction "A_A") (pintype "bidirectional"))
      (node (ref "R38") (pin "1") (pinfunction "1_1") (pintype "passive"))
    )
    (net (code "264") (name "Net-(D156-K)") (class "Default")
      (node (ref "D156") (pin "C") (pinfunction "K_C") (pintype "bidirectional"))
      (node (ref "D157") (pin "A") (pinfunction "A_A") (pintype "bidirectional"))
    )
    (net (code "265") (name "Net-(D157-K)") (class "Default")
      (node (ref "D157") (pin "C") (pinfunction "K_C") (pintype "bidirectional"))
      (node (ref "D158") (pin "A") (pinfunction "A_A") (pintype "bidirectional"))
    )
    (net (code "266") (name "Net-(D158-K)") (class "Default")
      (node (ref "D158") (pin "C") (pinfunction "K_C") (pintype "bidirectional"))
      (node (ref "D159") (pin "A") (pinfunction "A_A") (pintype "bidirectional"))
    )
    (net (code "267") (name "Net-(D159-K)") (class "Default")
      (node (ref "D159") (pin "C") (pinfunction "K_C") (pintype "bidirectional"))
      (node (ref "D160") (pin "A") (pinfunction "A_A") (pintype "bidirectional"))
    )
    (net (code "268") (name "Net-(D160-K)") (class "Default")
      (node (ref "D160") (pin "C") (pinfunction "K_C") (pintype "bidirectional"))
      (node (ref "D161") (pin "A") (pinfunction "A_A") (pintype "bidirectional"))
    )
    (net (code "269") (name "Net-(D161-K)") (class "Default")
      (node (ref "D161") (pin "C") (pinfunction "K_C") (pintype "bidirectional"))
      (node (ref "D162") (pin "A") (pinfunction "A_A") (pintype "bidirectional"))
    )
    (net (code "270") (name "Net-(D163-K)") (class "Default")
      (node (ref "D163") (pin "C") (pinfunction "K_C") (pintype "bidirectional"))
      (node (ref "D164") (pin "A") (pinfunction "A_A") (pintype "bidirectional"))
    )
    (net (code "271") (name "Net-(D164-K)") (class "Default")
      (node (ref "D164") (pin "C") (pinfunction "K_C") (pintype "bidirectional"))
      (node (ref "D165") (pin "A") (pinfunction "A_A") (pintype "bidirectional"))
    )
    (net (code "272") (name "Net-(D165-K)") (class "Default")
      (node (ref "D165") (pin "C") (pinfunction "K_C") (pintype "bidirectional"))
      (node (ref "D166") (pin "A") (pinfunction "A_A") (pintype "bidirectional"))
    )
    (net (code "273") (name "Net-(D166-K)") (class "Default")
      (node (ref "D166") (pin "C") (pinfunction "K_C") (pintype "bidirectional"))
      (node (ref "D167") (pin "A") (pinfunction "A_A") (pintype "bidirectional"))
    )
    (net (code "274") (name "Net-(D167-K)") (class "Default")
      (node (ref "D167") (pin "C") (pinfunction "K_C") (pintype "bidirectional"))
      (node (ref "D168") (pin "A") (pinfunction "A_A") (pintype "bidirectional"))
    )
    (net (code "275") (name "Net-(D168-K)") (class "Default")
      (node (ref "D168") (pin "C") (pinfunction "K_C") (pintype "bidirectional"))
      (node (ref "D169") (pin "A") (pinfunction "A_A") (pintype "bidirectional"))
    )
    (net (code "276") (name "Net-(D169-K)") (class "Default")
      (node (ref "D169") (pin "C") (pinfunction "K_C") (pintype "bidirectional"))
      (node (ref "D170") (pin "A") (pinfunction "A_A") (pintype "bidirectional"))
    )
    (net (code "277") (name "Net-(D170-K)") (class "Default")
      (node (ref "D170") (pin "C") (pinfunction "K_C") (pintype "bidirectional"))
      (node (ref "R43") (pin "2") (pinfunction "2_2") (pintype "passive"))
    )
    (net (code "278") (name "Net-(D171-K)") (class "Default")
      (node (ref "D171") (pin "C") (pinfunction "K_C") (pintype "bidirectional"))
      (node (ref "D172") (pin "A") (pinfunction "A_A") (pintype "bidirectional"))
    )
    (net (code "279") (name "Net-(D171-PadA)") (class "Default")
      (node (ref "D171") (pin "A") (pinfunction "A_A") (pintype "bidirectional"))
      (node (ref "R43") (pin "1") (pinfunction "1_1") (pintype "passive"))
    )
    (net (code "280") (name "Net-(D172-K)") (class "Default")
      (node (ref "D172") (pin "C") (pinfunction "K_C") (pintype "bidirectional"))
      (node (ref "D173") (pin "A") (pinfunction "A_A") (pintype "bidirectional"))
    )
    (net (code "281") (name "Net-(D173-K)") (class "Default")
      (node (ref "D173") (pin "C") (pinfunction "K_C") (pintype "bidirectional"))
      (node (ref "D174") (pin "A") (pinfunction "A_A") (pintype "bidirectional"))
    )
    (net (code "282") (name "Net-(D174-K)") (class "Default")
      (node (ref "D174") (pin "C") (pinfunction "K_C") (pintype "bidirectional"))
      (node (ref "D175") (pin "A") (pinfunction "A_A") (pintype "bidirectional"))
    )
    (net (code "283") (name "Net-(D175-K)") (class "Default")
      (node (ref "D175") (pin "C") (pinfunction "K_C") (pintype "bidirectional"))
      (node (ref "D176") (pin "A") (pinfunction "A_A") (pintype "bidirectional"))
    )
    (net (code "284") (name "Net-(D176-K)") (class "Default")
      (node (ref "D176") (pin "C") (pinfunction "K_C") (pintype "bidirectional"))
      (node (ref "D177") (pin "A") (pinfunction "A_A") (pintype "bidirectional"))
    )
    (net (code "285") (name "Net-(D177-K)") (class "Default")
      (node (ref "D177") (pin "C") (pinfunction "K_C") (pintype "bidirectional"))
      (node (ref "D178") (pin "A") (pinfunction "A_A") (pintype "bidirectional"))
    )
    (net (code "286") (name "Net-(D180-K)") (class "Default")
      (node (ref "D180") (pin "C") (pinfunction "K_C") (pintype "bidirectional"))
      (node (ref "D181") (pin "A") (pinfunction "A_A") (pintype "bidirectional"))
    )
    (net (code "287") (name "Net-(D181-K)") (class "Default")
      (node (ref "D181") (pin "C") (pinfunction "K_C") (pintype "bidirectional"))
      (node (ref "D182") (pin "A") (pinfunction "A_A") (pintype "bidirectional"))
    )
    (net (code "288") (name "Net-(D182-K)") (class "Default")
      (node (ref "D182") (pin "C") (pinfunction "K_C") (pintype "bidirectional"))
      (node (ref "D183") (pin "A") (pinfunction "A_A") (pintype "bidirectional"))
    )
    (net (code "289") (name "Net-(D183-K)") (class "Default")
      (node (ref "D183") (pin "C") (pinfunction "K_C") (pintype "bidirectional"))
      (node (ref "D184") (pin "A") (pinfunction "A_A") (pintype "bidirectional"))
    )
    (net (code "290") (name "Net-(D184-K)") (class "Default")
      (node (ref "D184") (pin "C") (pinfunction "K_C") (pintype "bidirectional"))
      (node (ref "D185") (pin "A") (pinfunction "A_A") (pintype "bidirectional"))
    )
    (net (code "291") (name "Net-(D185-K)") (class "Default")
      (node (ref "D185") (pin "C") (pinfunction "K_C") (pintype "bidirectional"))
      (node (ref "D186") (pin "A") (pinfunction "A_A") (pintype "bidirectional"))
    )
    (net (code "292") (name "Net-(D186-K)") (class "Default")
      (node (ref "D186") (pin "C") (pinfunction "K_C") (pintype "bidirectional"))
      (node (ref "D187") (pin "A") (pinfunction "A_A") (pintype "bidirectional"))
    )
    (net (code "293") (name "Net-(D187-K)") (class "Default")
      (node (ref "D187") (pin "C") (pinfunction "K_C") (pintype "bidirectional"))
      (node (ref "R46") (pin "2") (pinfunction "2_2") (pintype "passive"))
    )
    (net (code "294") (name "Net-(D188-K)") (class "Default")
      (node (ref "D188") (pin "C") (pinfunction "K_C") (pintype "bidirectional"))
      (node (ref "D189") (pin "A") (pinfunction "A_A") (pintype "bidirectional"))
    )
    (net (code "295") (name "Net-(D188-PadA)") (class "Default")
      (node (ref "D188") (pin "A") (pinfunction "A_A") (pintype "bidirectional"))
      (node (ref "R46") (pin "1") (pinfunction "1_1") (pintype "passive"))
    )
    (net (code "296") (name "Net-(D189-K)") (class "Default")
      (node (ref "D189") (pin "C") (pinfunction "K_C") (pintype "bidirectional"))
      (node (ref "D190") (pin "A") (pinfunction "A_A") (pintype "bidirectional"))
    )
    (net (code "297") (name "Net-(D190-K)") (class "Default")
      (node (ref "D190") (pin "C") (pinfunction "K_C") (pintype "bidirectional"))
      (node (ref "D191") (pin "A") (pinfunction "A_A") (pintype "bidirectional"))
    )
    (net (code "298") (name "Net-(D191-K)") (class "Default")
      (node (ref "D191") (pin "C") (pinfunction "K_C") (pintype "bidirectional"))
      (node (ref "D192") (pin "A") (pinfunction "A_A") (pintype "bidirectional"))
    )
    (net (code "299") (name "Net-(D192-K)") (class "Default")
      (node (ref "D192") (pin "C") (pinfunction "K_C") (pintype "bidirectional"))
      (node (ref "D193") (pin "A") (pinfunction "A_A") (pintype "bidirectional"))
    )
    (net (code "300") (name "Net-(D193-K)") (class "Default")
      (node (ref "D193") (pin "C") (pinfunction "K_C") (pintype "bidirectional"))
      (node (ref "D194") (pin "A") (pinfunction "A_A") (pintype "bidirectional"))
    )
    (net (code "301") (name "Net-(D194-K)") (class "Default")
      (node (ref "D194") (pin "C") (pinfunction "K_C") (pintype "bidirectional"))
      (node (ref "D195") (pin "A") (pinfunction "A_A") (pintype "bidirectional"))
    )
    (net (code "302") (name "Net-(D196-K)") (class "Default")
      (node (ref "D196") (pin "C") (pinfunction "K_C") (pintype "bidirectional"))
      (node (ref "D197") (pin "A") (pinfunction "A_A") (pintype "bidirectional"))
    )
    (net (code "303") (name "Net-(D197-K)") (class "Default")
      (node (ref "D197") (pin "C") (pinfunction "K_C") (pintype "bidirectional"))
      (node (ref "D198") (pin "A") (pinfunction "A_A") (pintype "bidirectional"))
    )
    (net (code "304") (name "Net-(D198-K)") (class "Default")
      (node (ref "D198") (pin "C") (pinfunction "K_C") (pintype "bidirectional"))
      (node (ref "D199") (pin "A") (pinfunction "A_A") (pintype "bidirectional"))
    )
    (net (code "305") (name "Net-(D199-K)") (class "Default")
      (node (ref "D199") (pin "C") (pinfunction "K_C") (pintype "bidirectional"))
      (node (ref "D200") (pin "A") (pinfunction "A_A") (pintype "bidirectional"))
    )
    (net (code "306") (name "Net-(D200-K)") (class "Default")
      (node (ref "D200") (pin "C") (pinfunction "K_C") (pintype "bidirectional"))
      (node (ref "D201") (pin "A") (pinfunction "A_A") (pintype "bidirectional"))
    )
    (net (code "307") (name "Net-(D201-K)") (class "Default")
      (node (ref "D201") (pin "C") (pinfunction "K_C") (pintype "bidirectional"))
      (node (ref "D202") (pin "A") (pinfunction "A_A") (pintype "bidirectional"))
    )
    (net (code "308") (name "Net-(D202-K)") (class "Default")
      (node (ref "D202") (pin "C") (pinfunction "K_C") (pintype "bidirectional"))
      (node (ref "D203") (pin "A") (pinfunction "A_A") (pintype "bidirectional"))
    )
    (net (code "309") (name "Net-(D203-K)") (class "Default")
      (node (ref "D203") (pin "C") (pinfunction "K_C") (pintype "bidirectional"))
      (node (ref "R57") (pin "2") (pinfunction "2_2") (pintype "passive"))
    )
    (net (code "310") (name "Net-(D204-K)") (class "Default")
      (node (ref "D204") (pin "C") (pinfunction "K_C") (pintype "bidirectional"))
      (node (ref "D205") (pin "A") (pinfunction "A_A") (pintype "bidirectional"))
    )
    (net (code "311") (name "Net-(D204-PadA)") (class "Default")
      (node (ref "D204") (pin "A") (pinfunction "A_A") (pintype "bidirectional"))
      (node (ref "R57") (pin "1") (pinfunction "1_1") (pintype "passive"))
    )
    (net (code "312") (name "Net-(D205-K)") (class "Default")
      (node (ref "D205") (pin "C") (pinfunction "K_C") (pintype "bidirectional"))
      (node (ref "D206") (pin "A") (pinfunction "A_A") (pintype "bidirectional"))
    )
    (net (code "313") (name "Net-(D206-K)") (class "Default")
      (node (ref "D206") (pin "C") (pinfunction "K_C") (pintype "bidirectional"))
      (node (ref "D207") (pin "A") (pinfunction "A_A") (pintype "bidirectional"))
    )
    (net (code "314") (name "Net-(D207-K)") (class "Default")
      (node (ref "D207") (pin "C") (pinfunction "K_C") (pintype "bidirectional"))
      (node (ref "D208") (pin "A") (pinfunction "A_A") (pintype "bidirectional"))
    )
    (net (code "315") (name "Net-(D208-K)") (class "Default")
      (node (ref "D208") (pin "C") (pinfunction "K_C") (pintype "bidirectional"))
      (node (ref "D209") (pin "A") (pinfunction "A_A") (pintype "bidirectional"))
    )
    (net (code "316") (name "Net-(D209-K)") (class "Default")
      (node (ref "D209") (pin "C") (pinfunction "K_C") (pintype "bidirectional"))
      (node (ref "D210") (pin "A") (pinfunction "A_A") (pintype "bidirectional"))
    )
    (net (code "317") (name "Net-(D210-K)") (class "Default")
      (node (ref "D210") (pin "C") (pinfunction "K_C") (pintype "bidirectional"))
      (node (ref "D211") (pin "A") (pinfunction "A_A") (pintype "bidirectional"))
    )
    (net (code "318") (name "Net-(D213-K)") (class "Default")
      (node (ref "D213") (pin "C") (pinfunction "K_C") (pintype "bidirectional"))
      (node (ref "D214") (pin "A") (pinfunction "A_A") (pintype "bidirectional"))
    )
    (net (code "319") (name "Net-(D214-K)") (class "Default")
      (node (ref "D214") (pin "C") (pinfunction "K_C") (pintype "bidirectional"))
      (node (ref "D215") (pin "A") (pinfunction "A_A") (pintype "bidirectional"))
    )
    (net (code "320") (name "Net-(D215-K)") (class "Default")
      (node (ref "D215") (pin "C") (pinfunction "K_C") (pintype "bidirectional"))
      (node (ref "D216") (pin "A") (pinfunction "A_A") (pintype "bidirectional"))
    )
    (net (code "321") (name "Net-(D216-K)") (class "Default")
      (node (ref "D216") (pin "C") (pinfunction "K_C") (pintype "bidirectional"))
      (node (ref "D217") (pin "A") (pinfunction "A_A") (pintype "bidirectional"))
    )
    (net (code "322") (name "Net-(D217-K)") (class "Default")
      (node (ref "D217") (pin "C") (pinfunction "K_C") (pintype "bidirectional"))
      (node (ref "D218") (pin "A") (pinfunction "A_A") (pintype "bidirectional"))
    )
    (net (code "323") (name "Net-(D218-K)") (class "Default")
      (node (ref "D218") (pin "C") (pinfunction "K_C") (pintype "bidirectional"))
      (node (ref "D219") (pin "A") (pinfunction "A_A") (pintype "bidirectional"))
    )
    (net (code "324") (name "Net-(D219-K)") (class "Default")
      (node (ref "D219") (pin "C") (pinfunction "K_C") (pintype "bidirectional"))
      (node (ref "D220") (pin "A") (pinfunction "A_A") (pintype "bidirectional"))
    )
    (net (code "325") (name "Net-(D220-K)") (class "Default")
      (node (ref "D220") (pin "C") (pinfunction "K_C") (pintype "bidirectional"))
      (node (ref "R60") (pin "2") (pinfunction "2_2") (pintype "passive"))
    )
    (net (code "326") (name "Net-(D221-K)") (class "Default")
      (node (ref "D221") (pin "C") (pinfunction "K_C") (pintype "bidirectional"))
      (node (ref "D222") (pin "A") (pinfunction "A_A") (pintype "bidirectional"))
    )
    (net (code "327") (name "Net-(D221-PadA)") (class "Default")
      (node (ref "D221") (pin "A") (pinfunction "A_A") (pintype "bidirectional"))
      (node (ref "R60") (pin "1") (pinfunction "1_1") (pintype "passive"))
    )
    (net (code "328") (name "Net-(D222-K)") (class "Default")
      (node (ref "D222") (pin "C") (pinfunction "K_C") (pintype "bidirectional"))
      (node (ref "D223") (pin "A") (pinfunction "A_A") (pintype "bidirectional"))
    )
    (net (code "329") (name "Net-(D223-K)") (class "Default")
      (node (ref "D223") (pin "C") (pinfunction "K_C") (pintype "bidirectional"))
      (node (ref "D224") (pin "A") (pinfunction "A_A") (pintype "bidirectional"))
    )
    (net (code "330") (name "Net-(D224-K)") (class "Default")
      (node (ref "D224") (pin "C") (pinfunction "K_C") (pintype "bidirectional"))
      (node (ref "D225") (pin "A") (pinfunction "A_A") (pintype "bidirectional"))
    )
    (net (code "331") (name "Net-(D225-K)") (class "Default")
      (node (ref "D225") (pin "C") (pinfunction "K_C") (pintype "bidirectional"))
      (node (ref "D226") (pin "A") (pinfunction "A_A") (pintype "bidirectional"))
    )
    (net (code "332") (name "Net-(D226-K)") (class "Default")
      (node (ref "D226") (pin "C") (pinfunction "K_C") (pintype "bidirectional"))
      (node (ref "D227") (pin "A") (pinfunction "A_A") (pintype "bidirectional"))
    )
    (net (code "333") (name "Net-(D227-K)") (class "Default")
      (node (ref "D227") (pin "C") (pinfunction "K_C") (pintype "bidirectional"))
      (node (ref "D228") (pin "A") (pinfunction "A_A") (pintype "bidirectional"))
    )
    (net (code "334") (name "Net-(D229-K)") (class "Default")
      (node (ref "D229") (pin "C") (pinfunction "K_C") (pintype "bidirectional"))
      (node (ref "D230") (pin "A") (pinfunction "A_A") (pintype "bidirectional"))
    )
    (net (code "335") (name "Net-(D230-K)") (class "Default")
      (node (ref "D230") (pin "C") (pinfunction "K_C") (pintype "bidirectional"))
      (node (ref "D231") (pin "A") (pinfunction "A_A") (pintype "bidirectional"))
    )
    (net (code "336") (name "Net-(D231-K)") (class "Default")
      (node (ref "D231") (pin "C") (pinfunction "K_C") (pintype "bidirectional"))
      (node (ref "D232") (pin "A") (pinfunction "A_A") (pintype "bidirectional"))
    )
    (net (code "337") (name "Net-(D232-K)") (class "Default")
      (node (ref "D232") (pin "C") (pinfunction "K_C") (pintype "bidirectional"))
      (node (ref "D233") (pin "A") (pinfunction "A_A") (pintype "bidirectional"))
    )
    (net (code "338") (name "Net-(D233-K)") (class "Default")
      (node (ref "D233") (pin "C") (pinfunction "K_C") (pintype "bidirectional"))
      (node (ref "D234") (pin "A") (pinfunction "A_A") (pintype "bidirectional"))
    )
    (net (code "339") (name "Net-(D234-K)") (class "Default")
      (node (ref "D234") (pin "C") (pinfunction "K_C") (pintype "bidirectional"))
      (node (ref "D235") (pin "A") (pinfunction "A_A") (pintype "bidirectional"))
    )
    (net (code "340") (name "Net-(D235-K)") (class "Default")
      (node (ref "D235") (pin "C") (pinfunction "K_C") (pintype "bidirectional"))
      (node (ref "D236") (pin "A") (pinfunction "A_A") (pintype "bidirectional"))
    )
    (net (code "341") (name "Net-(D236-K)") (class "Default")
      (node (ref "D236") (pin "C") (pinfunction "K_C") (pintype "bidirectional"))
      (node (ref "R64") (pin "2") (pinfunction "2_2") (pintype "passive"))
    )
    (net (code "342") (name "Net-(D237-K)") (class "Default")
      (node (ref "D237") (pin "C") (pinfunction "K_C") (pintype "bidirectional"))
      (node (ref "D238") (pin "A") (pinfunction "A_A") (pintype "bidirectional"))
    )
    (net (code "343") (name "Net-(D237-PadA)") (class "Default")
      (node (ref "D237") (pin "A") (pinfunction "A_A") (pintype "bidirectional"))
      (node (ref "R64") (pin "1") (pinfunction "1_1") (pintype "passive"))
    )
    (net (code "344") (name "Net-(D238-K)") (class "Default")
      (node (ref "D238") (pin "C") (pinfunction "K_C") (pintype "bidirectional"))
      (node (ref "D239") (pin "A") (pinfunction "A_A") (pintype "bidirectional"))
    )
    (net (code "345") (name "Net-(D239-K)") (class "Default")
      (node (ref "D239") (pin "C") (pinfunction "K_C") (pintype "bidirectional"))
      (node (ref "D240") (pin "A") (pinfunction "A_A") (pintype "bidirectional"))
    )
    (net (code "346") (name "Net-(D240-K)") (class "Default")
      (node (ref "D240") (pin "C") (pinfunction "K_C") (pintype "bidirectional"))
      (node (ref "D241") (pin "A") (pinfunction "A_A") (pintype "bidirectional"))
    )
    (net (code "347") (name "Net-(D241-K)") (class "Default")
      (node (ref "D241") (pin "C") (pinfunction "K_C") (pintype "bidirectional"))
      (node (ref "D242") (pin "A") (pinfunction "A_A") (pintype "bidirectional"))
    )
    (net (code "348") (name "Net-(D242-K)") (class "Default")
      (node (ref "D242") (pin "C") (pinfunction "K_C") (pintype "bidirectional"))
      (node (ref "D243") (pin "A") (pinfunction "A_A") (pintype "bidirectional"))
    )
    (net (code "349") (name "Net-(D243-K)") (class "Default")
      (node (ref "D243") (pin "C") (pinfunction "K_C") (pintype "bidirectional"))
      (node (ref "D244") (pin "A") (pinfunction "A_A") (pintype "bidirectional"))
    )
    (net (code "350") (name "Net-(D245-K)") (class "Default")
      (node (ref "D245") (pin "C") (pinfunction "K_C") (pintype "bidirectional"))
      (node (ref "D246") (pin "A") (pinfunction "A_A") (pintype "bidirectional"))
    )
    (net (code "351") (name "Net-(D246-K)") (class "Default")
      (node (ref "D246") (pin "C") (pinfunction "K_C") (pintype "bidirectional"))
      (node (ref "D247") (pin "A") (pinfunction "A_A") (pintype "bidirectional"))
    )
    (net (code "352") (name "Net-(D247-K)") (class "Default")
      (node (ref "D247") (pin "C") (pinfunction "K_C") (pintype "bidirectional"))
      (node (ref "D248") (pin "A") (pinfunction "A_A") (pintype "bidirectional"))
    )
    (net (code "353") (name "Net-(D248-K)") (class "Default")
      (node (ref "D248") (pin "C") (pinfunction "K_C") (pintype "bidirectional"))
      (node (ref "D249") (pin "A") (pinfunction "A_A") (pintype "bidirectional"))
    )
    (net (code "354") (name "Net-(D249-K)") (class "Default")
      (node (ref "D249") (pin "C") (pinfunction "K_C") (pintype "bidirectional"))
      (node (ref "D250") (pin "A") (pinfunction "A_A") (pintype "bidirectional"))
    )
    (net (code "355") (name "Net-(D250-K)") (class "Default")
      (node (ref "D250") (pin "C") (pinfunction "K_C") (pintype "bidirectional"))
      (node (ref "D251") (pin "A") (pinfunction "A_A") (pintype "bidirectional"))
    )
    (net (code "356") (name "Net-(D251-K)") (class "Default")
      (node (ref "D251") (pin "C") (pinfunction "K_C") (pintype "bidirectional"))
      (node (ref "D252") (pin "A") (pinfunction "A_A") (pintype "bidirectional"))
    )
    (net (code "357") (name "Net-(D252-K)") (class "Default")
      (node (ref "D252") (pin "C") (pinfunction "K_C") (pintype "bidirectional"))
      (node (ref "R67") (pin "2") (pinfunction "2_2") (pintype "passive"))
    )
    (net (code "358") (name "Net-(D253-K)") (class "Default")
      (node (ref "D253") (pin "C") (pinfunction "K_C") (pintype "bidirectional"))
      (node (ref "D254") (pin "A") (pinfunction "A_A") (pintype "bidirectional"))
    )
    (net (code "359") (name "Net-(D253-PadA)") (class "Default")
      (node (ref "D253") (pin "A") (pinfunction "A_A") (pintype "bidirectional"))
      (node (ref "R67") (pin "1") (pinfunction "1_1") (pintype "passive"))
    )
    (net (code "360") (name "Net-(D254-K)") (class "Default")
      (node (ref "D254") (pin "C") (pinfunction "K_C") (pintype "bidirectional"))
      (node (ref "D255") (pin "A") (pinfunction "A_A") (pintype "bidirectional"))
    )
    (net (code "361") (name "Net-(D255-K)") (class "Default")
      (node (ref "D255") (pin "C") (pinfunction "K_C") (pintype "bidirectional"))
      (node (ref "D256") (pin "A") (pinfunction "A_A") (pintype "bidirectional"))
    )
    (net (code "362") (name "Net-(D256-K)") (class "Default")
      (node (ref "D256") (pin "C") (pinfunction "K_C") (pintype "bidirectional"))
      (node (ref "D257") (pin "A") (pinfunction "A_A") (pintype "bidirectional"))
    )
    (net (code "363") (name "Net-(D257-K)") (class "Default")
      (node (ref "D257") (pin "C") (pinfunction "K_C") (pintype "bidirectional"))
      (node (ref "D258") (pin "A") (pinfunction "A_A") (pintype "bidirectional"))
    )
    (net (code "364") (name "Net-(D258-K)") (class "Default")
      (node (ref "D258") (pin "C") (pinfunction "K_C") (pintype "bidirectional"))
      (node (ref "D259") (pin "A") (pinfunction "A_A") (pintype "bidirectional"))
    )
    (net (code "365") (name "Net-(D259-K)") (class "Default")
      (node (ref "D259") (pin "C") (pinfunction "K_C") (pintype "bidirectional"))
      (node (ref "D260") (pin "A") (pinfunction "A_A") (pintype "bidirectional"))
    )
    (net (code "366") (name "Net-(GRN1-A)") (class "Default")
      (node (ref "GRN1") (pin "GA") (pinfunction "A_GA") (pintype "bidirectional"))
      (node (ref "GRN2") (pin "GC") (pinfunction "K_GC") (pintype "bidirectional"))
    )
    (net (code "367") (name "Net-(GRN2-A)") (class "Default")
      (node (ref "GRN2") (pin "GA") (pinfunction "A_GA") (pintype "bidirectional"))
      (node (ref "GRN3") (pin "GC") (pinfunction "K_GC") (pintype "bidirectional"))
    )
    (net (code "368") (name "Net-(GRN3-A)") (class "Default")
      (node (ref "GRN3") (pin "GA") (pinfunction "A_GA") (pintype "bidirectional"))
      (node (ref "GRN4") (pin "GC") (pinfunction "K_GC") (pintype "bidirectional"))
    )
    (net (code "369") (name "Net-(GRN4-A)") (class "Default")
      (node (ref "GRN4") (pin "GA") (pinfunction "A_GA") (pintype "bidirectional"))
      (node (ref "GRN5") (pin "GC") (pinfunction "K_GC") (pintype "bidirectional"))
    )
    (net (code "370") (name "Net-(GRN5-A)") (class "Default")
      (node (ref "GRN5") (pin "GA") (pinfunction "A_GA") (pintype "bidirectional"))
      (node (ref "GRN6") (pin "GC") (pinfunction "K_GC") (pintype "bidirectional"))
    )
    (net (code "371") (name "Net-(GRN6-A)") (class "Default")
      (node (ref "GRN6") (pin "GA") (pinfunction "A_GA") (pintype "bidirectional"))
      (node (ref "GRN7") (pin "GC") (pinfunction "K_GC") (pintype "bidirectional"))
    )
    (net (code "372") (name "Net-(GRN7-A)") (class "Default")
      (node (ref "GRN7") (pin "GA") (pinfunction "A_GA") (pintype "bidirectional"))
      (node (ref "GRN8") (pin "GC") (pinfunction "K_GC") (pintype "bidirectional"))
    )
    (net (code "373") (name "Net-(GRN10-A)") (class "Default")
      (node (ref "GRN10") (pin "GA") (pinfunction "A_GA") (pintype "bidirectional"))
      (node (ref "GRN11") (pin "GC") (pinfunction "K_GC") (pintype "bidirectional"))
    )
    (net (code "374") (name "Net-(GRN10-K)") (class "Default")
      (node (ref "GRN10") (pin "GC") (pinfunction "K_GC") (pintype "bidirectional"))
      (node (ref "GRN9") (pin "GA") (pinfunction "A_GA") (pintype "bidirectional"))
    )
    (net (code "375") (name "Net-(GRN11-A)") (class "Default")
      (node (ref "GRN11") (pin "GA") (pinfunction "A_GA") (pintype "bidirectional"))
      (node (ref "GRN12") (pin "GC") (pinfunction "K_GC") (pintype "bidirectional"))
    )
    (net (code "376") (name "Net-(GRN12-A)") (class "Default")
      (node (ref "GRN12") (pin "GA") (pinfunction "A_GA") (pintype "bidirectional"))
      (node (ref "GRN13") (pin "GC") (pinfunction "K_GC") (pintype "bidirectional"))
    )
    (net (code "377") (name "Net-(GRN13-A)") (class "Default")
      (node (ref "GRN13") (pin "GA") (pinfunction "A_GA") (pintype "bidirectional"))
      (node (ref "GRN14") (pin "GC") (pinfunction "K_GC") (pintype "bidirectional"))
    )
    (net (code "378") (name "Net-(GRN14-A)") (class "Default")
      (node (ref "GRN14") (pin "GA") (pinfunction "A_GA") (pintype "bidirectional"))
      (node (ref "GRN15") (pin "GC") (pinfunction "K_GC") (pintype "bidirectional"))
    )
    (net (code "379") (name "Net-(GRN15-A)") (class "Default")
      (node (ref "GRN15") (pin "GA") (pinfunction "A_GA") (pintype "bidirectional"))
      (node (ref "GRN16") (pin "GC") (pinfunction "K_GC") (pintype "bidirectional"))
    )
    (net (code "380") (name "Net-(GRN17-A)") (class "Default")
      (node (ref "GRN17") (pin "GA") (pinfunction "A_GA") (pintype "bidirectional"))
      (node (ref "GRN18") (pin "GC") (pinfunction "K_GC") (pintype "bidirectional"))
    )
    (net (code "381") (name "Net-(GRN18-A)") (class "Default")
      (node (ref "GRN18") (pin "GA") (pinfunction "A_GA") (pintype "bidirectional"))
      (node (ref "GRN19") (pin "GC") (pinfunction "K_GC") (pintype "bidirectional"))
    )
    (net (code "382") (name "Net-(GRN19-A)") (class "Default")
      (node (ref "GRN19") (pin "GA") (pinfunction "A_GA") (pintype "bidirectional"))
      (node (ref "GRN20") (pin "GC") (pinfunction "K_GC") (pintype "bidirectional"))
    )
    (net (code "383") (name "Net-(GRN20-A)") (class "Default")
      (node (ref "GRN20") (pin "GA") (pinfunction "A_GA") (pintype "bidirectional"))
      (node (ref "GRN21") (pin "GC") (pinfunction "K_GC") (pintype "bidirectional"))
    )
    (net (code "384") (name "Net-(GRN21-A)") (class "Default")
      (node (ref "GRN21") (pin "GA") (pinfunction "A_GA") (pintype "bidirectional"))
      (node (ref "GRN22") (pin "GC") (pinfunction "K_GC") (pintype "bidirectional"))
    )
    (net (code "385") (name "Net-(GRN22-A)") (class "Default")
      (node (ref "GRN22") (pin "GA") (pinfunction "A_GA") (pintype "bidirectional"))
      (node (ref "GRN23") (pin "GC") (pinfunction "K_GC") (pintype "bidirectional"))
    )
    (net (code "386") (name "Net-(GRN23-A)") (class "Default")
      (node (ref "GRN23") (pin "GA") (pinfunction "A_GA") (pintype "bidirectional"))
      (node (ref "GRN24") (pin "GC") (pinfunction "K_GC") (pintype "bidirectional"))
    )
    (net (code "387") (name "Net-(GRN25-A)") (class "Default")
      (node (ref "GRN25") (pin "GA") (pinfunction "A_GA") (pintype "bidirectional"))
      (node (ref "GRN26") (pin "GC") (pinfunction "K_GC") (pintype "bidirectional"))
    )
    (net (code "388") (name "Net-(GRN26-A)") (class "Default")
      (node (ref "GRN26") (pin "GA") (pinfunction "A_GA") (pintype "bidirectional"))
      (node (ref "GRN27") (pin "GC") (pinfunction "K_GC") (pintype "bidirectional"))
    )
    (net (code "389") (name "Net-(GRN27-A)") (class "Default")
      (node (ref "GRN27") (pin "GA") (pinfunction "A_GA") (pintype "bidirectional"))
      (node (ref "GRN28") (pin "GC") (pinfunction "K_GC") (pintype "bidirectional"))
    )
    (net (code "390") (name "Net-(GRN28-A)") (class "Default")
      (node (ref "GRN28") (pin "GA") (pinfunction "A_GA") (pintype "bidirectional"))
      (node (ref "GRN29") (pin "GC") (pinfunction "K_GC") (pintype "bidirectional"))
    )
    (net (code "391") (name "Net-(GRN29-A)") (class "Default")
      (node (ref "GRN29") (pin "GA") (pinfunction "A_GA") (pintype "bidirectional"))
      (node (ref "GRN30") (pin "GC") (pinfunction "K_GC") (pintype "bidirectional"))
    )
    (net (code "392") (name "Net-(GRN30-A)") (class "Default")
      (node (ref "GRN30") (pin "GA") (pinfunction "A_GA") (pintype "bidirectional"))
      (node (ref "GRN31") (pin "GC") (pinfunction "K_GC") (pintype "bidirectional"))
    )
    (net (code "393") (name "Net-(GRN31-A)") (class "Default")
      (node (ref "GRN31") (pin "GA") (pinfunction "A_GA") (pintype "bidirectional"))
      (node (ref "GRN32") (pin "GC") (pinfunction "K_GC") (pintype "bidirectional"))
    )
    (net (code "394") (name "Net-(GRN33-A)") (class "Default")
      (node (ref "GRN33") (pin "GA") (pinfunction "A_GA") (pintype "bidirectional"))
      (node (ref "GRN34") (pin "GC") (pinfunction "K_GC") (pintype "bidirectional"))
    )
    (net (code "395") (name "Net-(GRN33-K)") (class "Default")
      (node (ref "GRN33") (pin "GC") (pinfunction "K_GC") (pintype "bidirectional"))
      (node (ref "JMP9") (pin "1") (pinfunction "1_1") (pintype "bidirectional"))
    )
    (net (code "396") (name "Net-(GRN34-A)") (class "Default")
      (node (ref "GRN34") (pin "GA") (pinfunction "A_GA") (pintype "bidirectional"))
      (node (ref "GRN35") (pin "GC") (pinfunction "K_GC") (pintype "bidirectional"))
    )
    (net (code "397") (name "Net-(GRN35-A)") (class "Default")
      (node (ref "GRN35") (pin "GA") (pinfunction "A_GA") (pintype "bidirectional"))
      (node (ref "GRN36") (pin "GC") (pinfunction "K_GC") (pintype "bidirectional"))
    )
    (net (code "398") (name "Net-(GRN36-A)") (class "Default")
      (node (ref "GRN36") (pin "GA") (pinfunction "A_GA") (pintype "bidirectional"))
      (node (ref "GRN37") (pin "GC") (pinfunction "K_GC") (pintype "bidirectional"))
    )
    (net (code "399") (name "Net-(GRN37-A)") (class "Default")
      (node (ref "GRN37") (pin "GA") (pinfunction "A_GA") (pintype "bidirectional"))
      (node (ref "GRN38") (pin "GC") (pinfunction "K_GC") (pintype "bidirectional"))
    )
    (net (code "400") (name "Net-(GRN38-A)") (class "Default")
      (node (ref "GRN38") (pin "GA") (pinfunction "A_GA") (pintype "bidirectional"))
      (node (ref "GRN39") (pin "GC") (pinfunction "K_GC") (pintype "bidirectional"))
    )
    (net (code "401") (name "Net-(GRN39-A)") (class "Default")
      (node (ref "GRN39") (pin "GA") (pinfunction "A_GA") (pintype "bidirectional"))
      (node (ref "GRN40") (pin "GC") (pinfunction "K_GC") (pintype "bidirectional"))
    )
    (net (code "402") (name "Net-(GRN41-A)") (class "Default")
      (node (ref "GRN41") (pin "GA") (pinfunction "A_GA") (pintype "bidirectional"))
      (node (ref "GRN42") (pin "GC") (pinfunction "K_GC") (pintype "bidirectional"))
    )
    (net (code "403") (name "Net-(GRN41-K)") (class "Default")
      (node (ref "GRN41") (pin "GC") (pinfunction "K_GC") (pintype "bidirectional"))
      (node (ref "Q8") (pin "5") (pinfunction "C2_5") (pintype "bidirectional"))
      (node (ref "Q8") (pin "56") (pinfunction "C2_56") (pintype "bidirectional"))
      (node (ref "Q8") (pin "6") (pinfunction "C2_6") (pintype "bidirectional"))
    )
    (net (code "404") (name "Net-(GRN42-A)") (class "Default")
      (node (ref "GRN42") (pin "GA") (pinfunction "A_GA") (pintype "bidirectional"))
      (node (ref "GRN43") (pin "GC") (pinfunction "K_GC") (pintype "bidirectional"))
    )
    (net (code "405") (name "Net-(GRN43-A)") (class "Default")
      (node (ref "GRN43") (pin "GA") (pinfunction "A_GA") (pintype "bidirectional"))
      (node (ref "GRN44") (pin "GC") (pinfunction "K_GC") (pintype "bidirectional"))
    )
    (net (code "406") (name "Net-(GRN44-A)") (class "Default")
      (node (ref "GRN44") (pin "GA") (pinfunction "A_GA") (pintype "bidirectional"))
      (node (ref "GRN45") (pin "GC") (pinfunction "K_GC") (pintype "bidirectional"))
    )
    (net (code "407") (name "Net-(GRN45-A)") (class "Default")
      (node (ref "GRN45") (pin "GA") (pinfunction "A_GA") (pintype "bidirectional"))
      (node (ref "GRN46") (pin "GC") (pinfunction "K_GC") (pintype "bidirectional"))
    )
    (net (code "408") (name "Net-(GRN46-A)") (class "Default")
      (node (ref "GRN46") (pin "GA") (pinfunction "A_GA") (pintype "bidirectional"))
      (node (ref "GRN47") (pin "GC") (pinfunction "K_GC") (pintype "bidirectional"))
    )
    (net (code "409") (name "Net-(GRN47-A)") (class "Default")
      (node (ref "GRN47") (pin "GA") (pinfunction "A_GA") (pintype "bidirectional"))
      (node (ref "GRN48") (pin "GC") (pinfunction "K_GC") (pintype "bidirectional"))
    )
    (net (code "410") (name "Net-(GRN49-A)") (class "Default")
      (node (ref "GRN49") (pin "GA") (pinfunction "A_GA") (pintype "bidirectional"))
      (node (ref "GRN50") (pin "GC") (pinfunction "K_GC") (pintype "bidirectional"))
    )
    (net (code "411") (name "Net-(GRN49-K)") (class "Default")
      (node (ref "GRN49") (pin "GC") (pinfunction "K_GC") (pintype "bidirectional"))
      (node (ref "JMP12") (pin "1") (pinfunction "1_1") (pintype "bidirectional"))
    )
    (net (code "412") (name "Net-(GRN50-A)") (class "Default")
      (node (ref "GRN50") (pin "GA") (pinfunction "A_GA") (pintype "bidirectional"))
      (node (ref "GRN51") (pin "GC") (pinfunction "K_GC") (pintype "bidirectional"))
    )
    (net (code "413") (name "Net-(GRN51-A)") (class "Default")
      (node (ref "GRN51") (pin "GA") (pinfunction "A_GA") (pintype "bidirectional"))
      (node (ref "GRN52") (pin "GC") (pinfunction "K_GC") (pintype "bidirectional"))
    )
    (net (code "414") (name "Net-(GRN52-A)") (class "Default")
      (node (ref "GRN52") (pin "GA") (pinfunction "A_GA") (pintype "bidirectional"))
      (node (ref "GRN53") (pin "GC") (pinfunction "K_GC") (pintype "bidirectional"))
    )
    (net (code "415") (name "Net-(GRN53-A)") (class "Default")
      (node (ref "GRN53") (pin "GA") (pinfunction "A_GA") (pintype "bidirectional"))
      (node (ref "GRN54") (pin "GC") (pinfunction "K_GC") (pintype "bidirectional"))
    )
    (net (code "416") (name "Net-(GRN54-A)") (class "Default")
      (node (ref "GRN54") (pin "GA") (pinfunction "A_GA") (pintype "bidirectional"))
      (node (ref "GRN55") (pin "GC") (pinfunction "K_GC") (pintype "bidirectional"))
    )
    (net (code "417") (name "Net-(GRN55-A)") (class "Default")
      (node (ref "GRN55") (pin "GA") (pinfunction "A_GA") (pintype "bidirectional"))
      (node (ref "GRN56") (pin "GC") (pinfunction "K_GC") (pintype "bidirectional"))
    )
    (net (code "418") (name "Net-(GRN57-A)") (class "Default")
      (node (ref "GRN57") (pin "GA") (pinfunction "A_GA") (pintype "bidirectional"))
      (node (ref "GRN58") (pin "GC") (pinfunction "K_GC") (pintype "bidirectional"))
    )
    (net (code "419") (name "Net-(GRN57-K)") (class "Default")
      (node (ref "GRN57") (pin "GC") (pinfunction "K_GC") (pintype "bidirectional"))
      (node (ref "Q11") (pin "5") (pinfunction "C2_5") (pintype "bidirectional"))
      (node (ref "Q11") (pin "56") (pinfunction "C2_56") (pintype "bidirectional"))
      (node (ref "Q11") (pin "6") (pinfunction "C2_6") (pintype "bidirectional"))
    )
    (net (code "420") (name "Net-(GRN58-A)") (class "Default")
      (node (ref "GRN58") (pin "GA") (pinfunction "A_GA") (pintype "bidirectional"))
      (node (ref "GRN59") (pin "GC") (pinfunction "K_GC") (pintype "bidirectional"))
    )
    (net (code "421") (name "Net-(GRN59-A)") (class "Default")
      (node (ref "GRN59") (pin "GA") (pinfunction "A_GA") (pintype "bidirectional"))
      (node (ref "GRN60") (pin "GC") (pinfunction "K_GC") (pintype "bidirectional"))
    )
    (net (code "422") (name "Net-(GRN60-A)") (class "Default")
      (node (ref "GRN60") (pin "GA") (pinfunction "A_GA") (pintype "bidirectional"))
      (node (ref "GRN61") (pin "GC") (pinfunction "K_GC") (pintype "bidirectional"))
    )
    (net (code "423") (name "Net-(GRN61-A)") (class "Default")
      (node (ref "GRN61") (pin "GA") (pinfunction "A_GA") (pintype "bidirectional"))
      (node (ref "GRN62") (pin "GC") (pinfunction "K_GC") (pintype "bidirectional"))
    )
    (net (code "424") (name "Net-(GRN62-A)") (class "Default")
      (node (ref "GRN62") (pin "GA") (pinfunction "A_GA") (pintype "bidirectional"))
      (node (ref "GRN63") (pin "GC") (pinfunction "K_GC") (pintype "bidirectional"))
    )
    (net (code "425") (name "Net-(GRN63-A)") (class "Default")
      (node (ref "GRN63") (pin "GA") (pinfunction "A_GA") (pintype "bidirectional"))
      (node (ref "GRN64") (pin "GC") (pinfunction "K_GC") (pintype "bidirectional"))
    )
    (net (code "426") (name "Net-(JMP1-Pad2)") (class "Default")
      (node (ref "JMP1") (pin "2") (pinfunction "2_2") (pintype "bidirectional"))
      (node (ref "Q2") (pin "7") (pinfunction "C1_7") (pintype "bidirectional"))
      (node (ref "Q2") (pin "78") (pinfunction "C1_78") (pintype "bidirectional"))
      (node (ref "Q2") (pin "8") (pinfunction "C1_8") (pintype "bidirectional"))
    )
    (net (code "427") (name "Net-(JMP2-Pad2)") (class "Default")
      (node (ref "JMP2") (pin "2") (pinfunction "2_2") (pintype "bidirectional"))
      (node (ref "Q3") (pin "7") (pinfunction "C1_7") (pintype "bidirectional"))
      (node (ref "Q3") (pin "78") (pinfunction "C1_78") (pintype "bidirectional"))
      (node (ref "Q3") (pin "8") (pinfunction "C1_8") (pintype "bidirectional"))
    )
    (net (code "428") (name "Net-(JMP4-Pad2)") (class "Default")
      (node (ref "JMP4") (pin "2") (pinfunction "2_2") (pintype "bidirectional"))
      (node (ref "Q5") (pin "7") (pinfunction "C1_7") (pintype "bidirectional"))
      (node (ref "Q5") (pin "78") (pinfunction "C1_78") (pintype "bidirectional"))
      (node (ref "Q5") (pin "8") (pinfunction "C1_8") (pintype "bidirectional"))
    )
    (net (code "429") (name "Net-(JMP5-Pad1)") (class "Default")
      (node (ref "JMP5") (pin "1") (pinfunction "1_1") (pintype "bidirectional"))
      (node (ref "JMP7") (pin "2") (pinfunction "2_2") (pintype "bidirectional"))
    )
    (net (code "430") (name "Net-(JMP6-Pad2)") (class "Default")
      (node (ref "JMP6") (pin "2") (pinfunction "2_2") (pintype "bidirectional"))
      (node (ref "Q6") (pin "7") (pinfunction "C1_7") (pintype "bidirectional"))
      (node (ref "Q6") (pin "78") (pinfunction "C1_78") (pintype "bidirectional"))
      (node (ref "Q6") (pin "8") (pinfunction "C1_8") (pintype "bidirectional"))
    )
    (net (code "431") (name "Net-(JMP9-Pad2)") (class "Default")
      (node (ref "JMP9") (pin "2") (pinfunction "2_2") (pintype "bidirectional"))
      (node (ref "Q8") (pin "7") (pinfunction "C1_7") (pintype "bidirectional"))
      (node (ref "Q8") (pin "78") (pinfunction "C1_78") (pintype "bidirectional"))
      (node (ref "Q8") (pin "8") (pinfunction "C1_8") (pintype "bidirectional"))
    )
    (net (code "432") (name "Net-(JMP10-Pad2)") (class "Default")
      (node (ref "JMP10") (pin "2") (pinfunction "2_2") (pintype "bidirectional"))
      (node (ref "Q9") (pin "7") (pinfunction "C1_7") (pintype "bidirectional"))
      (node (ref "Q9") (pin "78") (pinfunction "C1_78") (pintype "bidirectional"))
      (node (ref "Q9") (pin "8") (pinfunction "C1_8") (pintype "bidirectional"))
    )
    (net (code "433") (name "Net-(JMP12-Pad2)") (class "Default")
      (node (ref "JMP12") (pin "2") (pinfunction "2_2") (pintype "bidirectional"))
      (node (ref "Q11") (pin "7") (pinfunction "C1_7") (pintype "bidirectional"))
      (node (ref "Q11") (pin "78") (pinfunction "C1_78") (pintype "bidirectional"))
      (node (ref "Q11") (pin "8") (pinfunction "C1_8") (pintype "bidirectional"))
    )
    (net (code "434") (name "Net-(JMP13-Pad2)") (class "Default")
      (node (ref "JMP13") (pin "2") (pinfunction "2_2") (pintype "bidirectional"))
      (node (ref "Q12") (pin "7") (pinfunction "C1_7") (pintype "bidirectional"))
      (node (ref "Q12") (pin "78") (pinfunction "C1_78") (pintype "bidirectional"))
      (node (ref "Q12") (pin "8") (pinfunction "C1_8") (pintype "bidirectional"))
    )
    (net (code "435") (name "Net-(Q1-B1)") (class "Default")
      (node (ref "Q1") (pin "2") (pinfunction "B1_2") (pintype "bidirectional"))
      (node (ref "R2") (pin "2") (pinfunction "2_2") (pintype "passive"))
    )
    (net (code "436") (name "Net-(Q1-E1)") (class "Default")
      (node (ref "Q1") (pin "1") (pinfunction "E1_1") (pintype "bidirectional"))
      (node (ref "R3") (pin "2") (pinfunction "2_2") (pintype "passive"))
    )
    (net (code "437") (name "Net-(Q2-B1)") (class "Default")
      (node (ref "Q2") (pin "2") (pinfunction "B1_2") (pintype "bidirectional"))
      (node (ref "R6") (pin "2") (pinfunction "2_2") (pintype "passive"))
    )
    (net (code "438") (name "Net-(Q2-E1)") (class "Default")
      (node (ref "Q2") (pin "1") (pinfunction "E1_1") (pintype "bidirectional"))
      (node (ref "R7") (pin "2") (pinfunction "2_2") (pintype "passive"))
    )
    (net (code "439") (name "Net-(Q3-B2)") (class "Default")
      (node (ref "Q3") (pin "4") (pinfunction "B2_4") (pintype "bidirectional"))
      (node (ref "R8") (pin "1") (pinfunction "1_1") (pintype "passive"))
    )
    (net (code "440") (name "Net-(Q3-E2)") (class "Default")
      (node (ref "Q3") (pin "3") (pinfunction "E2_3") (pintype "bidirectional"))
      (node (ref "R13") (pin "2") (pinfunction "2_2") (pintype "passive"))
    )
    (net (code "441") (name "Net-(Q4-B2)") (class "Default")
      (node (ref "Q4") (pin "4") (pinfunction "B2_4") (pintype "bidirectional"))
      (node (ref "R28") (pin "1") (pinfunction "1_1") (pintype "passive"))
    )
    (net (code "442") (name "Net-(Q4-E2)") (class "Default")
      (node (ref "Q4") (pin "3") (pinfunction "E2_3") (pintype "bidirectional"))
      (node (ref "R24") (pin "2") (pinfunction "2_2") (pintype "passive"))
    )
    (net (code "443") (name "Net-(Q5-B2)") (class "Default")
      (node (ref "Q5") (pin "4") (pinfunction "B2_4") (pintype "bidirectional"))
      (node (ref "R31") (pin "1") (pinfunction "1_1") (pintype "passive"))
    )
    (net (code "444") (name "Net-(Q5-E2)") (class "Default")
      (node (ref "Q5") (pin "3") (pinfunction "E2_3") (pintype "bidirectional"))
      (node (ref "R27") (pin "2") (pinfunction "2_2") (pintype "passive"))
    )
    (net (code "445") (name "Net-(Q6-B2)") (class "Default")
      (node (ref "Q6") (pin "4") (pinfunction "B2_4") (pintype "bidirectional"))
      (node (ref "R33") (pin "1") (pinfunction "1_1") (pintype "passive"))
    )
    (net (code "446") (name "Net-(Q6-E2)") (class "Default")
      (node (ref "Q6") (pin "3") (pinfunction "E2_3") (pintype "bidirectional"))
      (node (ref "R32") (pin "2") (pinfunction "2_2") (pintype "passive"))
    )
    (net (code "447") (name "Net-(Q7-B1)") (class "Default")
      (node (ref "Q7") (pin "2") (pinfunction "B1_2") (pintype "bidirectional"))
      (node (ref "R36") (pin "2") (pinfunction "2_2") (pintype "passive"))
    )
    (net (code "448") (name "Net-(Q7-E1)") (class "Default")
      (node (ref "Q7") (pin "1") (pinfunction "E1_1") (pintype "bidirectional"))
      (node (ref "R37") (pin "2") (pinfunction "2_2") (pintype "passive"))
    )
    (net (code "449") (name "Net-(Q8-B1)") (class "Default")
      (node (ref "Q8") (pin "2") (pinfunction "B1_2") (pintype "bidirectional"))
      (node (ref "R40") (pin "2") (pinfunction "2_2") (pintype "passive"))
    )
    (net (code "450") (name "Net-(Q8-E1)") (class "Default")
      (node (ref "Q8") (pin "1") (pinfunction "E1_1") (pintype "bidirectional"))
      (node (ref "R41") (pin "2") (pinfunction "2_2") (pintype "passive"))
    )
    (net (code "451") (name "Net-(Q9-B2)") (class "Default")
      (node (ref "Q9") (pin "4") (pinfunction "B2_4") (pintype "bidirectional"))
      (node (ref "R42") (pin "1") (pinfunction "1_1") (pintype "passive"))
    )
    (net (code "452") (name "Net-(Q9-E2)") (class "Default")
      (node (ref "Q9") (pin "3") (pinfunction "E2_3") (pintype "bidirectional"))
      (node (ref "R47") (pin "2") (pinfunction "2_2") (pintype "passive"))
    )
    (net (code "453") (name "Net-(Q10-B2)") (class "Default")
      (node (ref "Q10") (pin "4") (pinfunction "B2_4") (pintype "bidirectional"))
      (node (ref "R62") (pin "1") (pinfunction "1_1") (pintype "passive"))
    )
    (net (code "454") (name "Net-(Q10-E2)") (class "Default")
      (node (ref "Q10") (pin "3") (pinfunction "E2_3") (pintype "bidirectional"))
      (node (ref "R58") (pin "2") (pinfunction "2_2") (pintype "passive"))
    )
    (net (code "455") (name "Net-(Q11-B2)") (class "Default")
      (node (ref "Q11") (pin "4") (pinfunction "B2_4") (pintype "bidirectional"))
      (node (ref "R65") (pin "1") (pinfunction "1_1") (pintype "passive"))
    )
    (net (code "456") (name "Net-(Q11-E2)") (class "Default")
      (node (ref "Q11") (pin "3") (pinfunction "E2_3") (pintype "bidirectional"))
      (node (ref "R61") (pin "2") (pinfunction "2_2") (pintype "passive"))
    )
    (net (code "457") (name "Net-(Q12-B2)") (class "Default")
      (node (ref "Q12") (pin "4") (pinfunction "B2_4") (pintype "bidirectional"))
      (node (ref "R68") (pin "1") (pinfunction "1_1") (pintype "passive"))
    )
    (net (code "458") (name "Net-(Q12-E2)") (class "Default")
      (node (ref "Q12") (pin "3") (pinfunction "E2_3") (pintype "bidirectional"))
      (node (ref "R66") (pin "2") (pinfunction "2_2") (pintype "passive"))
    )
    (net (code "459") (name "Net-(RED1-A)") (class "Default")
      (node (ref "RED1") (pin "GA") (pinfunction "A_GA") (pintype "bidirectional"))
      (node (ref "RED2") (pin "GC") (pinfunction "K_GC") (pintype "bidirectional"))
    )
    (net (code "460") (name "Net-(RED2-A)") (class "Default")
      (node (ref "RED2") (pin "GA") (pinfunction "A_GA") (pintype "bidirectional"))
      (node (ref "RED3") (pin "GC") (pinfunction "K_GC") (pintype "bidirectional"))
    )
    (net (code "461") (name "Net-(RED3-A)") (class "Default")
      (node (ref "RED3") (pin "GA") (pinfunction "A_GA") (pintype "bidirectional"))
      (node (ref "RED4") (pin "GC") (pinfunction "K_GC") (pintype "bidirectional"))
    )
    (net (code "462") (name "Net-(RED4-A)") (class "Default")
      (node (ref "RED4") (pin "GA") (pinfunction "A_GA") (pintype "bidirectional"))
      (node (ref "RED5") (pin "GC") (pinfunction "K_GC") (pintype "bidirectional"))
    )
    (net (code "463") (name "Net-(RED5-A)") (class "Default")
      (node (ref "RED5") (pin "GA") (pinfunction "A_GA") (pintype "bidirectional"))
      (node (ref "RED6") (pin "GC") (pinfunction "K_GC") (pintype "bidirectional"))
    )
    (net (code "464") (name "Net-(RED6-A)") (class "Default")
      (node (ref "RED6") (pin "GA") (pinfunction "A_GA") (pintype "bidirectional"))
      (node (ref "RED7") (pin "GC") (pinfunction "K_GC") (pintype "bidirectional"))
    )
    (net (code "465") (name "Net-(RED7-A)") (class "Default")
      (node (ref "RED7") (pin "GA") (pinfunction "A_GA") (pintype "bidirectional"))
      (node (ref "RED8") (pin "GC") (pinfunction "K_GC") (pintype "bidirectional"))
    )
    (net (code "466") (name "Net-(RED10-A)") (class "Default")
      (node (ref "RED10") (pin "GA") (pinfunction "A_GA") (pintype "bidirectional"))
      (node (ref "RED11") (pin "GC") (pinfunction "K_GC") (pintype "bidirectional"))
    )
    (net (code "467") (name "Net-(RED10-K)") (class "Default")
      (node (ref "RED10") (pin "GC") (pinfunction "K_GC") (pintype "bidirectional"))
      (node (ref "RED9") (pin "GA") (pinfunction "A_GA") (pintype "bidirectional"))
    )
    (net (code "468") (name "Net-(RED11-A)") (class "Default")
      (node (ref "RED11") (pin "GA") (pinfunction "A_GA") (pintype "bidirectional"))
      (node (ref "RED12") (pin "GC") (pinfunction "K_GC") (pintype "bidirectional"))
    )
    (net (code "469") (name "Net-(RED12-A)") (class "Default")
      (node (ref "RED12") (pin "GA") (pinfunction "A_GA") (pintype "bidirectional"))
      (node (ref "RED13") (pin "GC") (pinfunction "K_GC") (pintype "bidirectional"))
    )
    (net (code "470") (name "Net-(RED13-A)") (class "Default")
      (node (ref "RED13") (pin "GA") (pinfunction "A_GA") (pintype "bidirectional"))
      (node (ref "RED14") (pin "GC") (pinfunction "K_GC") (pintype "bidirectional"))
    )
    (net (code "471") (name "Net-(RED14-A)") (class "Default")
      (node (ref "RED14") (pin "GA") (pinfunction "A_GA") (pintype "bidirectional"))
      (node (ref "RED15") (pin "GC") (pinfunction "K_GC") (pintype "bidirectional"))
    )
    (net (code "472") (name "Net-(RED15-A)") (class "Default")
      (node (ref "RED15") (pin "GA") (pinfunction "A_GA") (pintype "bidirectional"))
      (node (ref "RED16") (pin "GC") (pinfunction "K_GC") (pintype "bidirectional"))
    )
    (net (code "473") (name "Net-(RED17-A)") (class "Default")
      (node (ref "RED17") (pin "GA") (pinfunction "A_GA") (pintype "bidirectional"))
      (node (ref "RED18") (pin "GC") (pinfunction "K_GC") (pintype "bidirectional"))
    )
    (net (code "474") (name "Net-(RED18-A)") (class "Default")
      (node (ref "RED18") (pin "GA") (pinfunction "A_GA") (pintype "bidirectional"))
      (node (ref "RED19") (pin "GC") (pinfunction "K_GC") (pintype "bidirectional"))
    )
    (net (code "475") (name "Net-(RED19-A)") (class "Default")
      (node (ref "RED19") (pin "GA") (pinfunction "A_GA") (pintype "bidirectional"))
      (node (ref "RED20") (pin "GC") (pinfunction "K_GC") (pintype "bidirectional"))
    )
    (net (code "476") (name "Net-(RED20-A)") (class "Default")
      (node (ref "RED20") (pin "GA") (pinfunction "A_GA") (pintype "bidirectional"))
      (node (ref "RED21") (pin "GC") (pinfunction "K_GC") (pintype "bidirectional"))
    )
    (net (code "477") (name "Net-(RED21-A)") (class "Default")
      (node (ref "RED21") (pin "GA") (pinfunction "A_GA") (pintype "bidirectional"))
      (node (ref "RED22") (pin "GC") (pinfunction "K_GC") (pintype "bidirectional"))
    )
    (net (code "478") (name "Net-(RED22-A)") (class "Default")
      (node (ref "RED22") (pin "GA") (pinfunction "A_GA") (pintype "bidirectional"))
      (node (ref "RED23") (pin "GC") (pinfunction "K_GC") (pintype "bidirectional"))
    )
    (net (code "479") (name "Net-(RED23-A)") (class "Default")
      (node (ref "RED23") (pin "GA") (pinfunction "A_GA") (pintype "bidirectional"))
      (node (ref "RED24") (pin "GC") (pinfunction "K_GC") (pintype "bidirectional"))
    )
    (net (code "480") (name "Net-(RED25-A)") (class "Default")
      (node (ref "RED25") (pin "GA") (pinfunction "A_GA") (pintype "bidirectional"))
      (node (ref "RED26") (pin "GC") (pinfunction "K_GC") (pintype "bidirectional"))
    )
    (net (code "481") (name "Net-(RED26-A)") (class "Default")
      (node (ref "RED26") (pin "GA") (pinfunction "A_GA") (pintype "bidirectional"))
      (node (ref "RED27") (pin "GC") (pinfunction "K_GC") (pintype "bidirectional"))
    )
    (net (code "482") (name "Net-(RED27-A)") (class "Default")
      (node (ref "RED27") (pin "GA") (pinfunction "A_GA") (pintype "bidirectional"))
      (node (ref "RED28") (pin "GC") (pinfunction "K_GC") (pintype "bidirectional"))
    )
    (net (code "483") (name "Net-(RED28-A)") (class "Default")
      (node (ref "RED28") (pin "GA") (pinfunction "A_GA") (pintype "bidirectional"))
      (node (ref "RED29") (pin "GC") (pinfunction "K_GC") (pintype "bidirectional"))
    )
    (net (code "484") (name "Net-(RED29-A)") (class "Default")
      (node (ref "RED29") (pin "GA") (pinfunction "A_GA") (pintype "bidirectional"))
      (node (ref "RED30") (pin "GC") (pinfunction "K_GC") (pintype "bidirectional"))
    )
    (net (code "485") (name "Net-(RED30-A)") (class "Default")
      (node (ref "RED30") (pin "GA") (pinfunction "A_GA") (pintype "bidirectional"))
      (node (ref "RED31") (pin "GC") (pinfunction "K_GC") (pintype "bidirectional"))
    )
    (net (code "486") (name "Net-(RED31-A)") (class "Default")
      (node (ref "RED31") (pin "GA") (pinfunction "A_GA") (pintype "bidirectional"))
      (node (ref "RED32") (pin "GC") (pinfunction "K_GC") (pintype "bidirectional"))
    )
    (net (code "487") (name "Net-(RED33-A)") (class "Default")
      (node (ref "RED33") (pin "GA") (pinfunction "A_GA") (pintype "bidirectional"))
      (node (ref "RED34") (pin "GC") (pinfunction "K_GC") (pintype "bidirectional"))
    )
    (net (code "488") (name "Net-(RED34-A)") (class "Default")
      (node (ref "RED34") (pin "GA") (pinfunction "A_GA") (pintype "bidirectional"))
      (node (ref "RED35") (pin "GC") (pinfunction "K_GC") (pintype "bidirectional"))
    )
    (net (code "489") (name "Net-(RED35-A)") (class "Default")
      (node (ref "RED35") (pin "GA") (pinfunction "A_GA") (pintype "bidirectional"))
      (node (ref "RED36") (pin "GC") (pinfunction "K_GC") (pintype "bidirectional"))
    )
    (net (code "490") (name "Net-(RED36-A)") (class "Default")
      (node (ref "RED36") (pin "GA") (pinfunction "A_GA") (pintype "bidirectional"))
      (node (ref "RED37") (pin "GC") (pinfunction "K_GC") (pintype "bidirectional"))
    )
    (net (code "491") (name "Net-(RED37-A)") (class "Default")
      (node (ref "RED37") (pin "GA") (pinfunction "A_GA") (pintype "bidirectional"))
      (node (ref "RED38") (pin "GC") (pinfunction "K_GC") (pintype "bidirectional"))
    )
    (net (code "492") (name "Net-(RED38-A)") (class "Default")
      (node (ref "RED38") (pin "GA") (pinfunction "A_GA") (pintype "bidirectional"))
      (node (ref "RED39") (pin "GC") (pinfunction "K_GC") (pintype "bidirectional"))
    )
    (net (code "493") (name "Net-(RED39-A)") (class "Default")
      (node (ref "RED39") (pin "GA") (pinfunction "A_GA") (pintype "bidirectional"))
      (node (ref "RED40") (pin "GC") (pinfunction "K_GC") (pintype "bidirectional"))
    )
    (net (code "494") (name "Net-(RED41-A)") (class "Default")
      (node (ref "RED41") (pin "GA") (pinfunction "A_GA") (pintype "bidirectional"))
      (node (ref "RED42") (pin "GC") (pinfunction "K_GC") (pintype "bidirectional"))
    )
    (net (code "495") (name "Net-(RED41-K)") (class "Default")
      (node (ref "Q9") (pin "5") (pinfunction "C2_5") (pintype "bidirectional"))
      (node (ref "Q9") (pin "56") (pinfunction "C2_56") (pintype "bidirectional"))
      (node (ref "Q9") (pin "6") (pinfunction "C2_6") (pintype "bidirectional"))
      (node (ref "RED41") (pin "GC") (pinfunction "K_GC") (pintype "bidirectional"))
    )
    (net (code "496") (name "Net-(RED42-A)") (class "Default")
      (node (ref "RED42") (pin "GA") (pinfunction "A_GA") (pintype "bidirectional"))
      (node (ref "RED43") (pin "GC") (pinfunction "K_GC") (pintype "bidirectional"))
    )
    (net (code "497") (name "Net-(RED43-A)") (class "Default")
      (node (ref "RED43") (pin "GA") (pinfunction "A_GA") (pintype "bidirectional"))
      (node (ref "RED44") (pin "GC") (pinfunction "K_GC") (pintype "bidirectional"))
    )
    (net (code "498") (name "Net-(RED44-A)") (class "Default")
      (node (ref "RED44") (pin "GA") (pinfunction "A_GA") (pintype "bidirectional"))
      (node (ref "RED45") (pin "GC") (pinfunction "K_GC") (pintype "bidirectional"))
    )
    (net (code "499") (name "Net-(RED45-A)") (class "Default")
      (node (ref "RED45") (pin "GA") (pinfunction "A_GA") (pintype "bidirectional"))
      (node (ref "RED46") (pin "GC") (pinfunction "K_GC") (pintype "bidirectional"))
    )
    (net (code "500") (name "Net-(RED46-A)") (class "Default")
      (node (ref "RED46") (pin "GA") (pinfunction "A_GA") (pintype "bidirectional"))
      (node (ref "RED47") (pin "GC") (pinfunction "K_GC") (pintype "bidirectional"))
    )
    (net (code "501") (name "Net-(RED47-A)") (class "Default")
      (node (ref "RED47") (pin "GA") (pinfunction "A_GA") (pintype "bidirectional"))
      (node (ref "RED48") (pin "GC") (pinfunction "K_GC") (pintype "bidirectional"))
    )
    (net (code "502") (name "Net-(RED49-A)") (class "Default")
      (node (ref "RED49") (pin "GA") (pinfunction "A_GA") (pintype "bidirectional"))
      (node (ref "RED50") (pin "GC") (pinfunction "K_GC") (pintype "bidirectional"))
    )
    (net (code "503") (name "Net-(RED49-K)") (class "Default")
      (node (ref "JMP13") (pin "1") (pinfunction "1_1") (pintype "bidirectional"))
      (node (ref "RED49") (pin "GC") (pinfunction "K_GC") (pintype "bidirectional"))
    )
    (net (code "504") (name "Net-(RED50-A)") (class "Default")
      (node (ref "RED50") (pin "GA") (pinfunction "A_GA") (pintype "bidirectional"))
      (node (ref "RED51") (pin "GC") (pinfunction "K_GC") (pintype "bidirectional"))
    )
    (net (code "505") (name "Net-(RED51-A)") (class "Default")
      (node (ref "RED51") (pin "GA") (pinfunction "A_GA") (pintype "bidirectional"))
      (node (ref "RED52") (pin "GC") (pinfunction "K_GC") (pintype "bidirectional"))
    )
    (net (code "506") (name "Net-(RED52-A)") (class "Default")
      (node (ref "RED52") (pin "GA") (pinfunction "A_GA") (pintype "bidirectional"))
      (node (ref "RED53") (pin "GC") (pinfunction "K_GC") (pintype "bidirectional"))
    )
    (net (code "507") (name "Net-(RED53-A)") (class "Default")
      (node (ref "RED53") (pin "GA") (pinfunction "A_GA") (pintype "bidirectional"))
      (node (ref "RED54") (pin "GC") (pinfunction "K_GC") (pintype "bidirectional"))
    )
    (net (code "508") (name "Net-(RED54-A)") (class "Default")
      (node (ref "RED54") (pin "GA") (pinfunction "A_GA") (pintype "bidirectional"))
      (node (ref "RED55") (pin "GC") (pinfunction "K_GC") (pintype "bidirectional"))
    )
    (net (code "509") (name "Net-(RED55-A)") (class "Default")
      (node (ref "RED55") (pin "GA") (pinfunction "A_GA") (pintype "bidirectional"))
      (node (ref "RED56") (pin "GC") (pinfunction "K_GC") (pintype "bidirectional"))
    )
    (net (code "510") (name "Net-(RED57-A)") (class "Default")
      (node (ref "RED57") (pin "GA") (pinfunction "A_GA") (pintype "bidirectional"))
      (node (ref "RED58") (pin "GC") (pinfunction "K_GC") (pintype "bidirectional"))
    )
    (net (code "511") (name "Net-(RED57-K)") (class "Default")
      (node (ref "Q12") (pin "5") (pinfunction "C2_5") (pintype "bidirectional"))
      (node (ref "Q12") (pin "56") (pinfunction "C2_56") (pintype "bidirectional"))
      (node (ref "Q12") (pin "6") (pinfunction "C2_6") (pintype "bidirectional"))
      (node (ref "RED57") (pin "GC") (pinfunction "K_GC") (pintype "bidirectional"))
    )
    (net (code "512") (name "Net-(RED58-A)") (class "Default")
      (node (ref "RED58") (pin "GA") (pinfunction "A_GA") (pintype "bidirectional"))
      (node (ref "RED59") (pin "GC") (pinfunction "K_GC") (pintype "bidirectional"))
    )
    (net (code "513") (name "Net-(RED59-A)") (class "Default")
      (node (ref "RED59") (pin "GA") (pinfunction "A_GA") (pintype "bidirectional"))
      (node (ref "RED60") (pin "GC") (pinfunction "K_GC") (pintype "bidirectional"))
    )
    (net (code "514") (name "Net-(RED60-A)") (class "Default")
      (node (ref "RED60") (pin "GA") (pinfunction "A_GA") (pintype "bidirectional"))
      (node (ref "RED61") (pin "GC") (pinfunction "K_GC") (pintype "bidirectional"))
    )
    (net (code "515") (name "Net-(RED61-A)") (class "Default")
      (node (ref "RED61") (pin "GA") (pinfunction "A_GA") (pintype "bidirectional"))
      (node (ref "RED62") (pin "GC") (pinfunction "K_GC") (pintype "bidirectional"))
    )
    (net (code "516") (name "Net-(RED62-A)") (class "Default")
      (node (ref "RED62") (pin "GA") (pinfunction "A_GA") (pintype "bidirectional"))
      (node (ref "RED63") (pin "GC") (pinfunction "K_GC") (pintype "bidirectional"))
    )
    (net (code "517") (name "Net-(RED63-A)") (class "Default")
      (node (ref "RED63") (pin "GA") (pinfunction "A_GA") (pintype "bidirectional"))
      (node (ref "RED64") (pin "GC") (pinfunction "K_GC") (pintype "bidirectional"))
    )
    (net (code "518") (name "Net-(U1-SW)") (class "Default")
      (node (ref "D49") (pin "A") (pinfunction "A_A") (pintype "bidirectional"))
      (node (ref "L1") (pin "2") (pinfunction "2_2") (pintype "passive"))
      (node (ref "U1") (pin "5") (pinfunction "SW_5") (pintype "bidirectional"))
      (node (ref "U1") (pin "6") (pinfunction "SW1_6") (pintype "bidirectional"))
    )
    (net (code "519") (name "Net-(U2-SW)") (class "Default")
      (node (ref "D82") (pin "A") (pinfunction "A_A") (pintype "bidirectional"))
      (node (ref "L2") (pin "2") (pinfunction "2_2") (pintype "passive"))
      (node (ref "U2") (pin "5") (pinfunction "SW_5") (pintype "bidirectional"))
      (node (ref "U2") (pin "6") (pinfunction "SW1_6") (pintype "bidirectional"))
    )
    (net (code "520") (name "Net-(U3-SW)") (class "Default")
      (node (ref "D179") (pin "A") (pinfunction "A_A") (pintype "bidirectional"))
      (node (ref "L3") (pin "2") (pinfunction "2_2") (pintype "passive"))
      (node (ref "U3") (pin "5") (pinfunction "SW_5") (pintype "bidirectional"))
      (node (ref "U3") (pin "6") (pinfunction "SW1_6") (pintype "bidirectional"))
    )
    (net (code "521") (name "Net-(U4-SW)") (class "Default")
      (node (ref "D212") (pin "A") (pinfunction "A_A") (pintype "bidirectional"))
      (node (ref "L4") (pin "2") (pinfunction "2_2") (pintype "passive"))
      (node (ref "U4") (pin "5") (pinfunction "SW_5") (pintype "bidirectional"))
      (node (ref "U4") (pin "6") (pinfunction "SW1_6") (pintype "bidirectional"))
    )
    (net (code "522") (name "RED1") (class "Default")
      (node (ref "P1") (pin "11") (pinfunction "11_11") (pintype "bidirectional"))
      (node (ref "Q3") (pin "2") (pinfunction "B1_2") (pintype "bidirectional"))
      (node (ref "R8") (pin "2") (pinfunction "2_2") (pintype "passive"))
    )
    (net (code "523") (name "RED1F") (class "Default")
      (node (ref "P1") (pin "12") (pinfunction "12_12") (pintype "bidirectional"))
      (node (ref "Q3") (pin "1") (pinfunction "E1_1") (pintype "bidirectional"))
      (node (ref "R11") (pin "2") (pinfunction "2_2") (pintype "passive"))
    )
    (net (code "524") (name "RED1K") (class "Default")
      (node (ref "JMP2") (pin "1") (pinfunction "1_1") (pintype "bidirectional"))
      (node (ref "RED1") (pin "GC") (pinfunction "K_GC") (pintype "bidirectional"))
    )
    (net (code "525") (name "RED1K2") (class "Default")
      (node (ref "Q3") (pin "5") (pinfunction "C2_5") (pintype "bidirectional"))
      (node (ref "Q3") (pin "56") (pinfunction "C2_56") (pintype "bidirectional"))
      (node (ref "Q3") (pin "6") (pinfunction "C2_6") (pintype "bidirectional"))
      (node (ref "RED9") (pin "GC") (pinfunction "K_GC") (pintype "bidirectional"))
    )
    (net (code "526") (name "RED2") (class "Default")
      (node (ref "P1") (pin "6") (pinfunction "6_6") (pintype "bidirectional"))
      (node (ref "Q6") (pin "2") (pinfunction "B1_2") (pintype "bidirectional"))
      (node (ref "R33") (pin "2") (pinfunction "2_2") (pintype "passive"))
    )
    (net (code "527") (name "RED2F") (class "Default")
      (node (ref "P1") (pin "4") (pinfunction "4_4") (pintype "bidirectional"))
      (node (ref "Q6") (pin "1") (pinfunction "E1_1") (pintype "bidirectional"))
      (node (ref "R29") (pin "2") (pinfunction "2_2") (pintype "passive"))
    )
    (net (code "528") (name "RED2K1") (class "Default")
      (node (ref "JMP6") (pin "1") (pinfunction "1_1") (pintype "bidirectional"))
      (node (ref "RED17") (pin "GC") (pinfunction "K_GC") (pintype "bidirectional"))
    )
    (net (code "529") (name "RED2K2") (class "Default")
      (node (ref "Q6") (pin "5") (pinfunction "C2_5") (pintype "bidirectional"))
      (node (ref "Q6") (pin "56") (pinfunction "C2_56") (pintype "bidirectional"))
      (node (ref "Q6") (pin "6") (pinfunction "C2_6") (pintype "bidirectional"))
      (node (ref "RED25") (pin "GC") (pinfunction "K_GC") (pintype "bidirectional"))
    )
    (net (code "530") (name "RED3") (class "Default")
      (node (ref "P2") (pin "11") (pinfunction "11_11") (pintype "bidirectional"))
      (node (ref "Q9") (pin "2") (pinfunction "B1_2") (pintype "bidirectional"))
      (node (ref "R42") (pin "2") (pinfunction "2_2") (pintype "passive"))
    )
    (net (code "531") (name "RED3F") (class "Default")
      (node (ref "P2") (pin "12") (pinfunction "12_12") (pintype "bidirectional"))
      (node (ref "Q9") (pin "1") (pinfunction "E1_1") (pintype "bidirectional"))
      (node (ref "R45") (pin "2") (pinfunction "2_2") (pintype "passive"))
    )
    (net (code "532") (name "RED3K") (class "Default")
      (node (ref "JMP10") (pin "1") (pinfunction "1_1") (pintype "bidirectional"))
      (node (ref "RED33") (pin "GC") (pinfunction "K_GC") (pintype "bidirectional"))
    )
    (net (code "533") (name "RED4") (class "Default")
      (node (ref "P2") (pin "6") (pinfunction "6_6") (pintype "bidirectional"))
      (node (ref "Q12") (pin "2") (pinfunction "B1_2") (pintype "bidirectional"))
      (node (ref "R68") (pin "2") (pinfunction "2_2") (pintype "passive"))
    )
    (net (code "534") (name "RED4F") (class "Default")
      (node (ref "P2") (pin "4") (pinfunction "4_4") (pintype "bidirectional"))
      (node (ref "Q12") (pin "1") (pinfunction "E1_1") (pintype "bidirectional"))
      (node (ref "R63") (pin "2") (pinfunction "2_2") (pintype "passive"))
    )
    (net (code "535") (name "VIR1") (class "Default")
      (node (ref "C2") (pin "1") (pinfunction "1_1") (pintype "passive"))
      (node (ref "C20") (pin "1") (pinfunction "1_1") (pintype "passive"))
      (node (ref "C21") (pin "1") (pinfunction "1_1") (pintype "passive"))
      (node (ref "C3") (pin "1") (pinfunction "1_1") (pintype "passive"))
      (node (ref "C7") (pin "1") (pinfunction "1_1") (pintype "passive"))
      (node (ref "C8") (pin "1") (pinfunction "1_1") (pintype "passive"))
      (node (ref "D49") (pin "K") (pinfunction "K_K") (pintype "bidirectional"))
      (node (ref "D82") (pin "K") (pinfunction "K_K") (pintype "bidirectional"))
      (node (ref "JMP14") (pin "1") (pinfunction "1_1") (pintype "bidirectional"))
      (node (ref "JMP14") (pin "2") (pinfunction "2_2") (pintype "bidirectional"))
      (node (ref "JMP15") (pin "1") (pinfunction "1_1") (pintype "bidirectional"))
      (node (ref "JMP15") (pin "2") (pinfunction "2_2") (pintype "bidirectional"))
      (node (ref "JMP5") (pin "2") (pinfunction "2_2") (pintype "bidirectional"))
      (node (ref "R16") (pin "2") (pinfunction "2_2") (pintype "passive"))
      (node (ref "R18") (pin "1") (pinfunction "1_1") (pintype "passive"))
      (node (ref "R18") (pin "2") (pinfunction "2_2") (pintype "passive"))
      (node (ref "R19") (pin "2") (pinfunction "2_2") (pintype "passive"))
      (node (ref "U1") (pin "4") (pinfunction "VIN_4") (pintype "bidirectional"))
      (node (ref "U2") (pin "4") (pinfunction "VIN_4") (pintype "bidirectional"))
    )
    (net (code "536") (name "V_IR") (class "Default")
      (node (ref "C11") (pin "1") (pinfunction "1_1") (pintype "passive"))
      (node (ref "C12") (pin "1") (pinfunction "1_1") (pintype "passive"))
      (node (ref "C16") (pin "1") (pinfunction "1_1") (pintype "passive"))
      (node (ref "C17") (pin "1") (pinfunction "1_1") (pintype "passive"))
      (node (ref "C22") (pin "1") (pinfunction "1_1") (pintype "passive"))
      (node (ref "C23") (pin "1") (pinfunction "1_1") (pintype "passive"))
      (node (ref "D179") (pin "K") (pinfunction "K_K") (pintype "bidirectional"))
      (node (ref "D212") (pin "K") (pinfunction "K_K") (pintype "bidirectional"))
      (node (ref "JMP11") (pin "1") (pinfunction "1_1") (pintype "bidirectional"))
      (node (ref "JMP11") (pin "2") (pinfunction "2_2") (pintype "bidirectional"))
      (node (ref "JMP3") (pin "1") (pinfunction "1_1") (pintype "bidirectional"))
      (node (ref "JMP3") (pin "2") (pinfunction "2_2") (pintype "bidirectional"))
      (node (ref "JMP8") (pin "2") (pinfunction "2_2") (pintype "bidirectional"))
      (node (ref "R50") (pin "2") (pinfunction "2_2") (pintype "passive"))
      (node (ref "R52") (pin "1") (pinfunction "1_1") (pintype "passive"))
      (node (ref "R52") (pin "2") (pinfunction "2_2") (pintype "passive"))
      (node (ref "R53") (pin "2") (pinfunction "2_2") (pintype "passive"))
      (node (ref "U3") (pin "4") (pinfunction "VIN_4") (pintype "bidirectional"))
      (node (ref "U4") (pin "4") (pinfunction "VIN_4") (pintype "bidirectional"))
    )
    (net (code "537") (name "V_RGB") (class "Default")
      (node (ref "BLU16") (pin "GA") (pinfunction "A_GA") (pintype "bidirectional"))
      (node (ref "BLU24") (pin "GA") (pinfunction "A_GA") (pintype "bidirectional"))
      (node (ref "BLU32") (pin "GA") (pinfunction "A_GA") (pintype "bidirectional"))
      (node (ref "BLU40") (pin "GA") (pinfunction "A_GA") (pintype "bidirectional"))
      (node (ref "BLU48") (pin "GA") (pinfunction "A_GA") (pintype "bidirectional"))
      (node (ref "BLU56") (pin "GA") (pinfunction "A_GA") (pintype "bidirectional"))
      (node (ref "BLU64") (pin "GA") (pinfunction "A_GA") (pintype "bidirectional"))
      (node (ref "BLU8") (pin "GA") (pinfunction "A_GA") (pintype "bidirectional"))
      (node (ref "C1") (pin "+") (pinfunction "+_+") (pintype "passive"))
      (node (ref "C10") (pin "+") (pinfunction "+_+") (pintype "passive"))
      (node (ref "C19") (pin "+") (pinfunction "+_+") (pintype "passive"))
      (node (ref "GRN16") (pin "GA") (pinfunction "A_GA") (pintype "bidirectional"))
      (node (ref "GRN24") (pin "GA") (pinfunction "A_GA") (pintype "bidirectional"))
      (node (ref "GRN32") (pin "GA") (pinfunction "A_GA") (pintype "bidirectional"))
      (node (ref "GRN40") (pin "GA") (pinfunction "A_GA") (pintype "bidirectional"))
      (node (ref "GRN48") (pin "GA") (pinfunction "A_GA") (pintype "bidirectional"))
      (node (ref "GRN56") (pin "GA") (pinfunction "A_GA") (pintype "bidirectional"))
      (node (ref "GRN64") (pin "GA") (pinfunction "A_GA") (pintype "bidirectional"))
      (node (ref "GRN8") (pin "GA") (pinfunction "A_GA") (pintype "bidirectional"))
      (node (ref "J1") (pin "1A") (pinfunction "P$1_1A") (pintype "bidirectional"))
      (node (ref "J1") (pin "1B") (pinfunction "P$1_1B") (pintype "bidirectional"))
      (node (ref "JMP7") (pin "1") (pinfunction "1_1") (pintype "bidirectional"))
      (node (ref "JMP8") (pin "1") (pinfunction "1_1") (pintype "bidirectional"))
      (node (ref "P4") (pin "2") (pinfunction "2_2") (pintype "bidirectional"))
      (node (ref "P4") (pin "4") (pinfunction "4_4") (pintype "bidirectional"))
      (node (ref "RED16") (pin "GA") (pinfunction "A_GA") (pintype "bidirectional"))
      (node (ref "RED24") (pin "GA") (pinfunction "A_GA") (pintype "bidirectional"))
      (node (ref "RED32") (pin "GA") (pinfunction "A_GA") (pintype "bidirectional"))
      (node (ref "RED40") (pin "GA") (pinfunction "A_GA") (pintype "bidirectional"))
      (node (ref "RED48") (pin "GA") (pinfunction "A_GA") (pintype "bidirectional"))
      (node (ref "RED56") (pin "GA") (pinfunction "A_GA") (pintype "bidirectional"))
      (node (ref "RED64") (pin "GA") (pinfunction "A_GA") (pintype "bidirectional"))
      (node (ref "RED8") (pin "GA") (pinfunction "A_GA") (pintype "bidirectional"))
    )
    (net (code "538") (name "unconnected-(J1-P$2-Pad3)") (class "Default")
      (node (ref "J1") (pin "3") (pinfunction "P$2_3") (pintype "bidirectional"))
    )
    (net (code "539") (name "unconnected-(P4-Pad5)") (class "Default")
      (node (ref "P4") (pin "5") (pinfunction "5_5") (pintype "bidirectional"))
    )
    (net (code "540") (name "unconnected-(P4-Pad6)") (class "Default")
      (node (ref "P4") (pin "6") (pinfunction "6_6") (pintype "bidirectional"))
    )
    (net (code "541") (name "unconnected-(U1-N{slash}C-Pad3)") (class "Default")
      (node (ref "U1") (pin "3") (pinfunction "N/C_3") (pintype "bidirectional"))
    )
    (net (code "542") (name "unconnected-(U2-N{slash}C-Pad3)") (class "Default")
      (node (ref "U2") (pin "3") (pinfunction "N/C_3") (pintype "bidirectional"))
    )
    (net (code "543") (name "unconnected-(U3-N{slash}C-Pad3)") (class "Default")
      (node (ref "U3") (pin "3") (pinfunction "N/C_3") (pintype "bidirectional"))
    )
    (net (code "544") (name "unconnected-(U4-N{slash}C-Pad3)") (class "Default")
      (node (ref "U4") (pin "3") (pinfunction "N/C_3") (pintype "bidirectional"))
    )
  )
)
